# Orbit_I_AnalougeEngine_V2_0.net
KiCad netlist of a schematic drawn in EAGLE
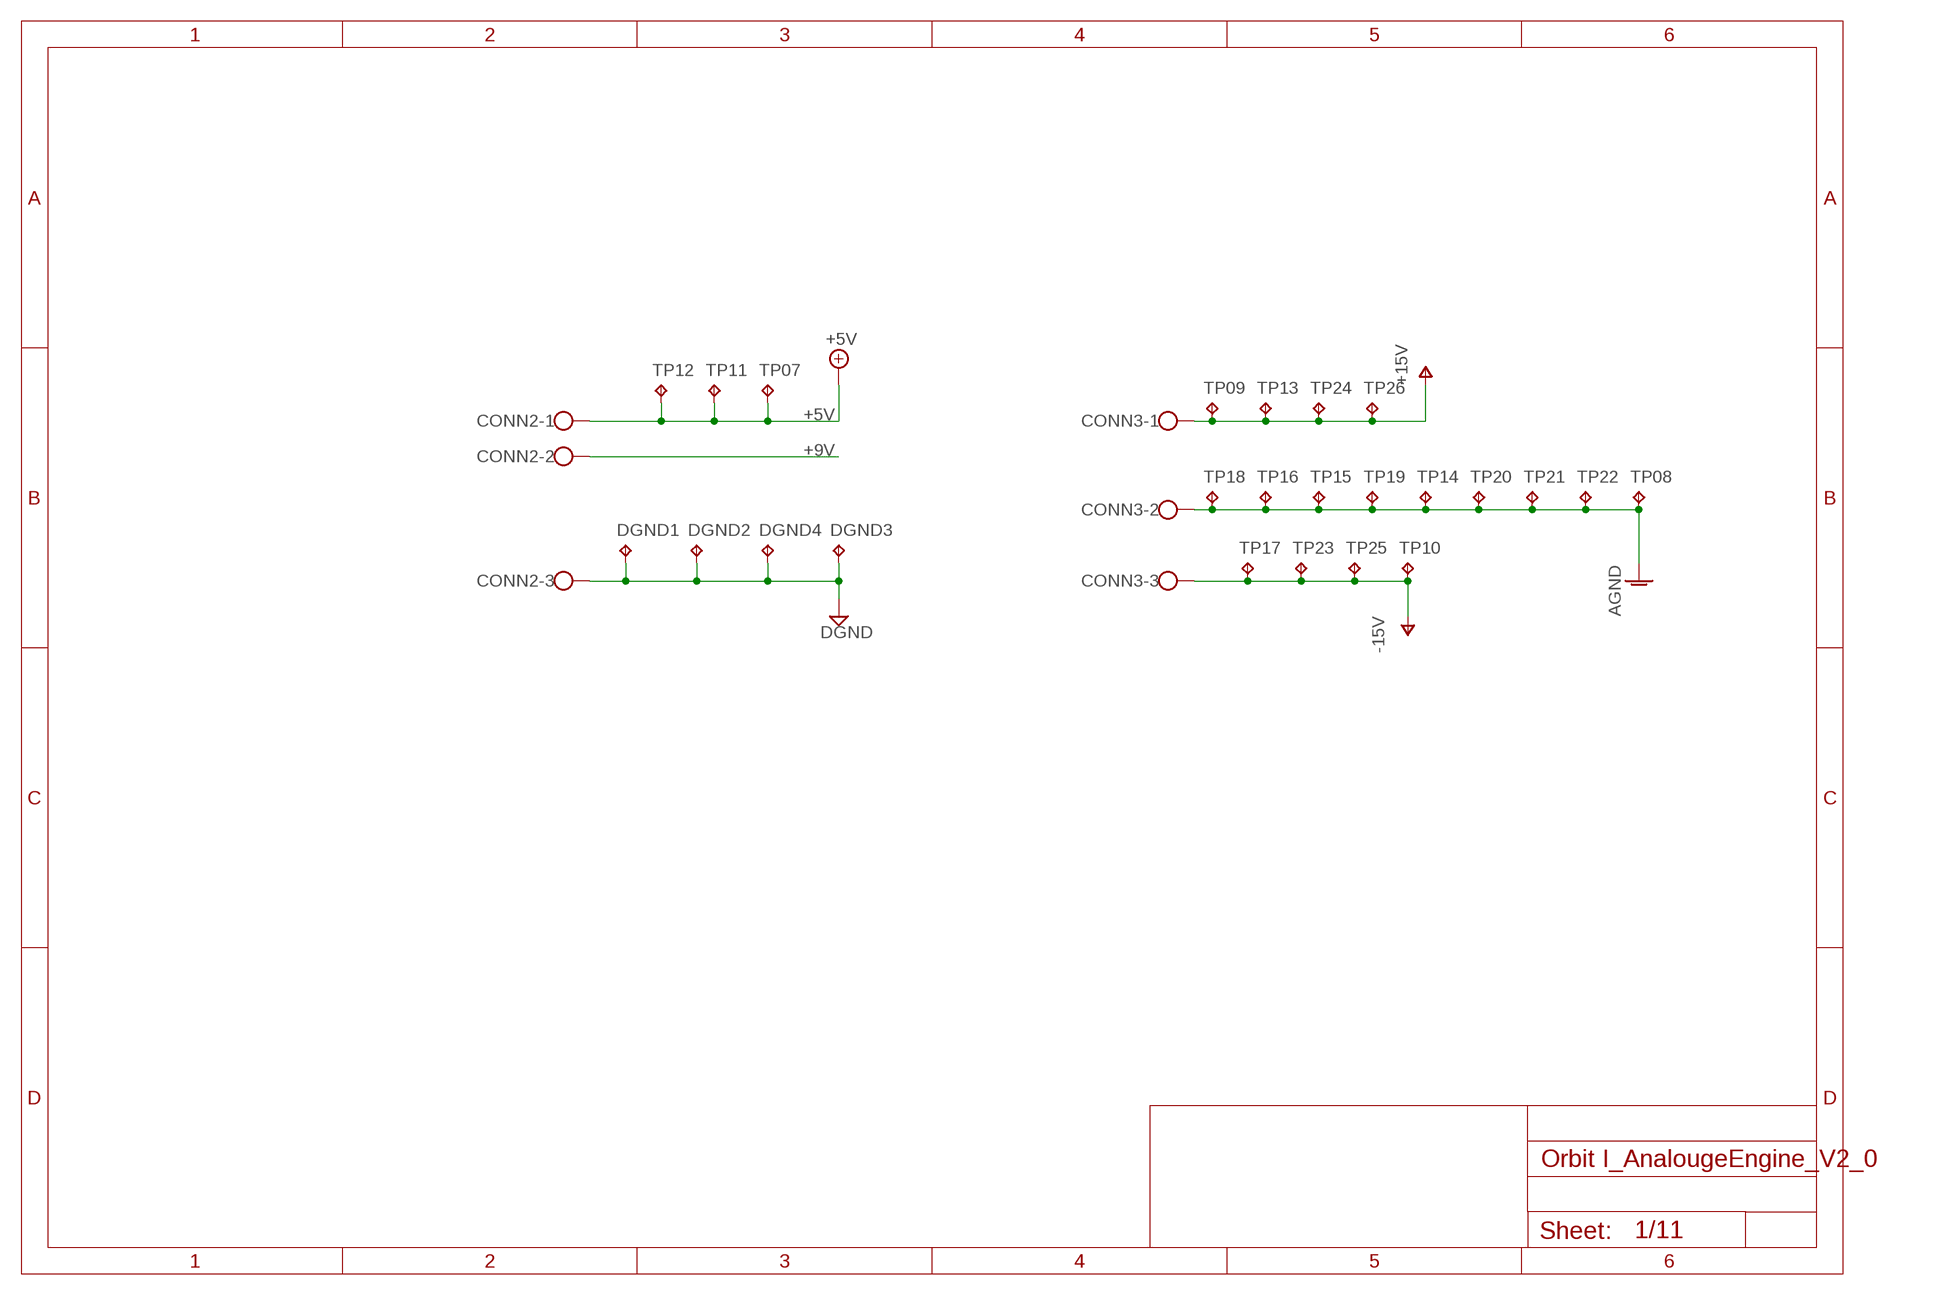
[diagram p0: schematic, sheet 1]
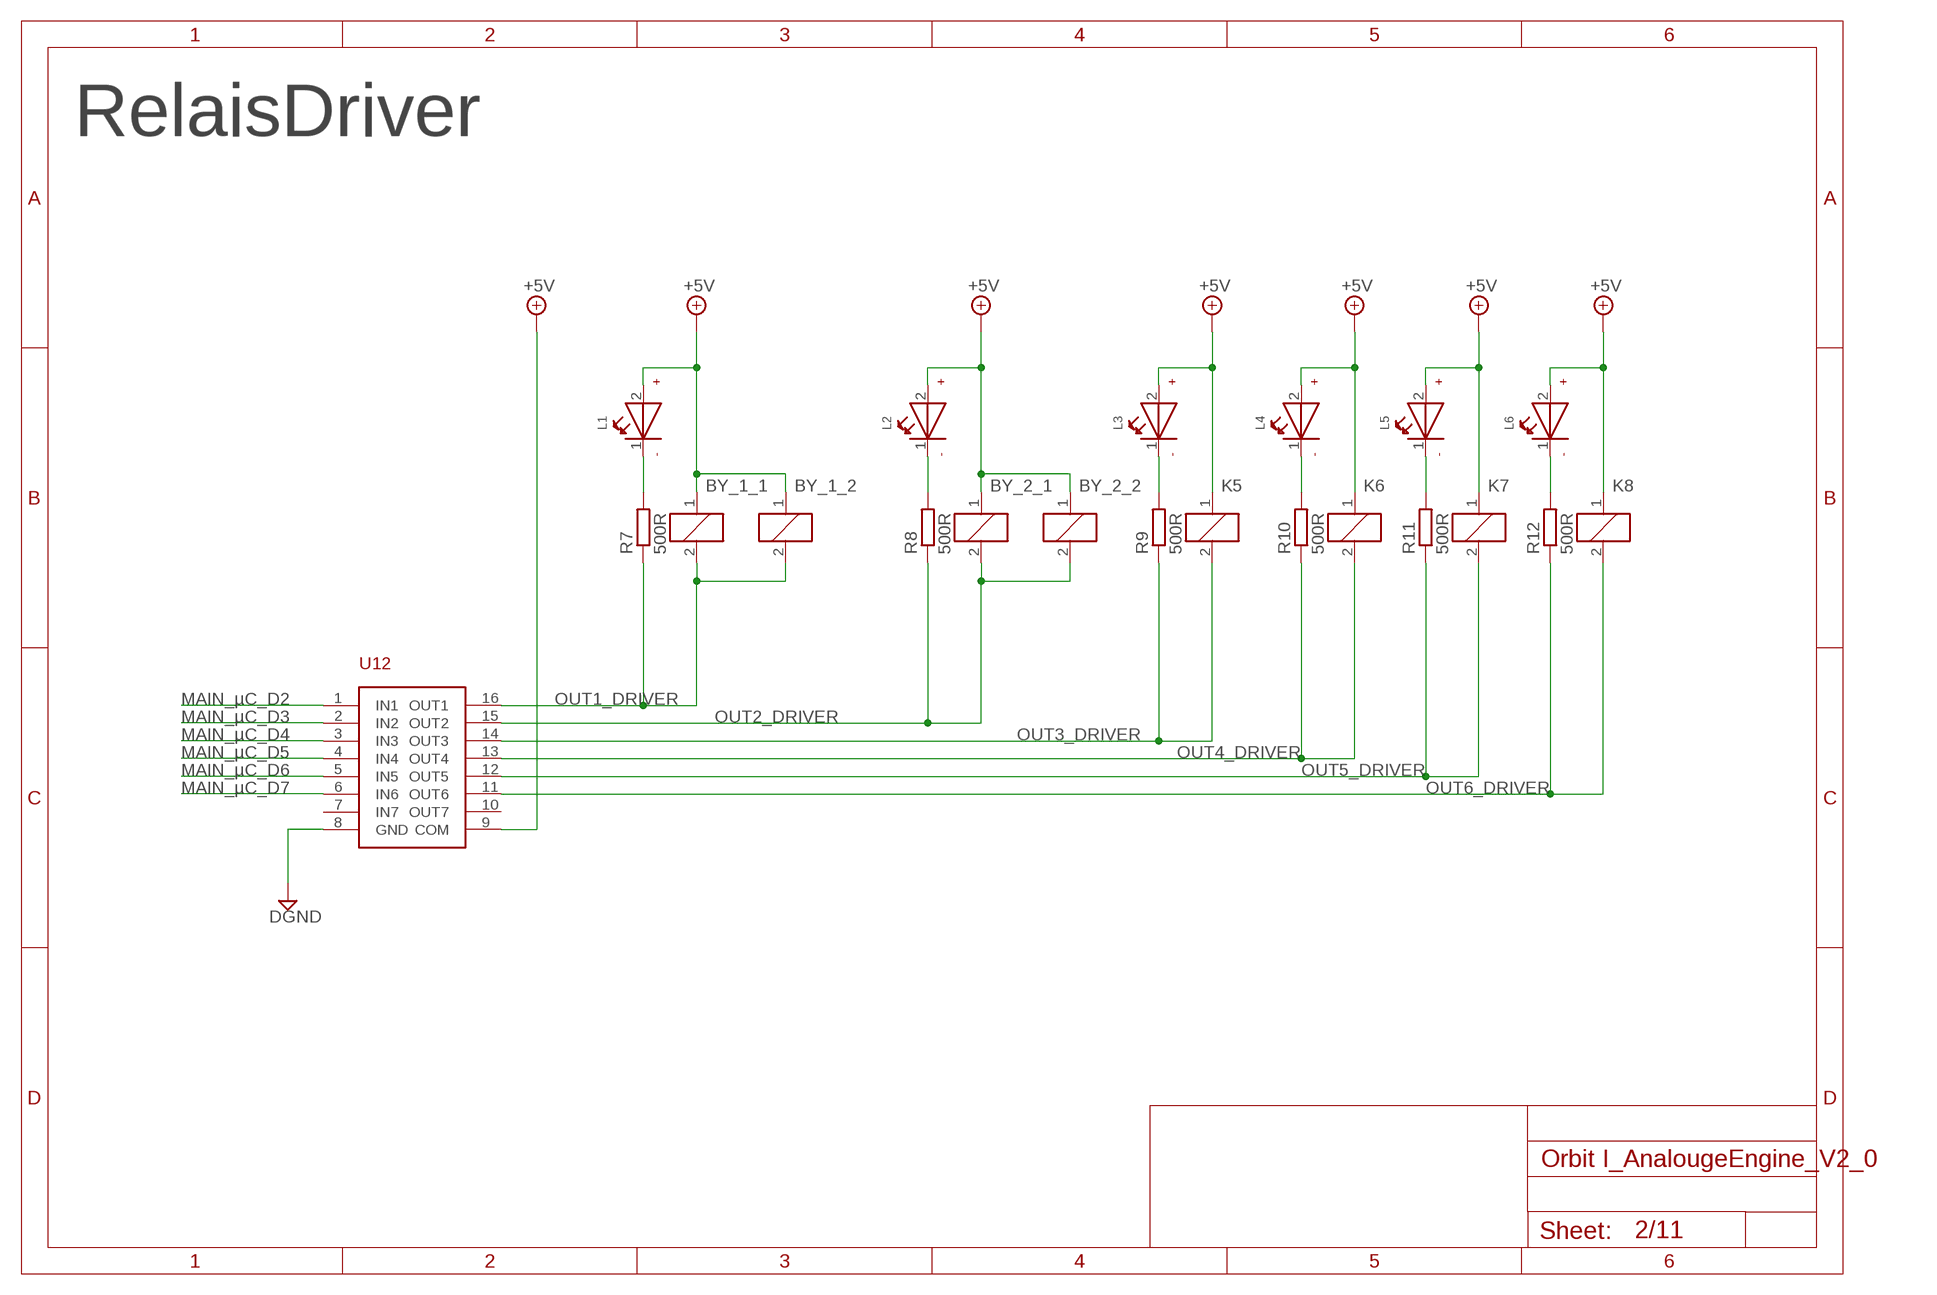
[diagram p1: schematic, sheet 2]
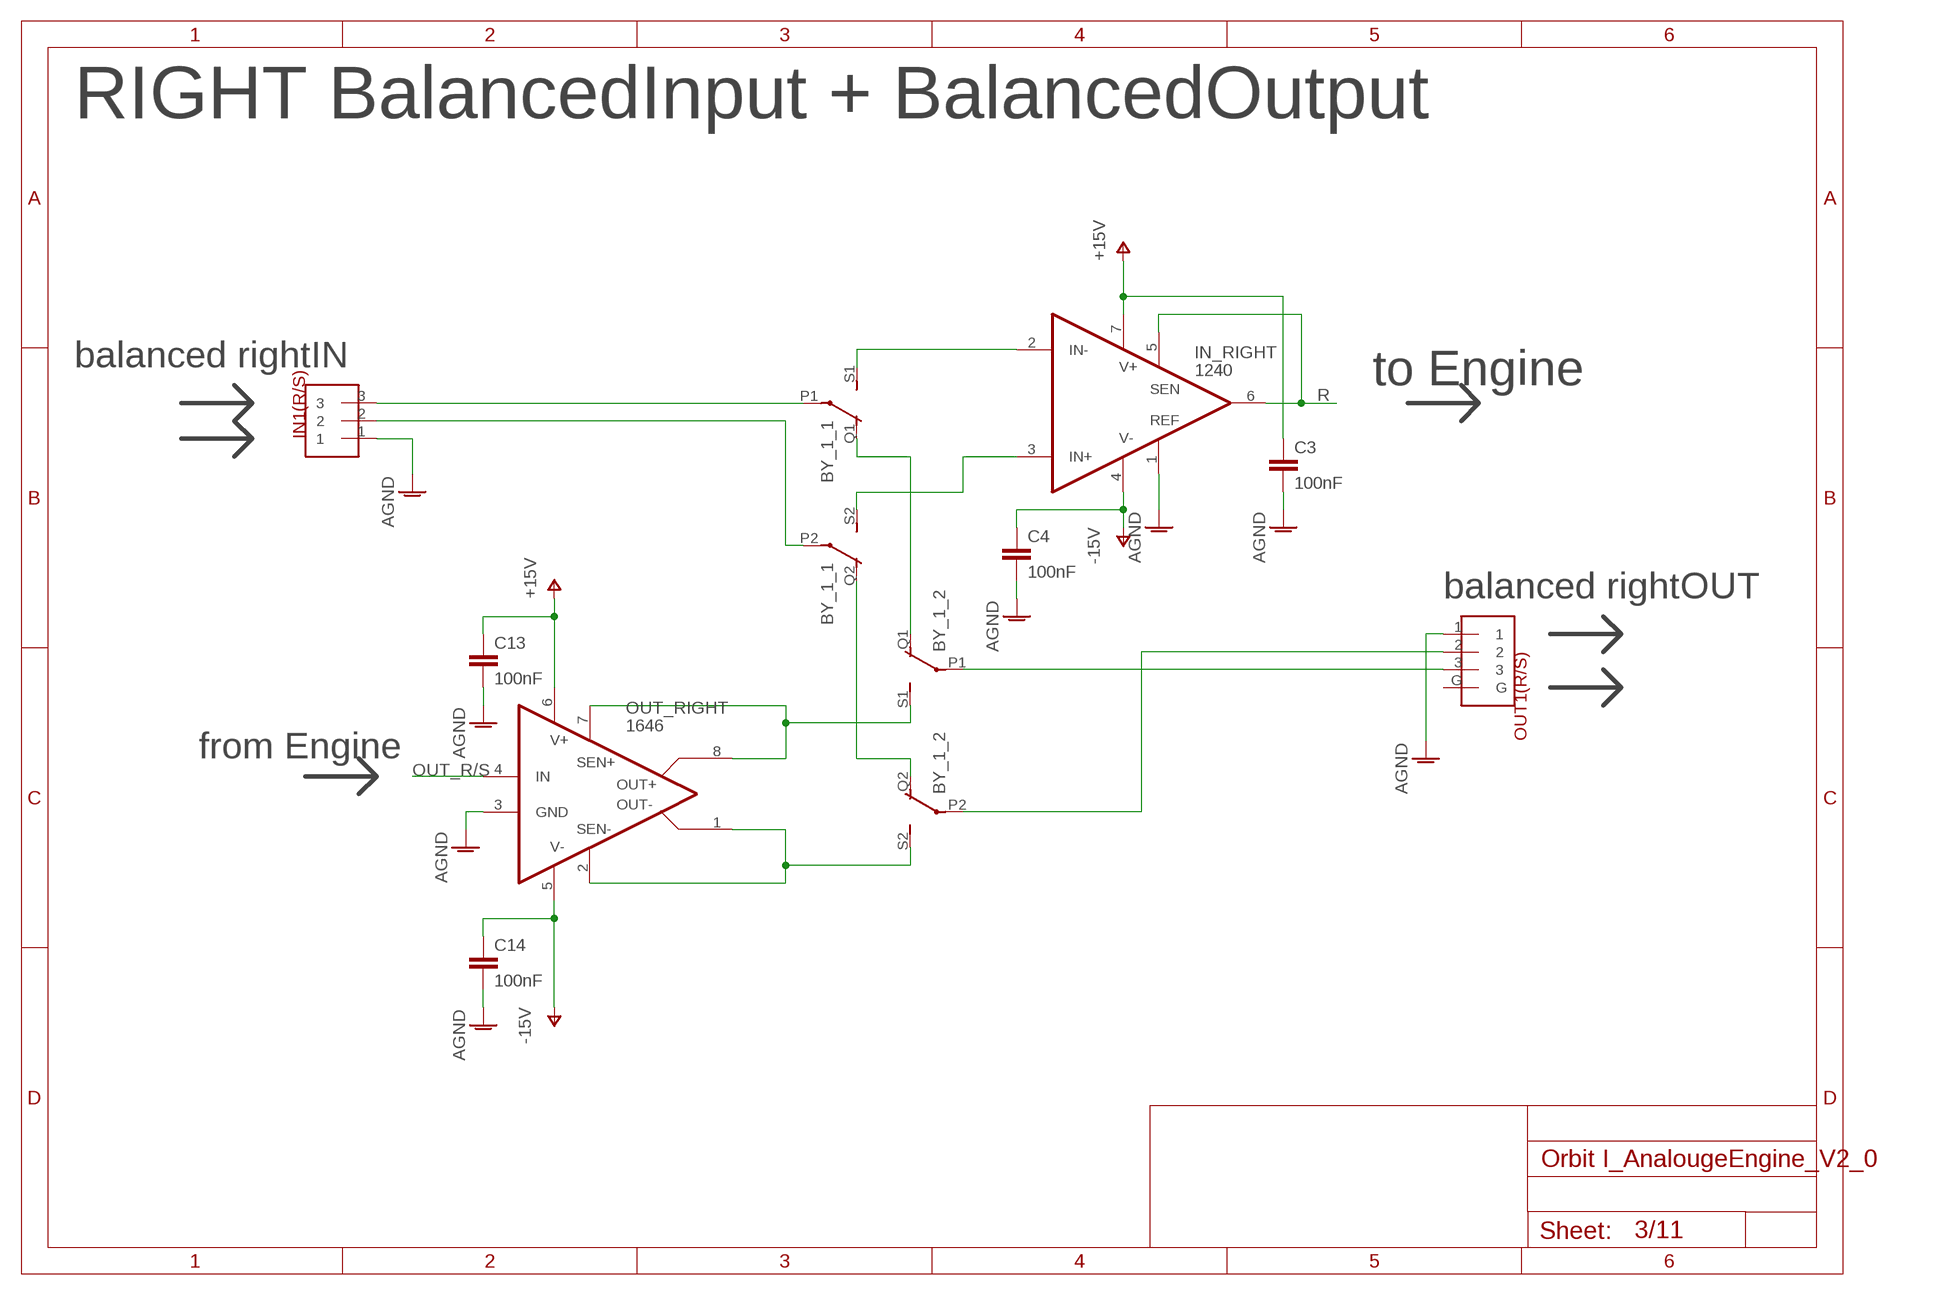
[diagram p2: schematic, sheet 3]
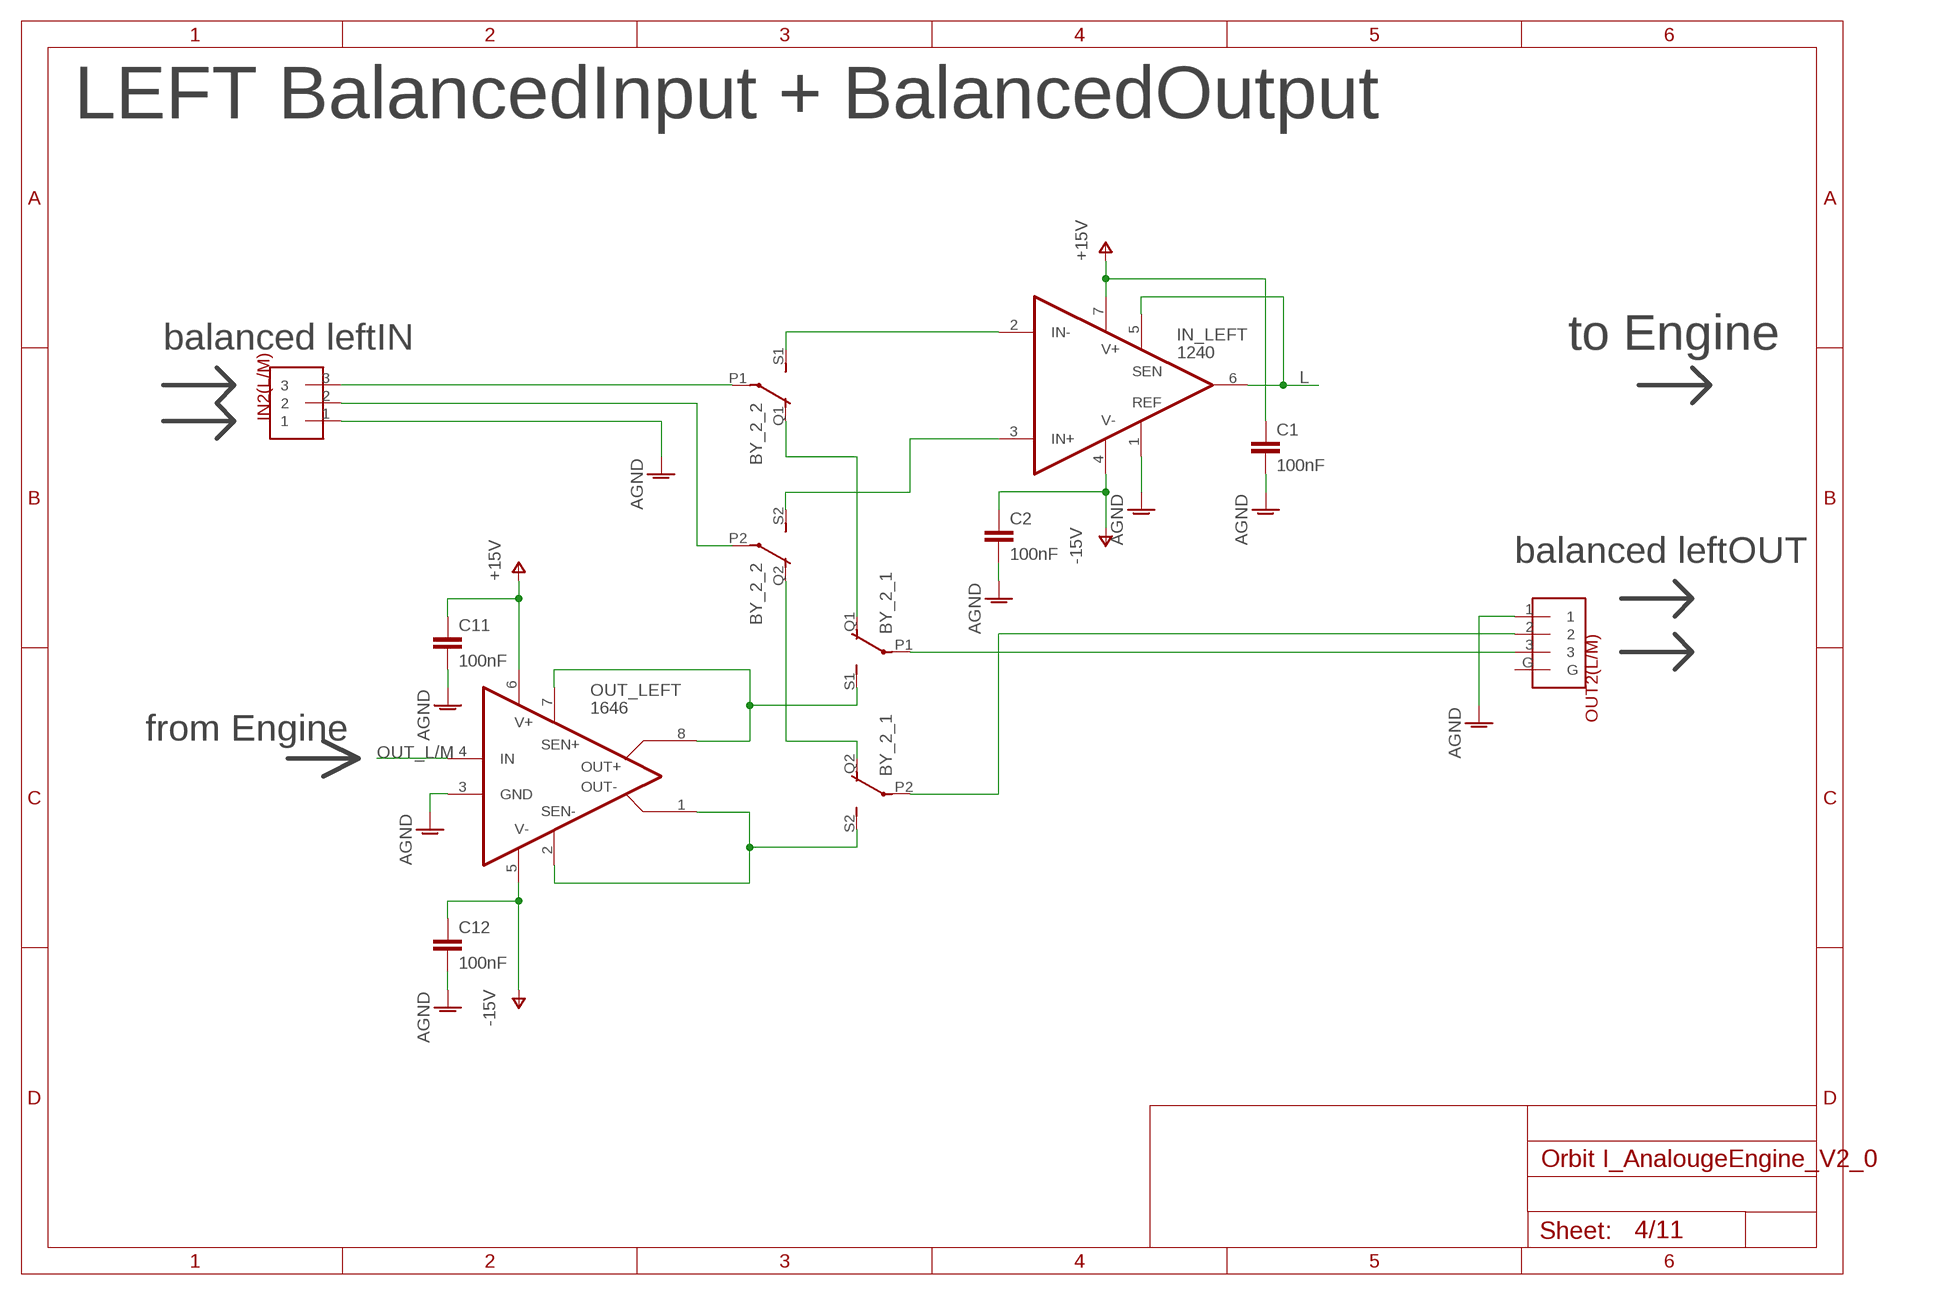
[diagram p3: schematic, sheet 4]
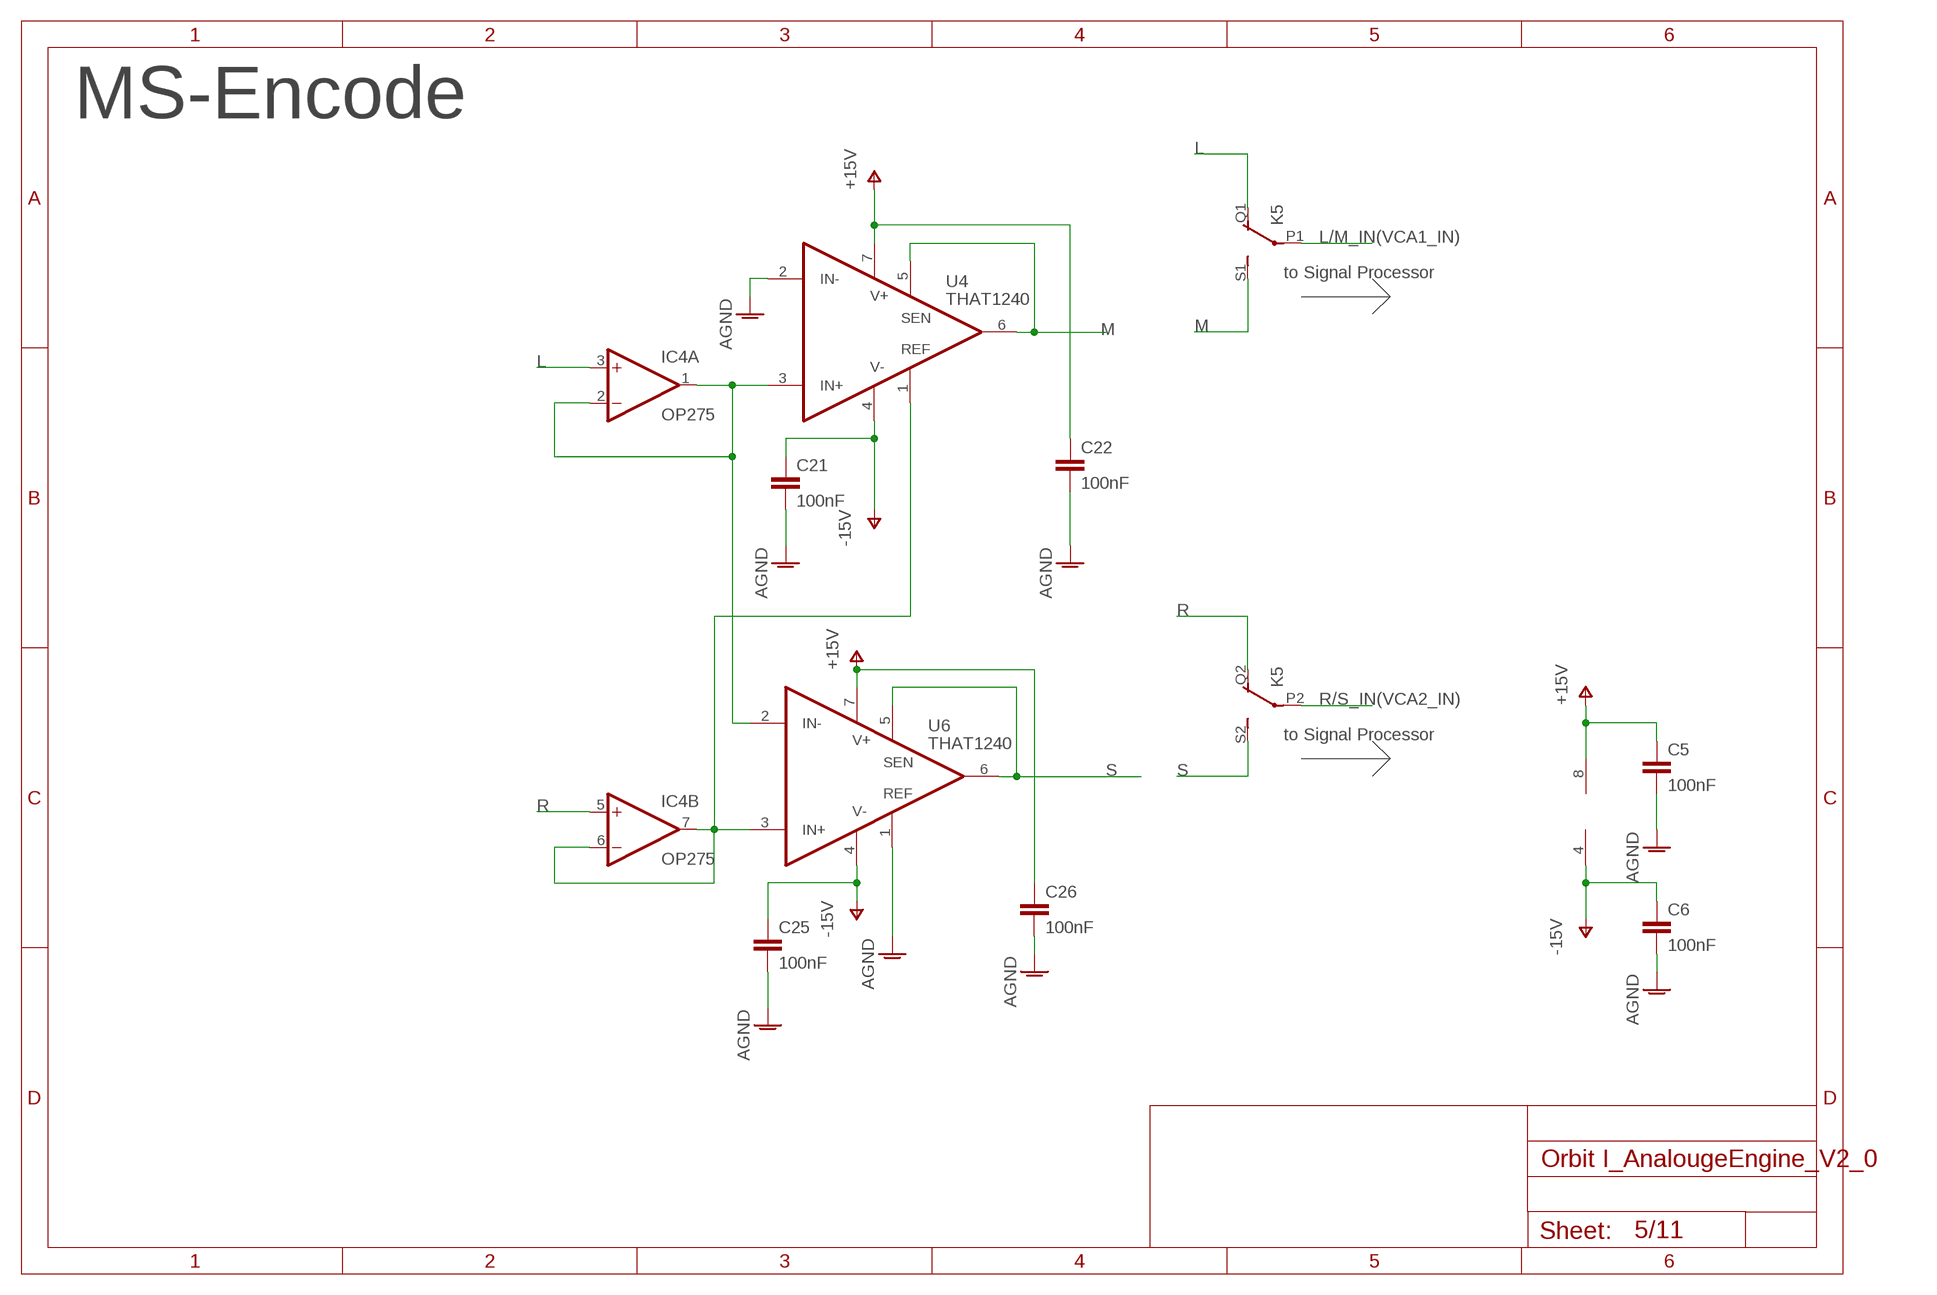
[diagram p4: schematic, sheet 5]
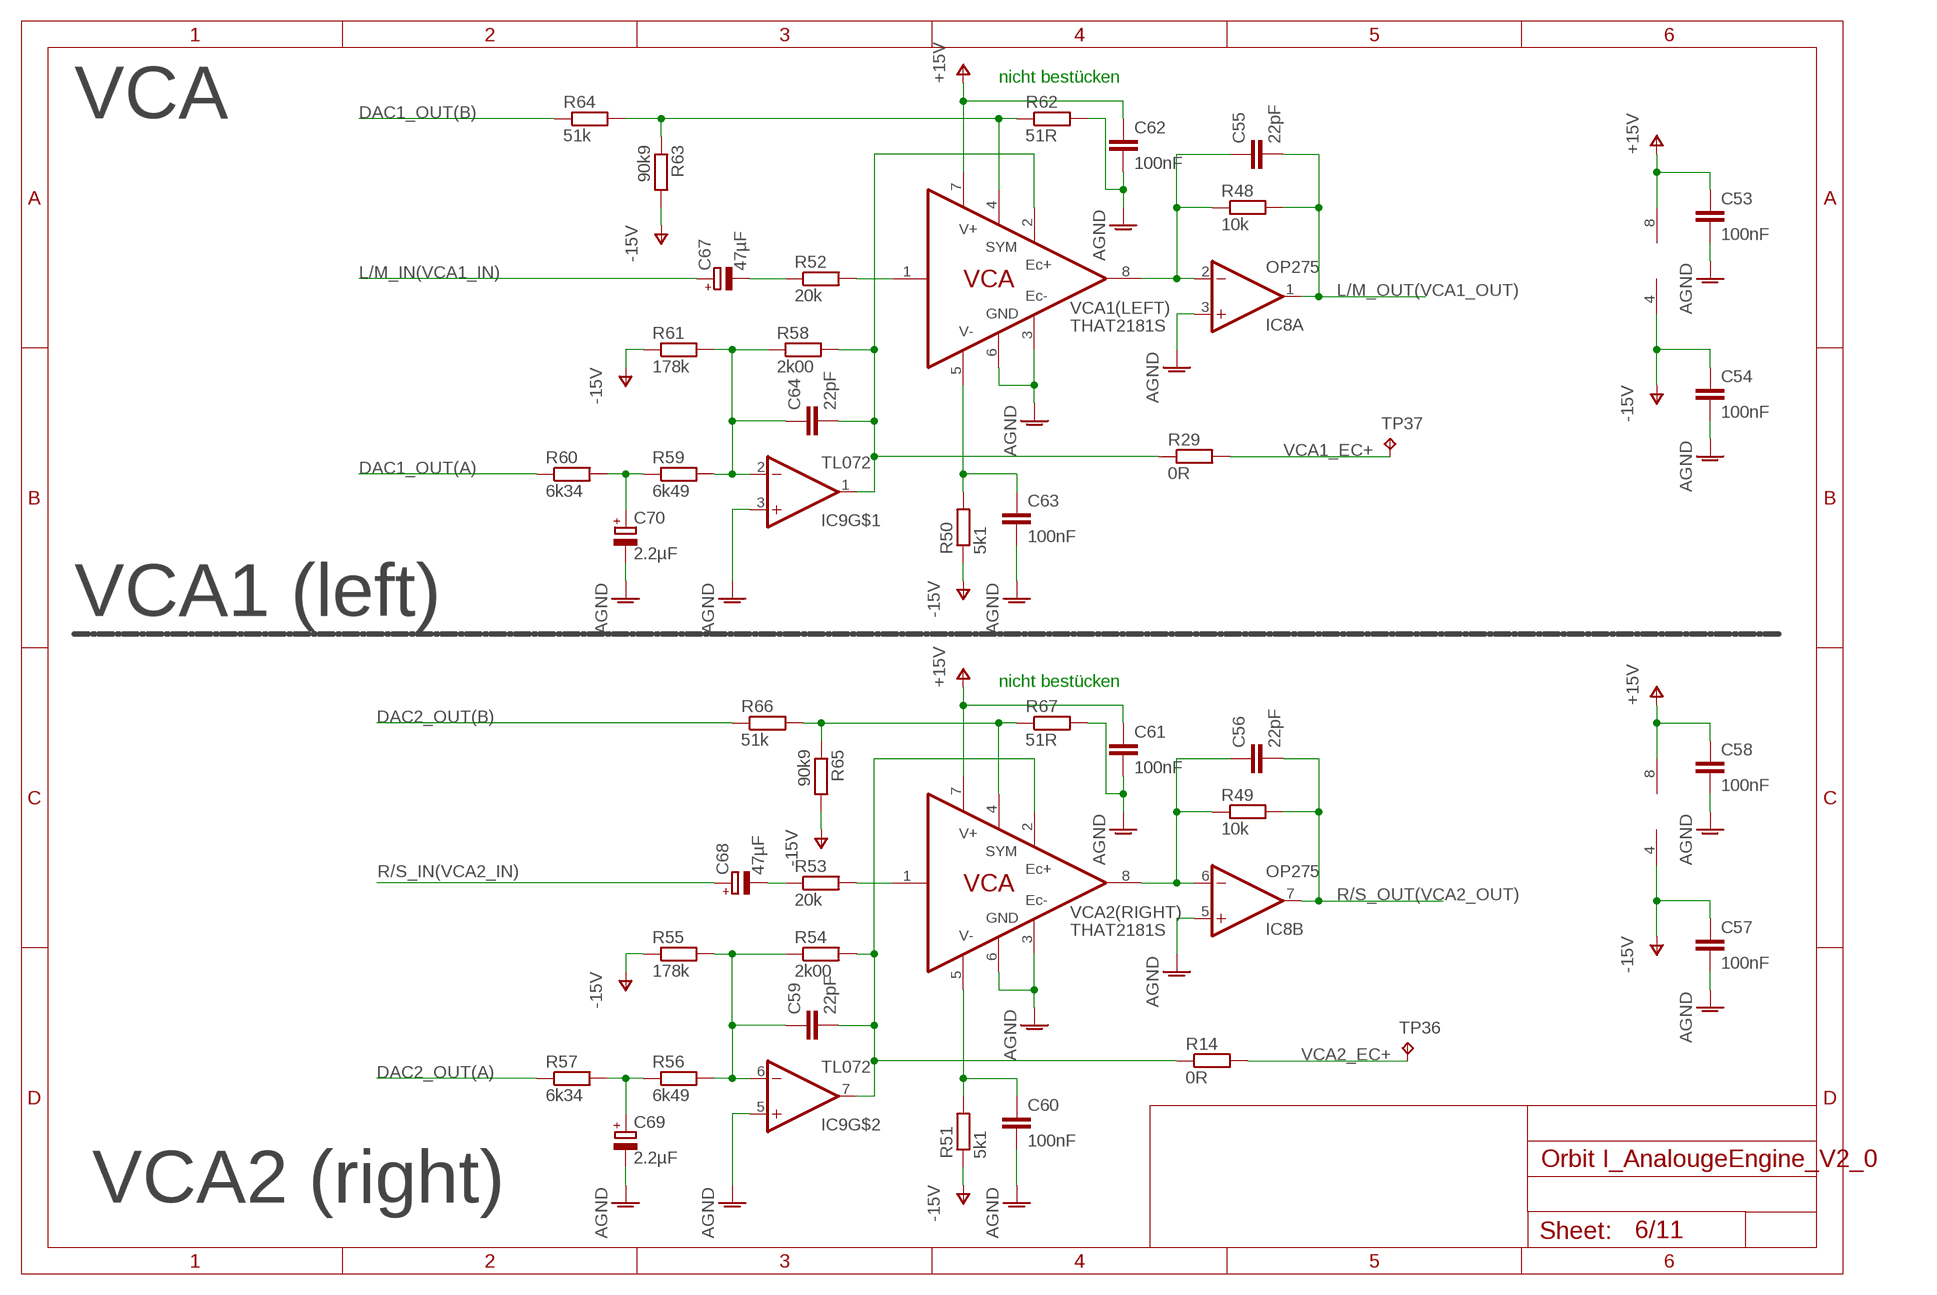
[diagram p5: schematic, sheet 6]
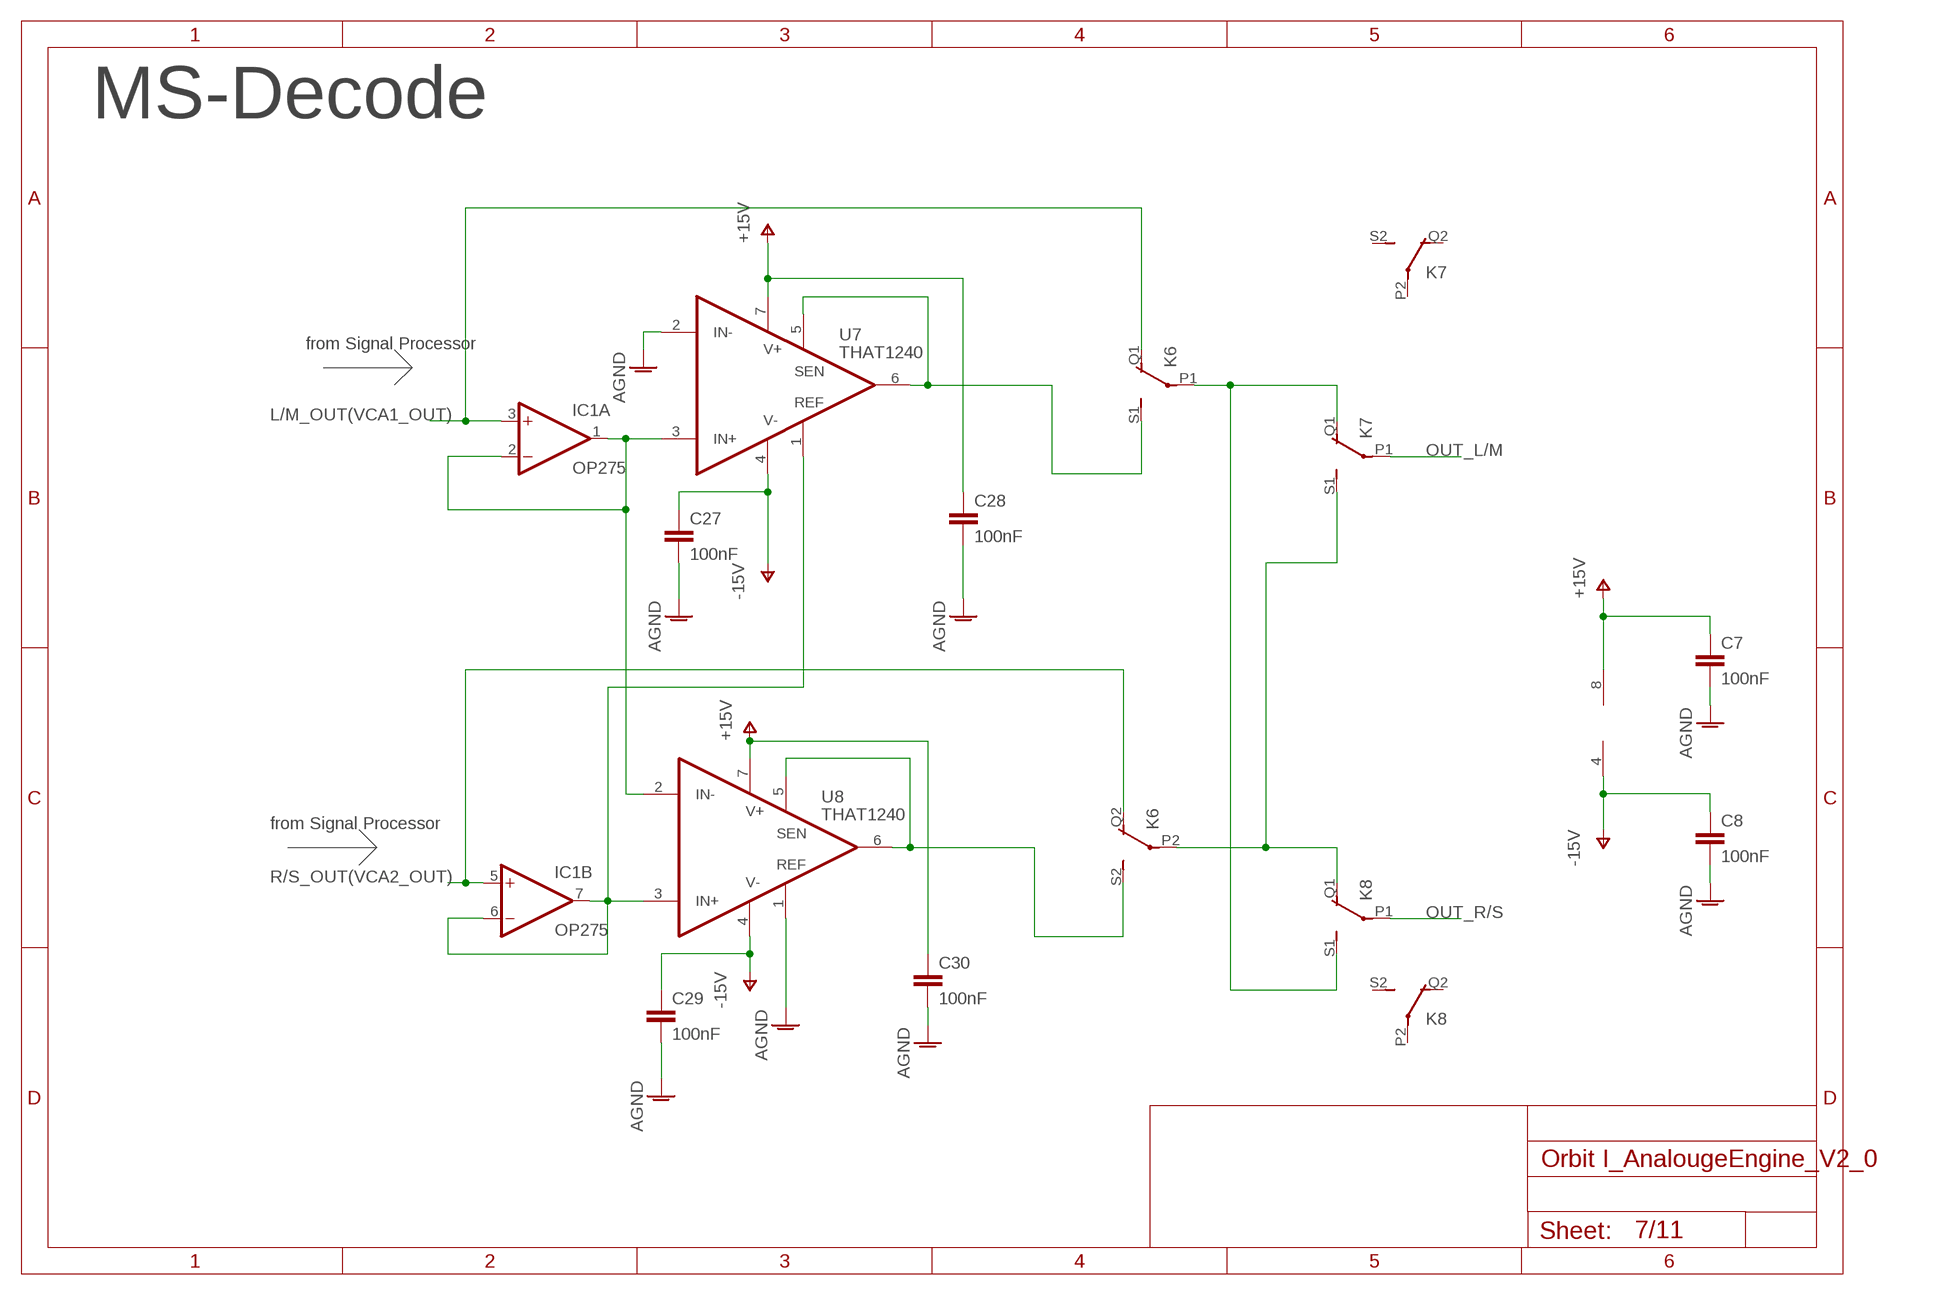
[diagram p6: schematic, sheet 7]
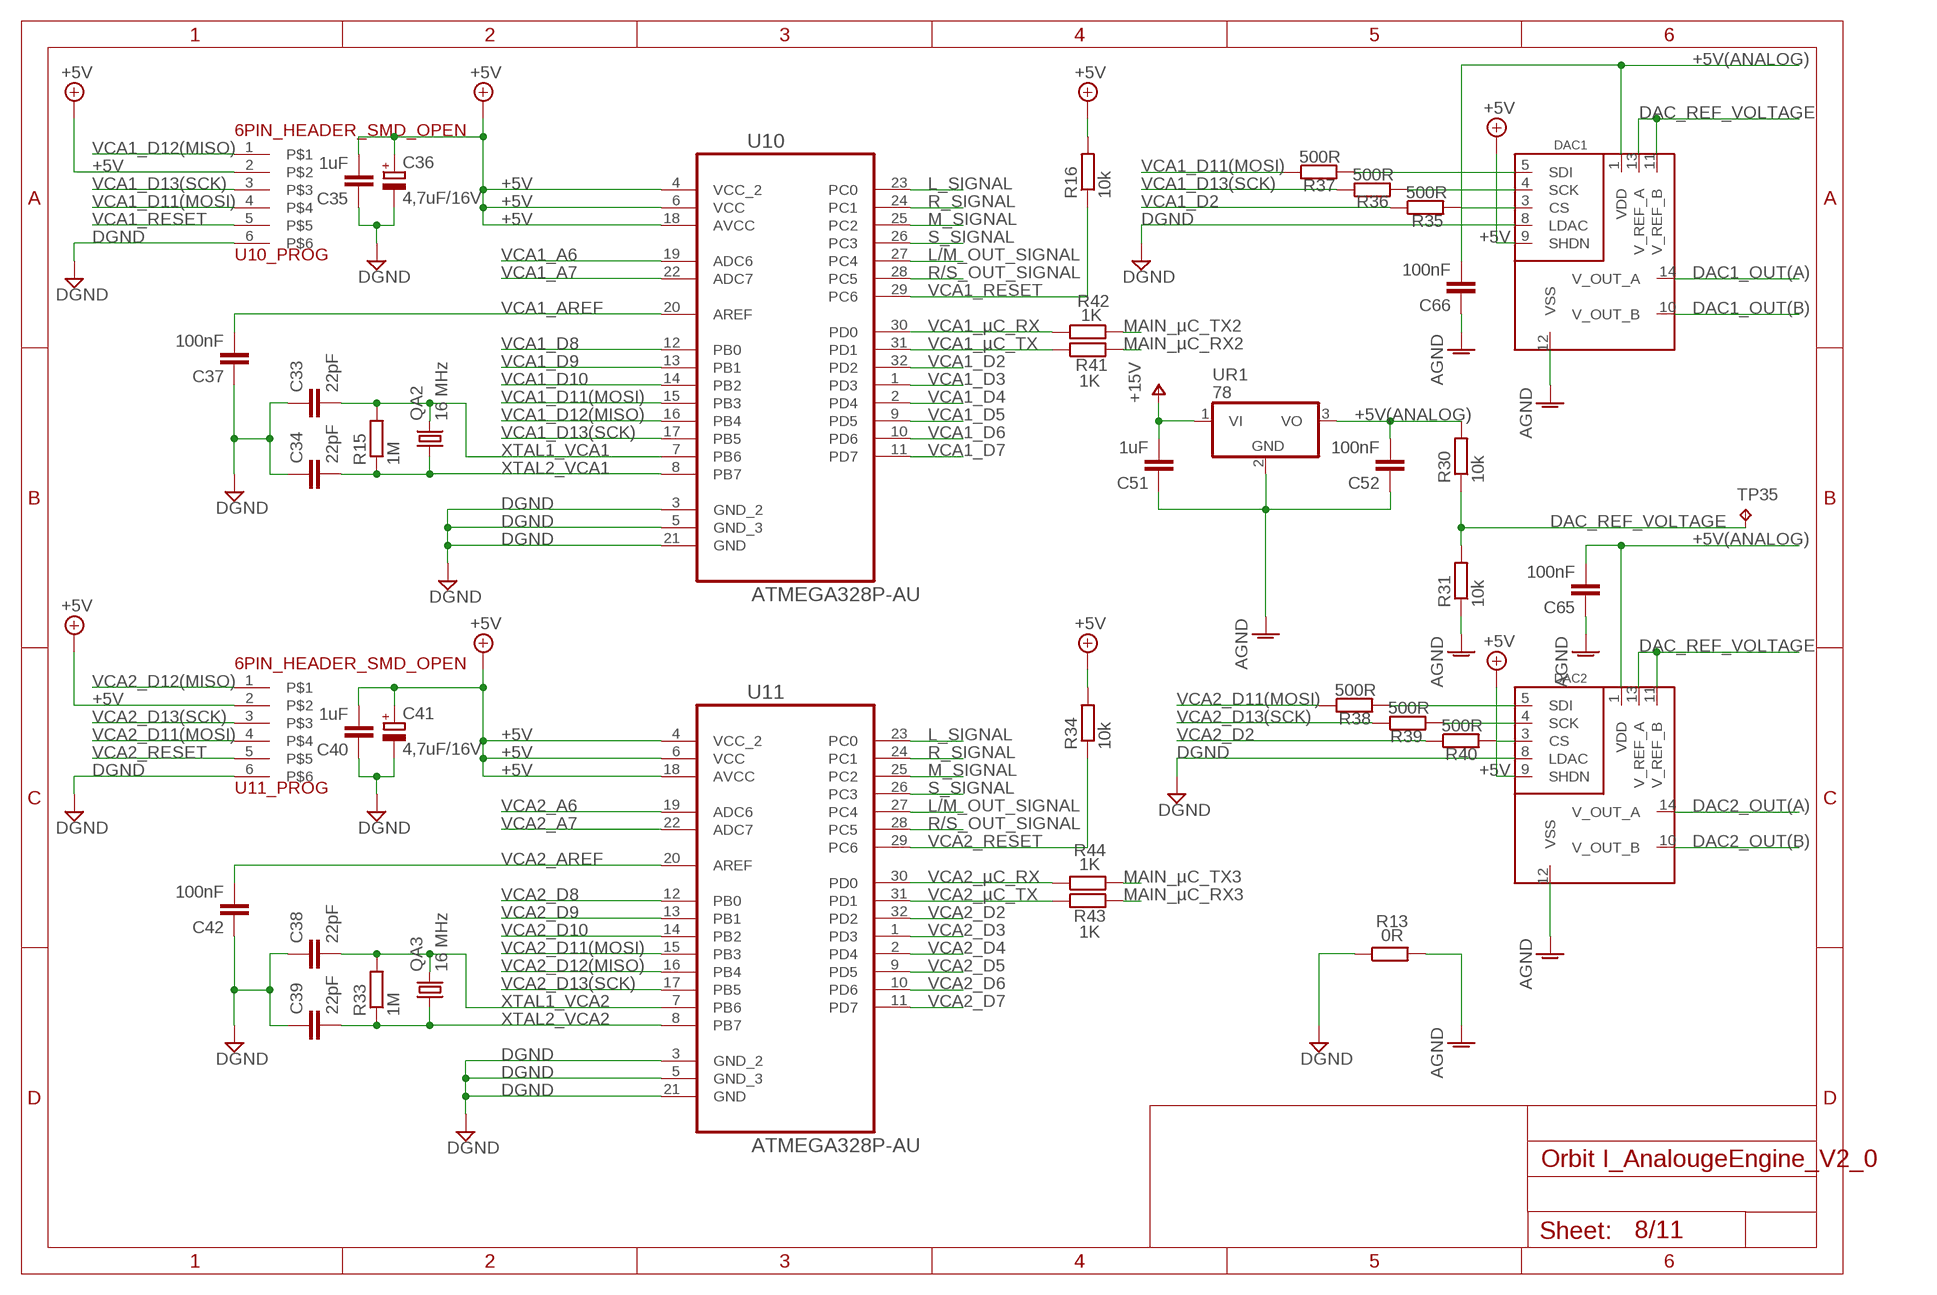
[diagram p7: schematic, sheet 8]
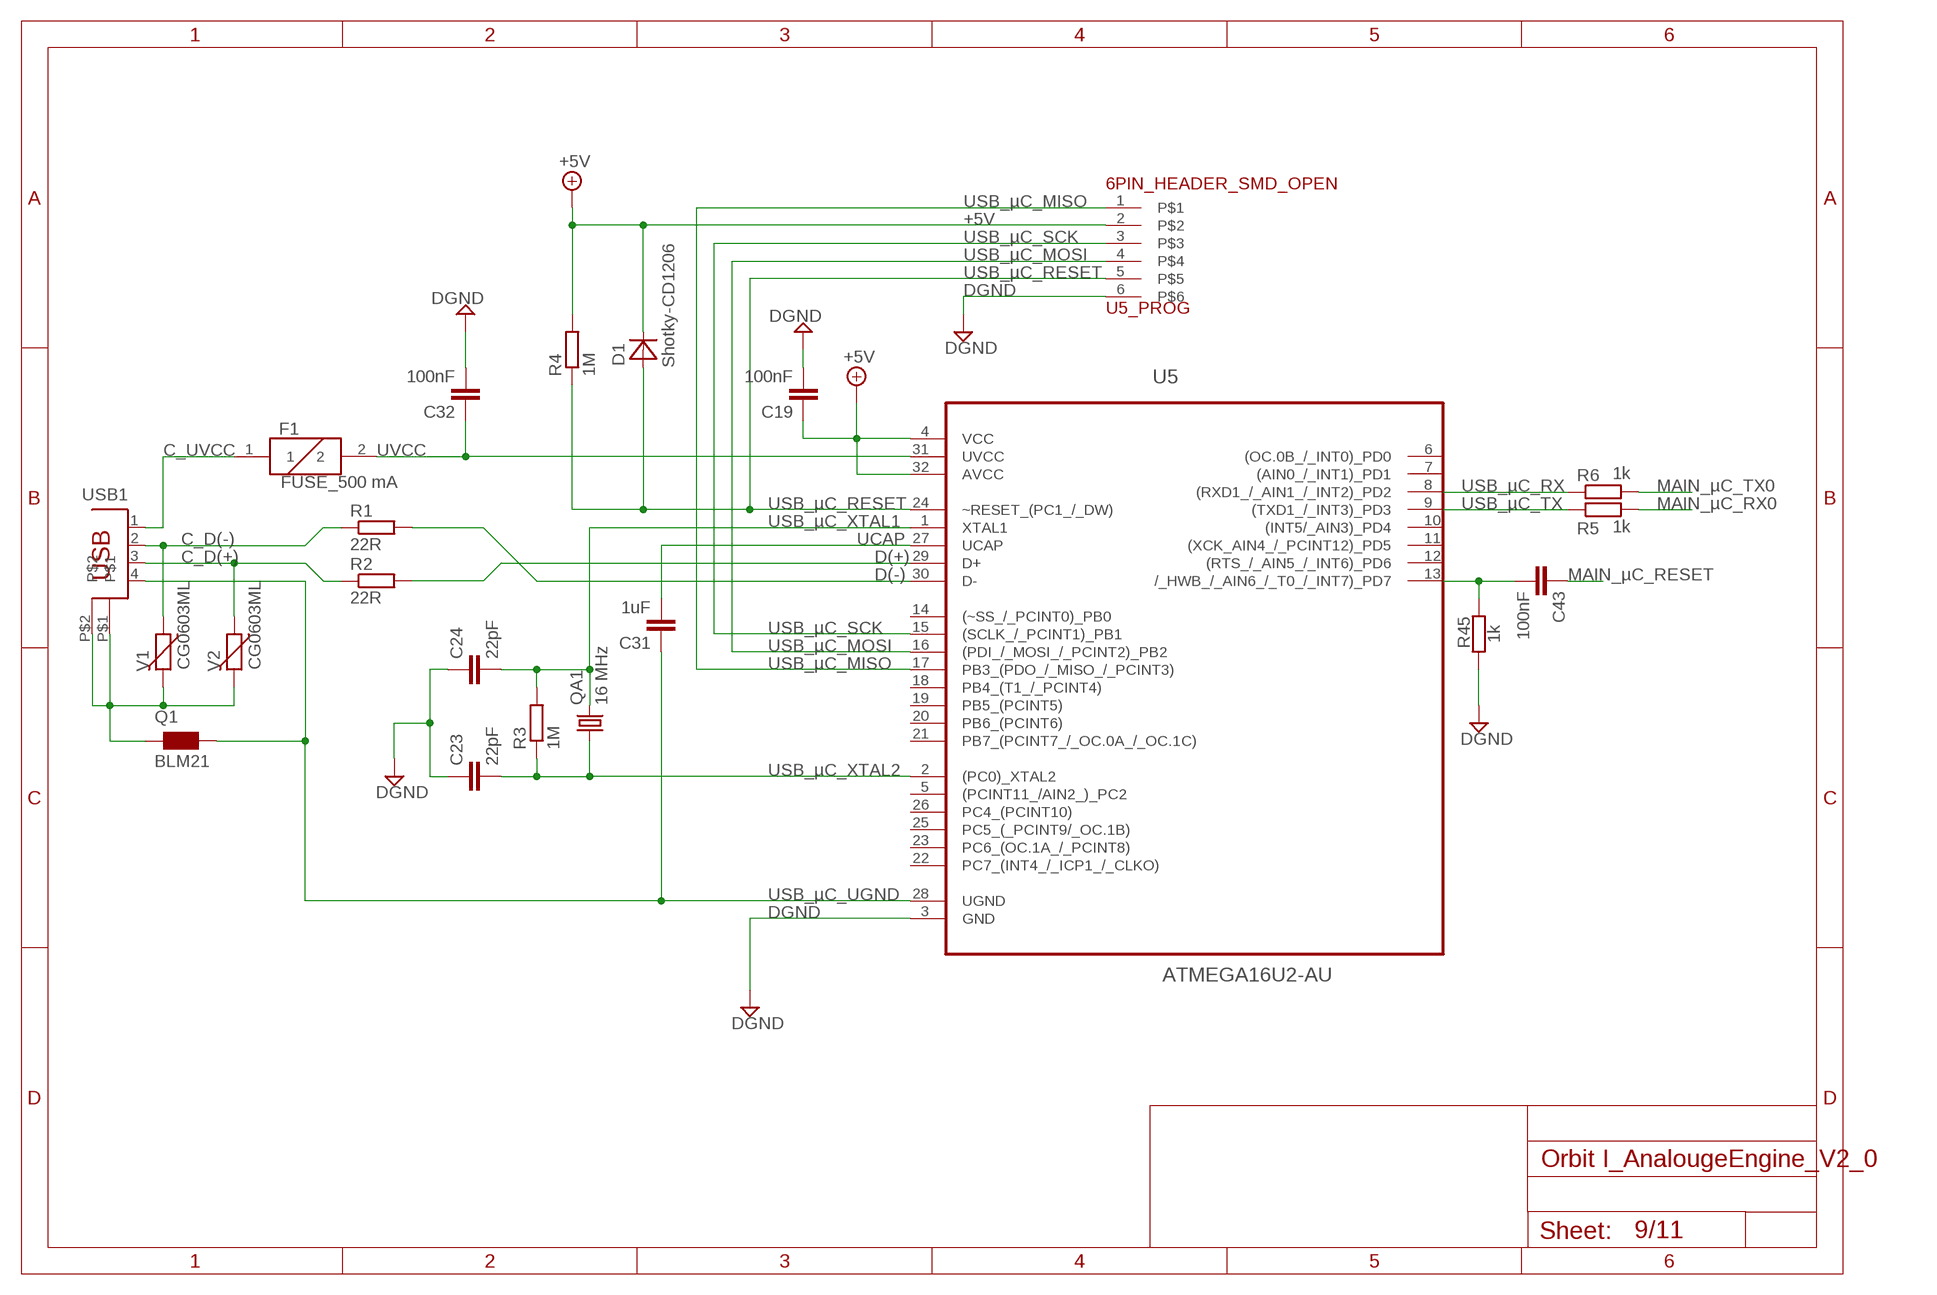
[diagram p8: schematic, sheet 9]
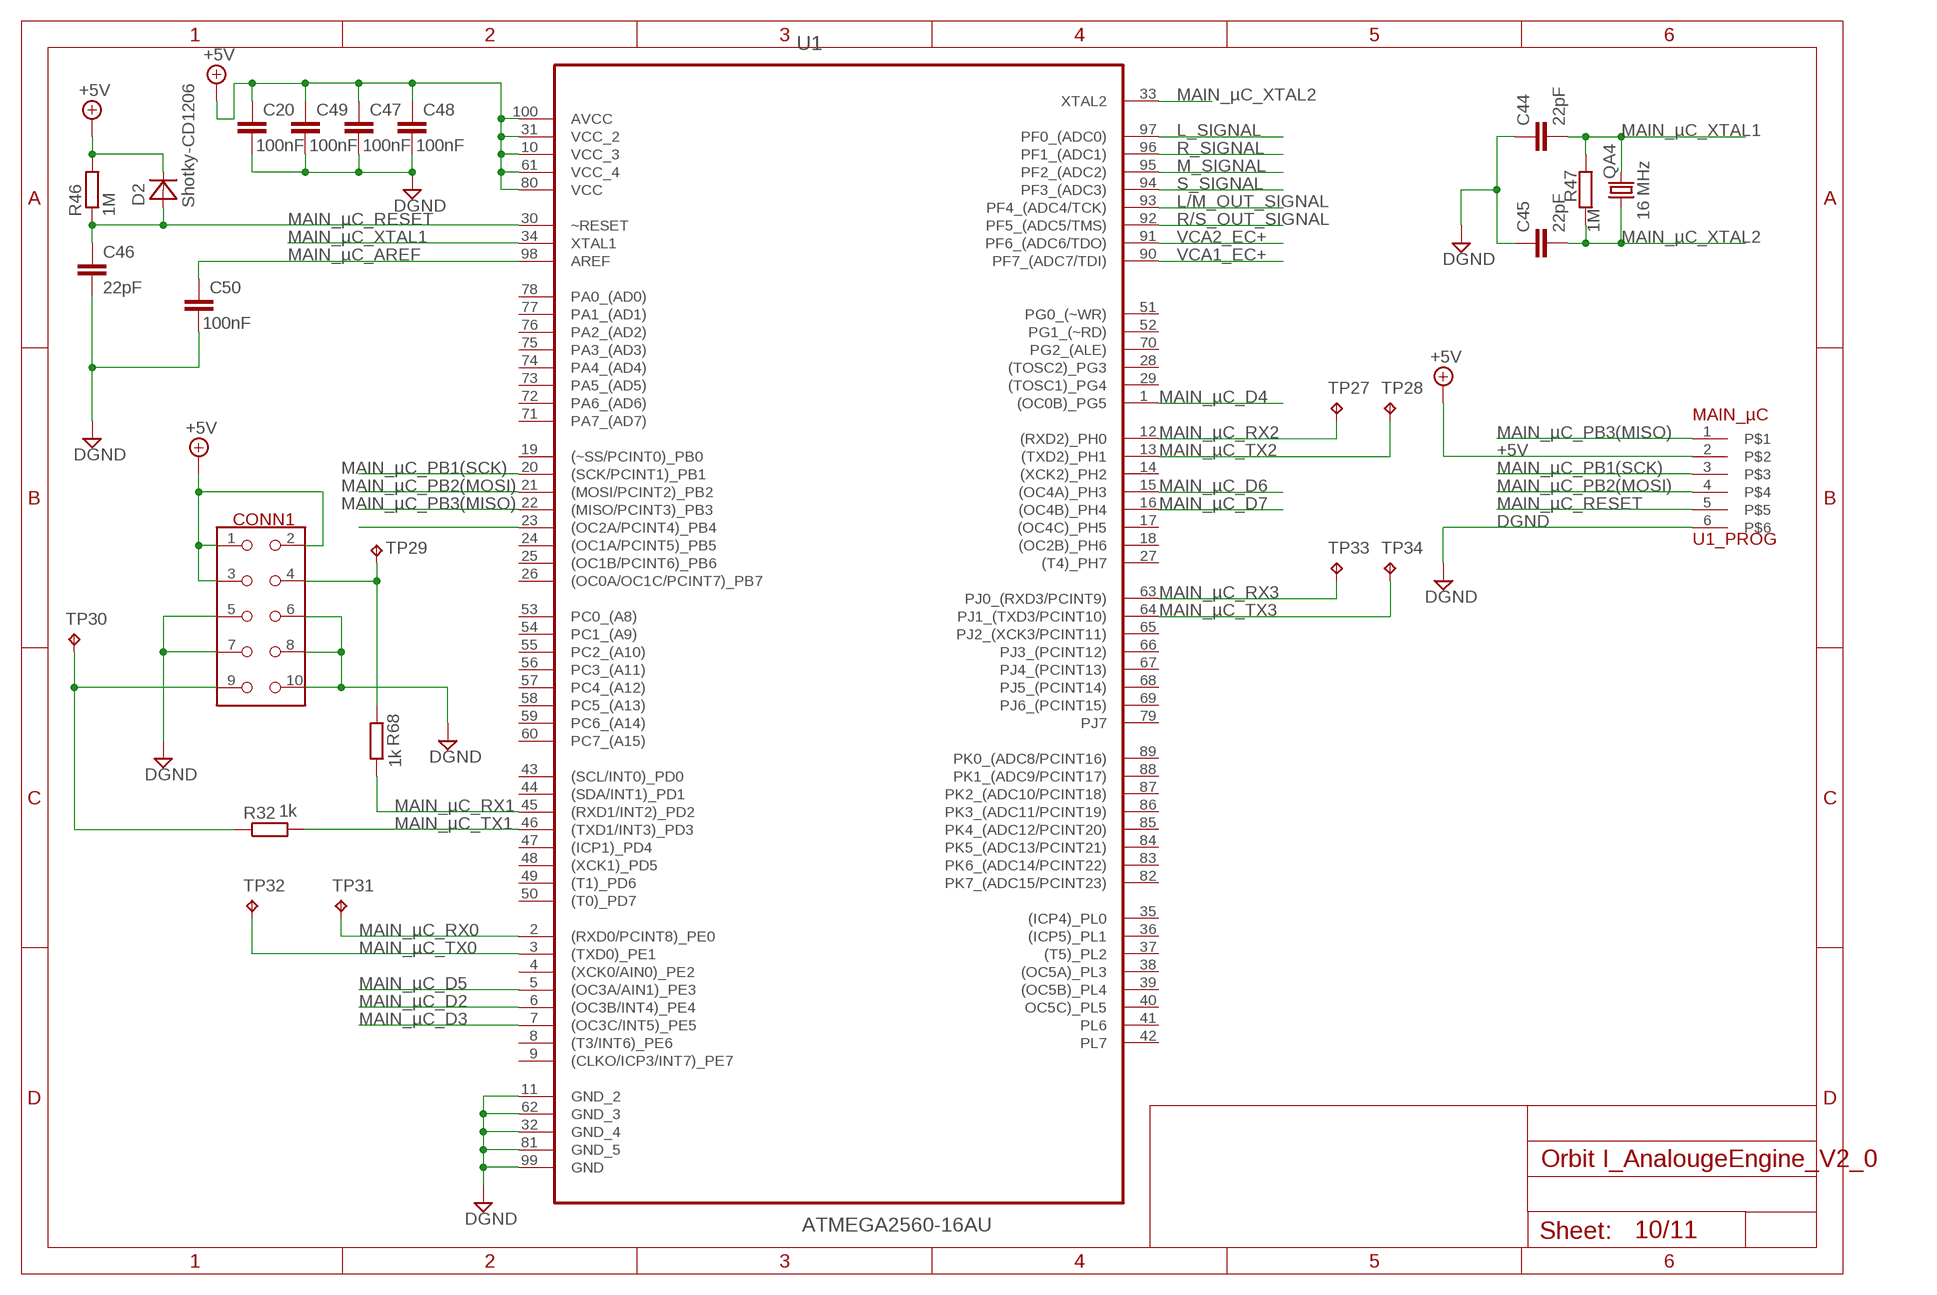
[diagram p9: schematic, sheet 10]
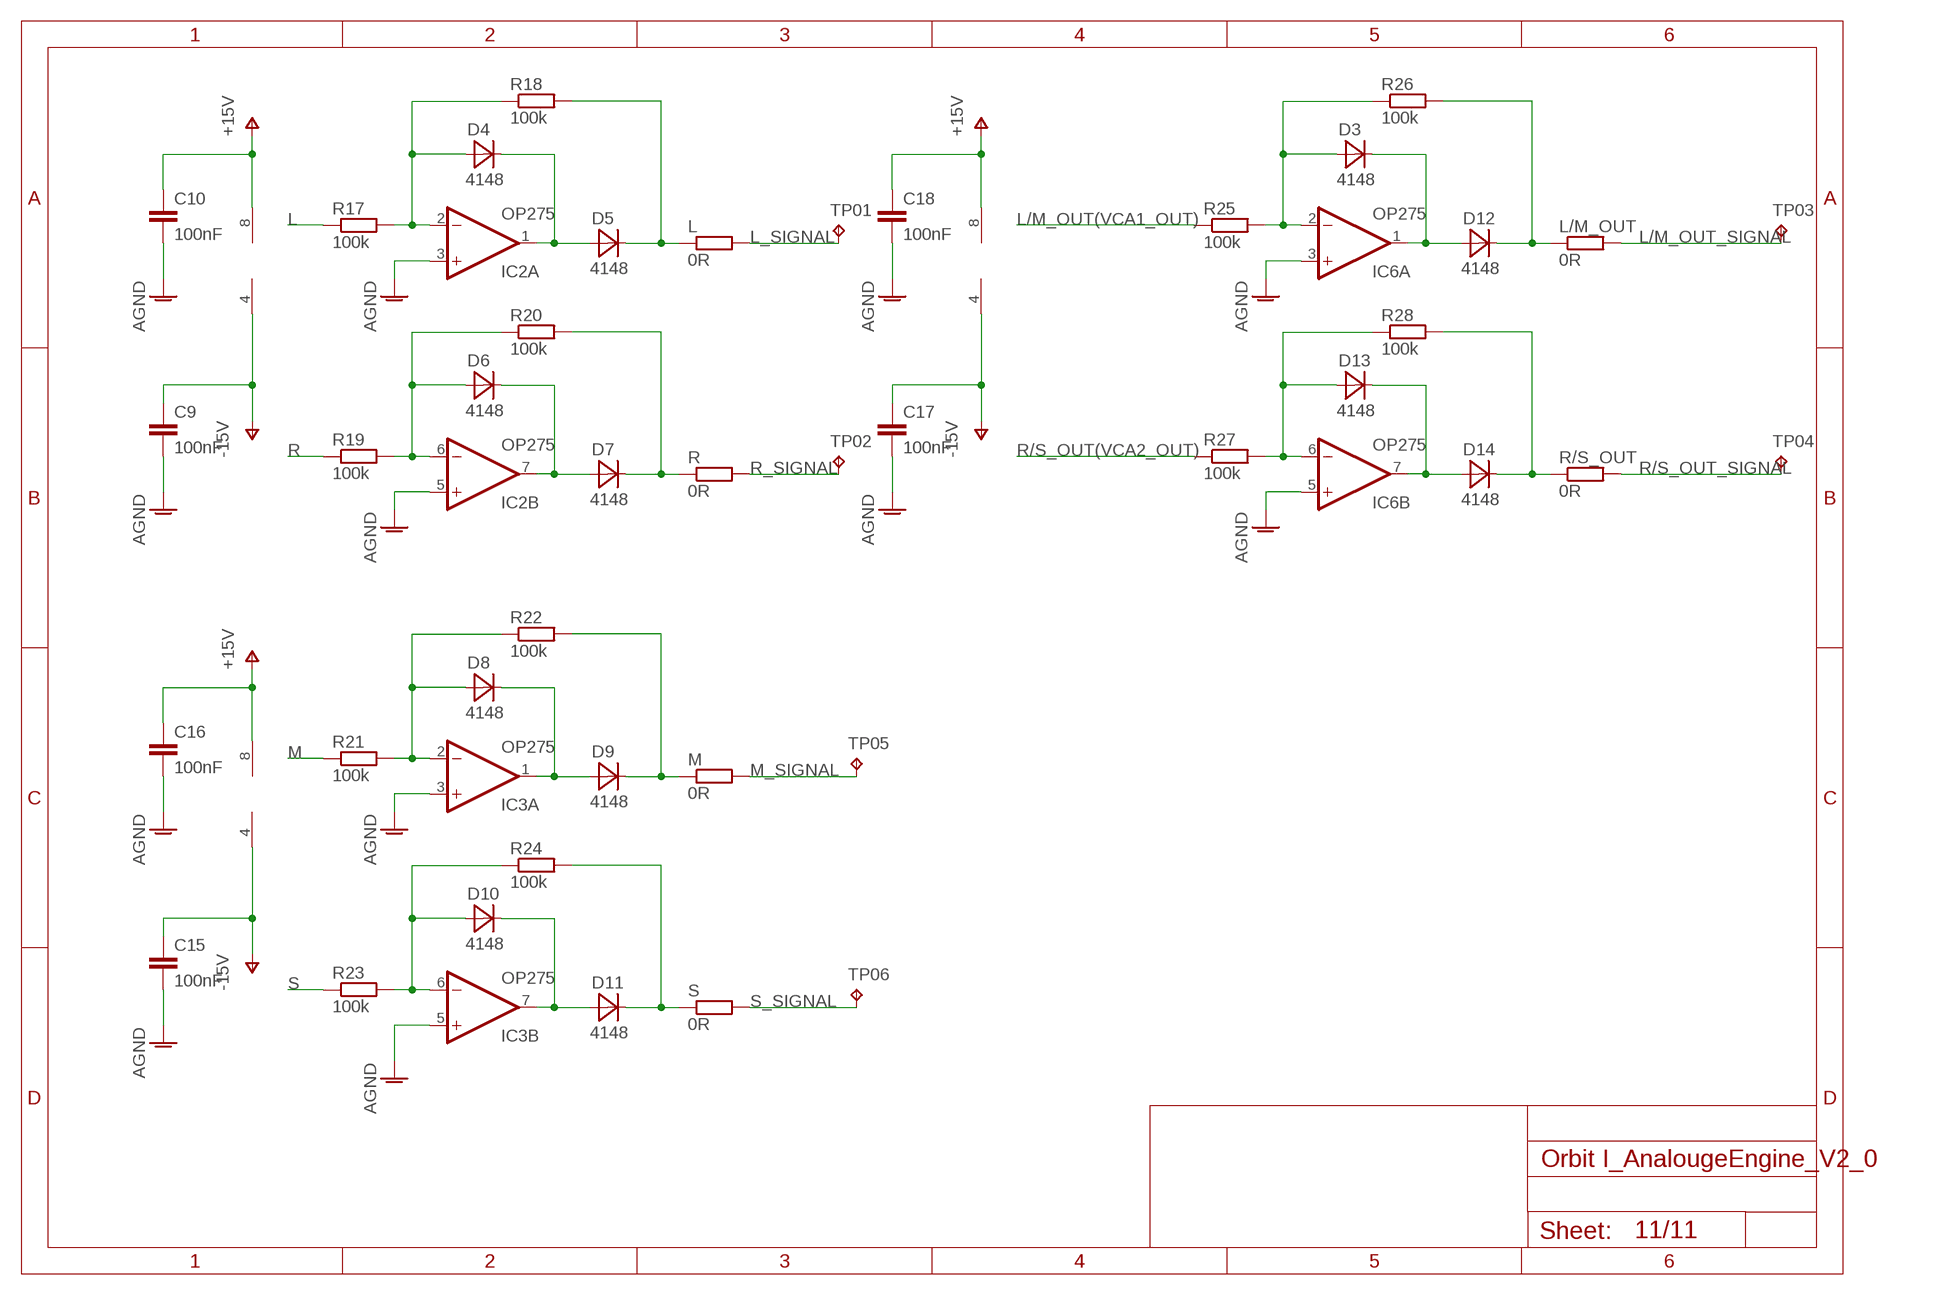
[diagram p10: schematic, sheet 11]

(export (version "E")
  (design (tool "Eeschema 10.0.6"))
  (components
    (comp (ref "CONN2")
      (value "SCHRAUBKLEMME_3POL")
      (footprint "eagle-import:W237-103")
      (fields (field (name "MPN") "237-103"))
      (libsource (lib "eagle-import") (part "SCHRAUBKLEMME_3POL"))
    )
    (comp (ref "CONN3")
      (value "SCHRAUBKLEMME_3POL")
      (footprint "eagle-import:W237-103")
      (fields (field (name "MPN") "237-103"))
      (libsource (lib "eagle-import") (part "SCHRAUBKLEMME_3POL"))
    )
    (comp (ref "DGND1")
      (value "TPTHT")
      (footprint "eagle-import:THT_PIN")
      (libsource (lib "eagle-import") (part "TPTHT"))
    )
    (comp (ref "DGND2")
      (value "TPTHT")
      (footprint "eagle-import:THT_PIN")
      (libsource (lib "eagle-import") (part "TPTHT"))
    )
    (comp (ref "DGND3")
      (value "TPTHT")
      (footprint "eagle-import:THT_PIN")
      (libsource (lib "eagle-import") (part "TPTHT"))
    )
    (comp (ref "DGND4")
      (value "TPTHT")
      (footprint "eagle-import:THT_PIN")
      (libsource (lib "eagle-import") (part "TPTHT"))
    )
    (comp (ref "TP07")
      (value "TPTHT")
      (footprint "eagle-import:THT_PIN")
      (libsource (lib "eagle-import") (part "TPTHT"))
    )
    (comp (ref "TP08")
      (value "TPTHT")
      (footprint "eagle-import:THT_PIN")
      (libsource (lib "eagle-import") (part "TPTHT"))
    )
    (comp (ref "TP09")
      (value "TPTHT")
      (footprint "eagle-import:THT_PIN")
      (libsource (lib "eagle-import") (part "TPTHT"))
    )
    (comp (ref "TP10")
      (value "TPTHT")
      (footprint "eagle-import:THT_PIN")
      (libsource (lib "eagle-import") (part "TPTHT"))
    )
    (comp (ref "TP11")
      (value "TPTHT")
      (footprint "eagle-import:THT_PIN")
      (libsource (lib "eagle-import") (part "TPTHT"))
    )
    (comp (ref "TP12")
      (value "TPTHT")
      (footprint "eagle-import:THT_PIN")
      (libsource (lib "eagle-import") (part "TPTHT"))
    )
    (comp (ref "TP13")
      (value "TPTHT")
      (footprint "eagle-import:THT_PIN")
      (libsource (lib "eagle-import") (part "TPTHT"))
    )
    (comp (ref "TP14")
      (value "TPTHT")
      (footprint "eagle-import:THT_PIN")
      (libsource (lib "eagle-import") (part "TPTHT"))
    )
    (comp (ref "TP15")
      (value "TPTHT")
      (footprint "eagle-import:THT_PIN")
      (libsource (lib "eagle-import") (part "TPTHT"))
    )
    (comp (ref "TP16")
      (value "TPTHT")
      (footprint "eagle-import:THT_PIN")
      (libsource (lib "eagle-import") (part "TPTHT"))
    )
    (comp (ref "TP17")
      (value "TPTHT")
      (footprint "eagle-import:THT_PIN")
      (libsource (lib "eagle-import") (part "TPTHT"))
    )
    (comp (ref "TP18")
      (value "TPTHT")
      (footprint "eagle-import:THT_PIN")
      (libsource (lib "eagle-import") (part "TPTHT"))
    )
    (comp (ref "TP19")
      (value "TPTHT")
      (footprint "eagle-import:THT_PIN")
      (libsource (lib "eagle-import") (part "TPTHT"))
    )
    (comp (ref "TP20")
      (value "TPTHT")
      (footprint "eagle-import:THT_PIN")
      (libsource (lib "eagle-import") (part "TPTHT"))
    )
    (comp (ref "TP21")
      (value "TPTHT")
      (footprint "eagle-import:THT_PIN")
      (libsource (lib "eagle-import") (part "TPTHT"))
    )
    (comp (ref "TP22")
      (value "TPTHT")
      (footprint "eagle-import:THT_PIN")
      (libsource (lib "eagle-import") (part "TPTHT"))
    )
    (comp (ref "TP23")
      (value "TPTHT")
      (footprint "eagle-import:THT_PIN")
      (libsource (lib "eagle-import") (part "TPTHT"))
    )
    (comp (ref "TP24")
      (value "TPTHT")
      (footprint "eagle-import:THT_PIN")
      (libsource (lib "eagle-import") (part "TPTHT"))
    )
    (comp (ref "TP25")
      (value "TPTHT")
      (footprint "eagle-import:THT_PIN")
      (libsource (lib "eagle-import") (part "TPTHT"))
    )
    (comp (ref "TP26")
      (value "TPTHT")
      (footprint "eagle-import:THT_PIN")
      (libsource (lib "eagle-import") (part "TPTHT"))
    )
    (comp (ref "C9")
      (value "100nF")
      (footprint "eagle-import:C0603")
      (libsource (lib "eagle-import") (part "CAPACITOR{dblquote}"))
    )
    (comp (ref "C10")
      (value "100nF")
      (footprint "eagle-import:C0603")
      (libsource (lib "eagle-import") (part "CAPACITOR{dblquote}"))
    )
    (comp (ref "C15")
      (value "100nF")
      (footprint "eagle-import:C0603")
      (libsource (lib "eagle-import") (part "CAPACITOR{dblquote}"))
    )
    (comp (ref "C16")
      (value "100nF")
      (footprint "eagle-import:C0603")
      (libsource (lib "eagle-import") (part "CAPACITOR{dblquote}"))
    )
    (comp (ref "C17")
      (value "100nF")
      (footprint "eagle-import:C0603")
      (libsource (lib "eagle-import") (part "CAPACITOR{dblquote}"))
    )
    (comp (ref "C18")
      (value "100nF")
      (footprint "eagle-import:C0603")
      (libsource (lib "eagle-import") (part "CAPACITOR{dblquote}"))
    )
    (comp (ref "D3")
      (value "4148")
      (footprint "eagle-import:SOD323-R")
      (libsource (lib "eagle-import") (part "4148"))
    )
    (comp (ref "D4")
      (value "4148")
      (footprint "eagle-import:SOD323-R")
      (libsource (lib "eagle-import") (part "4148"))
    )
    (comp (ref "D5")
      (value "4148")
      (footprint "eagle-import:SOD323-R")
      (libsource (lib "eagle-import") (part "4148"))
    )
    (comp (ref "D6")
      (value "4148")
      (footprint "eagle-import:SOD323-R")
      (libsource (lib "eagle-import") (part "4148"))
    )
    (comp (ref "D7")
      (value "4148")
      (footprint "eagle-import:SOD323-R")
      (libsource (lib "eagle-import") (part "4148"))
    )
    (comp (ref "D8")
      (value "4148")
      (footprint "eagle-import:SOD323-R")
      (libsource (lib "eagle-import") (part "4148"))
    )
    (comp (ref "D9")
      (value "4148")
      (footprint "eagle-import:SOD323-R")
      (libsource (lib "eagle-import") (part "4148"))
    )
    (comp (ref "D10")
      (value "4148")
      (footprint "eagle-import:SOD323-R")
      (libsource (lib "eagle-import") (part "4148"))
    )
    (comp (ref "D11")
      (value "4148")
      (footprint "eagle-import:SOD323-R")
      (libsource (lib "eagle-import") (part "4148"))
    )
    (comp (ref "D12")
      (value "4148")
      (footprint "eagle-import:SOD323-R")
      (libsource (lib "eagle-import") (part "4148"))
    )
    (comp (ref "D13")
      (value "4148")
      (footprint "eagle-import:SOD323-R")
      (libsource (lib "eagle-import") (part "4148"))
    )
    (comp (ref "D14")
      (value "4148")
      (footprint "eagle-import:SOD323-R")
      (libsource (lib "eagle-import") (part "4148"))
    )
    (comp (ref "IC2")
      (value "OP275")
      (footprint "eagle-import:SOIC8")
      (libsource (lib "eagle-import") (part "OP275"))
    )
    (comp (ref "IC3")
      (value "OP275")
      (footprint "eagle-import:SOIC8")
      (libsource (lib "eagle-import") (part "OP275"))
    )
    (comp (ref "IC6")
      (value "OP275")
      (footprint "eagle-import:SOIC8")
      (libsource (lib "eagle-import") (part "OP275"))
    )
    (comp (ref "L")
      (value "0R")
      (footprint "eagle-import:R0805")
      (libsource (lib "eagle-import") (part "RESISTOR{dblquote}"))
    )
    (comp (ref "L/M_OUT")
      (value "0R")
      (footprint "eagle-import:R0805")
      (libsource (lib "eagle-import") (part "RESISTOR{dblquote}"))
    )
    (comp (ref "M")
      (value "0R")
      (footprint "eagle-import:R0805")
      (libsource (lib "eagle-import") (part "RESISTOR{dblquote}"))
    )
    (comp (ref "R")
      (value "0R")
      (footprint "eagle-import:R0805")
      (libsource (lib "eagle-import") (part "RESISTOR{dblquote}"))
    )
    (comp (ref "R/S_OUT")
      (value "0R")
      (footprint "eagle-import:R0805")
      (libsource (lib "eagle-import") (part "RESISTOR{dblquote}"))
    )
    (comp (ref "R17")
      (value "100k")
      (footprint "eagle-import:R0805")
      (libsource (lib "eagle-import") (part "RESISTOR{dblquote}"))
    )
    (comp (ref "R18")
      (value "100k")
      (footprint "eagle-import:R0805")
      (libsource (lib "eagle-import") (part "RESISTOR{dblquote}"))
    )
    (comp (ref "R19")
      (value "100k")
      (footprint "eagle-import:R0805")
      (libsource (lib "eagle-import") (part "RESISTOR{dblquote}"))
    )
    (comp (ref "R20")
      (value "100k")
      (footprint "eagle-import:R0805")
      (libsource (lib "eagle-import") (part "RESISTOR{dblquote}"))
    )
    (comp (ref "R21")
      (value "100k")
      (footprint "eagle-import:R0805")
      (libsource (lib "eagle-import") (part "RESISTOR{dblquote}"))
    )
    (comp (ref "R22")
      (value "100k")
      (footprint "eagle-import:R0805")
      (libsource (lib "eagle-import") (part "RESISTOR{dblquote}"))
    )
    (comp (ref "R23")
      (value "100k")
      (footprint "eagle-import:R0805")
      (libsource (lib "eagle-import") (part "RESISTOR{dblquote}"))
    )
    (comp (ref "R24")
      (value "100k")
      (footprint "eagle-import:R0805")
      (libsource (lib "eagle-import") (part "RESISTOR{dblquote}"))
    )
    (comp (ref "R25")
      (value "100k")
      (footprint "eagle-import:R0805")
      (libsource (lib "eagle-import") (part "RESISTOR{dblquote}"))
    )
    (comp (ref "R26")
      (value "100k")
      (footprint "eagle-import:R0805")
      (libsource (lib "eagle-import") (part "RESISTOR{dblquote}"))
    )
    (comp (ref "R27")
      (value "100k")
      (footprint "eagle-import:R0805")
      (libsource (lib "eagle-import") (part "RESISTOR{dblquote}"))
    )
    (comp (ref "R28")
      (value "100k")
      (footprint "eagle-import:R0805")
      (libsource (lib "eagle-import") (part "RESISTOR{dblquote}"))
    )
    (comp (ref "S")
      (value "0R")
      (footprint "eagle-import:R0805")
      (libsource (lib "eagle-import") (part "RESISTOR{dblquote}"))
    )
    (comp (ref "TP01")
      (value "TPTHT")
      (footprint "eagle-import:THT_PIN")
      (libsource (lib "eagle-import") (part "TPTHT"))
    )
    (comp (ref "TP02")
      (value "TPTHT")
      (footprint "eagle-import:THT_PIN")
      (libsource (lib "eagle-import") (part "TPTHT"))
    )
    (comp (ref "TP03")
      (value "TPTHT")
      (footprint "eagle-import:THT_PIN")
      (libsource (lib "eagle-import") (part "TPTHT"))
    )
    (comp (ref "TP04")
      (value "TPTHT")
      (footprint "eagle-import:THT_PIN")
      (libsource (lib "eagle-import") (part "TPTHT"))
    )
    (comp (ref "TP05")
      (value "TPTHT")
      (footprint "eagle-import:THT_PIN")
      (libsource (lib "eagle-import") (part "TPTHT"))
    )
    (comp (ref "TP06")
      (value "TPTHT")
      (footprint "eagle-import:THT_PIN")
      (libsource (lib "eagle-import") (part "TPTHT"))
    )
    (comp (ref "BY_2_1")
      (value "RELAY_EE2-5NU")
      (footprint "eagle-import:351")
      (fields (field (name "MF") "KEMET") (field (name "MPN") "EE2-5NU"))
      (libsource (lib "eagle-import") (part "RELAY_EE2-5NU"))
    )
    (comp (ref "BY_2_2")
      (value "RELAY_EE2-5NU")
      (footprint "eagle-import:351")
      (fields (field (name "MF") "KEMET") (field (name "MPN") "EE2-5NU"))
      (libsource (lib "eagle-import") (part "RELAY_EE2-5NU"))
    )
    (comp (ref "C1")
      (value "100nF")
      (footprint "eagle-import:C0603")
      (libsource (lib "eagle-import") (part "CAPACITOR{dblquote}"))
    )
    (comp (ref "C2")
      (value "100nF")
      (footprint "eagle-import:C0603")
      (libsource (lib "eagle-import") (part "CAPACITOR{dblquote}"))
    )
    (comp (ref "C11")
      (value "100nF")
      (footprint "eagle-import:C0603")
      (libsource (lib "eagle-import") (part "CAPACITOR{dblquote}"))
    )
    (comp (ref "C12")
      (value "100nF")
      (footprint "eagle-import:C0603")
      (libsource (lib "eagle-import") (part "CAPACITOR{dblquote}"))
    )
    (comp (ref "IN2(L/M)")
      (value "NEUTRIK_NC3FAH")
      (footprint "eagle-import:NEUTRIK_NC3FAH")
      (libsource (lib "eagle-import") (part "NEUTRIK_NC3FAH"))
    )
    (comp (ref "IN_LEFT")
      (value "1240")
      (footprint "eagle-import:SO08")
      (libsource (lib "eagle-import") (part "THAT1240SO8-U"))
    )
    (comp (ref "OUT2(L/M)")
      (value "NEUTRIK_NC3MAH")
      (footprint "eagle-import:NEUTRIK_NC3MAH")
      (libsource (lib "eagle-import") (part "NEUTRIK_NC3MAH"))
    )
    (comp (ref "OUT_LEFT")
      (value "1646")
      (footprint "eagle-import:SO08")
      (libsource (lib "eagle-import") (part "THAT1646SO8-U"))
    )
    (comp (ref "C53")
      (value "100nF")
      (footprint "eagle-import:C0603")
      (libsource (lib "eagle-import") (part "CAPACITOR{dblquote}"))
    )
    (comp (ref "C54")
      (value "100nF")
      (footprint "eagle-import:C0603")
      (libsource (lib "eagle-import") (part "CAPACITOR{dblquote}"))
    )
    (comp (ref "C55")
      (value "22pF")
      (footprint "eagle-import:C0603")
      (libsource (lib "eagle-import") (part "CAPACITOR{dblquote}"))
    )
    (comp (ref "C56")
      (value "22pF")
      (footprint "eagle-import:C0603")
      (libsource (lib "eagle-import") (part "CAPACITOR{dblquote}"))
    )
    (comp (ref "C57")
      (value "100nF")
      (footprint "eagle-import:C0603")
      (libsource (lib "eagle-import") (part "CAPACITOR{dblquote}"))
    )
    (comp (ref "C58")
      (value "100nF")
      (footprint "eagle-import:C0603")
      (libsource (lib "eagle-import") (part "CAPACITOR{dblquote}"))
    )
    (comp (ref "C59")
      (value "22pF")
      (footprint "eagle-import:C0603")
      (libsource (lib "eagle-import") (part "CAPACITOR{dblquote}"))
    )
    (comp (ref "C60")
      (value "100nF")
      (footprint "eagle-import:C0603")
      (libsource (lib "eagle-import") (part "CAPACITOR{dblquote}"))
    )
    (comp (ref "C61")
      (value "100nF")
      (footprint "eagle-import:C0603")
      (libsource (lib "eagle-import") (part "CAPACITOR{dblquote}"))
    )
    (comp (ref "C62")
      (value "100nF")
      (footprint "eagle-import:C0603")
      (libsource (lib "eagle-import") (part "CAPACITOR{dblquote}"))
    )
    (comp (ref "C63")
      (value "100nF")
      (footprint "eagle-import:C0603")
      (libsource (lib "eagle-import") (part "CAPACITOR{dblquote}"))
    )
    (comp (ref "C64")
      (value "22pF")
      (footprint "eagle-import:C0603")
      (libsource (lib "eagle-import") (part "CAPACITOR{dblquote}"))
    )
    (comp (ref "C67")
      (value "47µF")
      (footprint "eagle-import:153CLV-0605")
      (libsource (lib "eagle-import") (part "SMD_ELCTROLYTIC"))
    )
    (comp (ref "C68")
      (value "47µF")
      (footprint "eagle-import:153CLV-0605")
      (libsource (lib "eagle-import") (part "SMD_ELCTROLYTIC"))
    )
    (comp (ref "C69")
      (value "2.2µF")
      (footprint "eagle-import:153CLV-0605")
      (libsource (lib "eagle-import") (part "SMD_ELCTROLYTIC"))
    )
    (comp (ref "C70")
      (value "2.2µF")
      (footprint "eagle-import:153CLV-0605")
      (libsource (lib "eagle-import") (part "SMD_ELCTROLYTIC"))
    )
    (comp (ref "IC8")
      (value "OP275")
      (footprint "eagle-import:SOIC8")
      (libsource (lib "eagle-import") (part "OP275"))
    )
    (comp (ref "IC9")
      (value "TL072")
      (footprint "eagle-import:SOIC8")
      (libsource (lib "eagle-import") (part "TL072"))
    )
    (comp (ref "R14")
      (value "0R")
      (footprint "eagle-import:R0805")
      (libsource (lib "eagle-import") (part "RESISTOR{dblquote}"))
    )
    (comp (ref "R29")
      (value "0R")
      (footprint "eagle-import:R0805")
      (libsource (lib "eagle-import") (part "RESISTOR{dblquote}"))
    )
    (comp (ref "R48")
      (value "10k")
      (footprint "eagle-import:R0805")
      (libsource (lib "eagle-import") (part "RESISTOR{dblquote}"))
    )
    (comp (ref "R49")
      (value "10k")
      (footprint "eagle-import:R0805")
      (libsource (lib "eagle-import") (part "RESISTOR{dblquote}"))
    )
    (comp (ref "R50")
      (value "5k1")
      (footprint "eagle-import:R0805")
      (libsource (lib "eagle-import") (part "RESISTOR{dblquote}"))
    )
    (comp (ref "R51")
      (value "5k1")
      (footprint "eagle-import:R0805")
      (libsource (lib "eagle-import") (part "RESISTOR{dblquote}"))
    )
    (comp (ref "R52")
      (value "20k")
      (footprint "eagle-import:R0805")
      (libsource (lib "eagle-import") (part "RESISTOR{dblquote}"))
    )
    (comp (ref "R53")
      (value "20k")
      (footprint "eagle-import:R0805")
      (libsource (lib "eagle-import") (part "RESISTOR{dblquote}"))
    )
    (comp (ref "R54")
      (value "2k00")
      (footprint "eagle-import:R0805")
      (libsource (lib "eagle-import") (part "RESISTOR{dblquote}"))
    )
    (comp (ref "R55")
      (value "178k")
      (footprint "eagle-import:R0805")
      (libsource (lib "eagle-import") (part "RESISTOR{dblquote}"))
    )
    (comp (ref "R56")
      (value "6k49")
      (footprint "eagle-import:R0805")
      (libsource (lib "eagle-import") (part "RESISTOR{dblquote}"))
    )
    (comp (ref "R57")
      (value "6k34")
      (footprint "eagle-import:R0805")
      (libsource (lib "eagle-import") (part "RESISTOR{dblquote}"))
    )
    (comp (ref "R58")
      (value "2k00")
      (footprint "eagle-import:R0805")
      (libsource (lib "eagle-import") (part "RESISTOR{dblquote}"))
    )
    (comp (ref "R59")
      (value "6k49")
      (footprint "eagle-import:R0805")
      (libsource (lib "eagle-import") (part "RESISTOR{dblquote}"))
    )
    (comp (ref "R60")
      (value "6k34")
      (footprint "eagle-import:R0805")
      (libsource (lib "eagle-import") (part "RESISTOR{dblquote}"))
    )
    (comp (ref "R61")
      (value "178k")
      (footprint "eagle-import:R0805")
      (libsource (lib "eagle-import") (part "RESISTOR{dblquote}"))
    )
    (comp (ref "R62")
      (value "51R")
      (footprint "eagle-import:R0805")
      (libsource (lib "eagle-import") (part "RESISTOR{dblquote}"))
    )
    (comp (ref "R63")
      (value "90k9")
      (footprint "eagle-import:R0805")
      (libsource (lib "eagle-import") (part "RESISTOR{dblquote}"))
    )
    (comp (ref "R64")
      (value "51k")
      (footprint "eagle-import:R0805")
      (libsource (lib "eagle-import") (part "RESISTOR{dblquote}"))
    )
    (comp (ref "R65")
      (value "90k9")
      (footprint "eagle-import:R0805")
      (libsource (lib "eagle-import") (part "RESISTOR{dblquote}"))
    )
    (comp (ref "R66")
      (value "51k")
      (footprint "eagle-import:R0805")
      (libsource (lib "eagle-import") (part "RESISTOR{dblquote}"))
    )
    (comp (ref "R67")
      (value "51R")
      (footprint "eagle-import:R0805")
      (libsource (lib "eagle-import") (part "RESISTOR{dblquote}"))
    )
    (comp (ref "TP36")
      (value "TPTHT")
      (footprint "eagle-import:THT_PIN")
      (libsource (lib "eagle-import") (part "TPTHT"))
    )
    (comp (ref "TP37")
      (value "TPTHT")
      (footprint "eagle-import:THT_PIN")
      (libsource (lib "eagle-import") (part "TPTHT"))
    )
    (comp (ref "VCA1(LEFT)")
      (value "THAT2181S")
      (footprint "eagle-import:SO08")
      (libsource (lib "eagle-import") (part "THAT2181S"))
    )
    (comp (ref "VCA2(RIGHT)")
      (value "THAT2181S")
      (footprint "eagle-import:SO08")
      (libsource (lib "eagle-import") (part "THAT2181S"))
    )
    (comp (ref "C20")
      (value "100nF")
      (footprint "eagle-import:C0603")
      (libsource (lib "eagle-import") (part "CAPACITOR{dblquote}"))
    )
    (comp (ref "C44")
      (value "22pF")
      (footprint "eagle-import:C0603")
      (libsource (lib "eagle-import") (part "CAPACITOR{dblquote}"))
    )
    (comp (ref "C45")
      (value "22pF")
      (footprint "eagle-import:C0603")
      (libsource (lib "eagle-import") (part "CAPACITOR{dblquote}"))
    )
    (comp (ref "C46")
      (value "22pF")
      (footprint "eagle-import:C0603")
      (libsource (lib "eagle-import") (part "CAPACITOR{dblquote}"))
    )
    (comp (ref "C47")
      (value "100nF")
      (footprint "eagle-import:C0603")
      (libsource (lib "eagle-import") (part "CAPACITOR{dblquote}"))
    )
    (comp (ref "C48")
      (value "100nF")
      (footprint "eagle-import:C0603")
      (libsource (lib "eagle-import") (part "CAPACITOR{dblquote}"))
    )
    (comp (ref "C49")
      (value "100nF")
      (footprint "eagle-import:C0603")
      (libsource (lib "eagle-import") (part "CAPACITOR{dblquote}"))
    )
    (comp (ref "C50")
      (value "100nF")
      (footprint "eagle-import:C0603")
      (libsource (lib "eagle-import") (part "CAPACITOR{dblquote}"))
    )
    (comp (ref "CONN1")
      (value "10PIN_HEADER_SMD")
      (footprint "eagle-import:87832-10")
      (libsource (lib "eagle-import") (part "10PIN_HEADER_SMD"))
    )
    (comp (ref "D2")
      (value "Shotky-CD1206")
      (footprint "eagle-import:SOD323-R")
      (libsource (lib "eagle-import") (part "4148"))
    )
    (comp (ref "QA4")
      (value "16 MHz")
      (footprint "eagle-import:SM49")
      (libsource (lib "eagle-import") (part "CRYSTAL_SM49"))
    )
    (comp (ref "R32")
      (value "1k")
      (footprint "eagle-import:R0805")
      (libsource (lib "eagle-import") (part "RESISTOR{dblquote}"))
    )
    (comp (ref "R46")
      (value "1M")
      (footprint "eagle-import:R0805")
      (libsource (lib "eagle-import") (part "RESISTOR{dblquote}"))
    )
    (comp (ref "R47")
      (value "1M")
      (footprint "eagle-import:R0805")
      (libsource (lib "eagle-import") (part "RESISTOR{dblquote}"))
    )
    (comp (ref "R68")
      (value "1k")
      (footprint "eagle-import:R0805")
      (libsource (lib "eagle-import") (part "RESISTOR{dblquote}"))
    )
    (comp (ref "TP27")
      (value "TPTHT")
      (footprint "eagle-import:THT_PIN")
      (libsource (lib "eagle-import") (part "TPTHT"))
    )
    (comp (ref "TP28")
      (value "TPTHT")
      (footprint "eagle-import:THT_PIN")
      (libsource (lib "eagle-import") (part "TPTHT"))
    )
    (comp (ref "TP29")
      (value "TPTHT")
      (footprint "eagle-import:THT_PIN")
      (libsource (lib "eagle-import") (part "TPTHT"))
    )
    (comp (ref "TP30")
      (value "TPTHT")
      (footprint "eagle-import:THT_PIN")
      (libsource (lib "eagle-import") (part "TPTHT"))
    )
    (comp (ref "TP31")
      (value "TPTHT")
      (footprint "eagle-import:THT_PIN")
      (libsource (lib "eagle-import") (part "TPTHT"))
    )
    (comp (ref "TP32")
      (value "TPTHT")
      (footprint "eagle-import:THT_PIN")
      (libsource (lib "eagle-import") (part "TPTHT"))
    )
    (comp (ref "TP33")
      (value "TPTHT")
      (footprint "eagle-import:THT_PIN")
      (libsource (lib "eagle-import") (part "TPTHT"))
    )
    (comp (ref "TP34")
      (value "TPTHT")
      (footprint "eagle-import:THT_PIN")
      (libsource (lib "eagle-import") (part "TPTHT"))
    )
    (comp (ref "U1")
      (value "ATMEGA2560-16AU")
      (footprint "eagle-import:QFP50P1600X1600X120-100N")
      (libsource (lib "eagle-import") (part "ATMEGA2560-16AU"))
    )
    (comp (ref "U1_PROG")
      (value "MAIN_µC")
      (footprint "eagle-import:6PIN_HEADER_SMD_OPEN")
      (libsource (lib "eagle-import") (part "6PIN_HEADER_SMD_OPEN"))
    )
    (comp (ref "C5")
      (value "100nF")
      (footprint "eagle-import:C0603")
      (libsource (lib "eagle-import") (part "CAPACITOR{dblquote}"))
    )
    (comp (ref "C6")
      (value "100nF")
      (footprint "eagle-import:C0603")
      (libsource (lib "eagle-import") (part "CAPACITOR{dblquote}"))
    )
    (comp (ref "C21")
      (value "100nF")
      (footprint "eagle-import:C0603")
      (libsource (lib "eagle-import") (part "CAPACITOR{dblquote}"))
    )
    (comp (ref "C22")
      (value "100nF")
      (footprint "eagle-import:C0603")
      (libsource (lib "eagle-import") (part "CAPACITOR{dblquote}"))
    )
    (comp (ref "C25")
      (value "100nF")
      (footprint "eagle-import:C0603")
      (libsource (lib "eagle-import") (part "CAPACITOR{dblquote}"))
    )
    (comp (ref "C26")
      (value "100nF")
      (footprint "eagle-import:C0603")
      (libsource (lib "eagle-import") (part "CAPACITOR{dblquote}"))
    )
    (comp (ref "IC4")
      (value "OP275")
      (footprint "eagle-import:SOIC8")
      (libsource (lib "eagle-import") (part "OP275"))
    )
    (comp (ref "K5")
      (value "RELAY_EE2-5NU")
      (footprint "eagle-import:351")
      (fields (field (name "MF") "KEMET") (field (name "MPN") "EE2-5NU"))
      (libsource (lib "eagle-import") (part "RELAY_EE2-5NU"))
    )
    (comp (ref "U4")
      (value "THAT1240")
      (footprint "eagle-import:SO08")
      (libsource (lib "eagle-import") (part "THAT1240SO8-U"))
    )
    (comp (ref "U6")
      (value "THAT1240")
      (footprint "eagle-import:SO08")
      (libsource (lib "eagle-import") (part "THAT1240SO8-U"))
    )
    (comp (ref "C33")
      (value "22pF")
      (footprint "eagle-import:C0603")
      (libsource (lib "eagle-import") (part "CAPACITOR{dblquote}"))
    )
    (comp (ref "C34")
      (value "22pF")
      (footprint "eagle-import:C0603")
      (libsource (lib "eagle-import") (part "CAPACITOR{dblquote}"))
    )
    (comp (ref "C35")
      (value "1uF")
      (footprint "eagle-import:C0603")
      (libsource (lib "eagle-import") (part "CAPACITOR{dblquote}"))
    )
    (comp (ref "C36")
      (value "4,7uF/16V")
      (footprint "eagle-import:153CLV-0605")
      (libsource (lib "eagle-import") (part "SMD_ELCTROLYTIC"))
    )
    (comp (ref "C37")
      (value "100nF")
      (footprint "eagle-import:C0603")
      (libsource (lib "eagle-import") (part "CAPACITOR{dblquote}"))
    )
    (comp (ref "C38")
      (value "22pF")
      (footprint "eagle-import:C0603")
      (libsource (lib "eagle-import") (part "CAPACITOR{dblquote}"))
    )
    (comp (ref "C39")
      (value "22pF")
      (footprint "eagle-import:C0603")
      (libsource (lib "eagle-import") (part "CAPACITOR{dblquote}"))
    )
    (comp (ref "C40")
      (value "1uF")
      (footprint "eagle-import:C0603")
      (libsource (lib "eagle-import") (part "CAPACITOR{dblquote}"))
    )
    (comp (ref "C41")
      (value "4,7uF/16V")
      (footprint "eagle-import:153CLV-0605")
      (libsource (lib "eagle-import") (part "SMD_ELCTROLYTIC"))
    )
    (comp (ref "C42")
      (value "100nF")
      (footprint "eagle-import:C0603")
      (libsource (lib "eagle-import") (part "CAPACITOR{dblquote}"))
    )
    (comp (ref "C51")
      (value "1uF")
      (footprint "eagle-import:C0603")
      (libsource (lib "eagle-import") (part "CAPACITOR{dblquote}"))
    )
    (comp (ref "C52")
      (value "100nF")
      (footprint "eagle-import:C0603")
      (libsource (lib "eagle-import") (part "CAPACITOR{dblquote}"))
    )
    (comp (ref "C65")
      (value "100nF")
      (footprint "eagle-import:C0603")
      (libsource (lib "eagle-import") (part "CAPACITOR{dblquote}"))
    )
    (comp (ref "C66")
      (value "100nF")
      (footprint "eagle-import:C0603")
      (libsource (lib "eagle-import") (part "CAPACITOR{dblquote}"))
    )
    (comp (ref "DAC1")
      (value "MCP4922")
      (footprint "eagle-import:SOIC16")
      (libsource (lib "eagle-import") (part "MCP4922"))
    )
    (comp (ref "DAC2")
      (value "MCP4922")
      (footprint "eagle-import:SOIC16")
      (libsource (lib "eagle-import") (part "MCP4922"))
    )
    (comp (ref "QA2")
      (value "16 MHz")
      (footprint "eagle-import:SM49")
      (libsource (lib "eagle-import") (part "CRYSTAL_SM49"))
    )
    (comp (ref "QA3")
      (value "16 MHz")
      (footprint "eagle-import:SM49")
      (libsource (lib "eagle-import") (part "CRYSTAL_SM49"))
    )
    (comp (ref "R13")
      (value "0R")
      (footprint "eagle-import:R0805")
      (libsource (lib "eagle-import") (part "RESISTOR{dblquote}"))
    )
    (comp (ref "R15")
      (value "1M")
      (footprint "eagle-import:R0805")
      (libsource (lib "eagle-import") (part "RESISTOR{dblquote}"))
    )
    (comp (ref "R16")
      (value "10k")
      (footprint "eagle-import:R0805")
      (libsource (lib "eagle-import") (part "RESISTOR{dblquote}"))
    )
    (comp (ref "R30")
      (value "10k")
      (footprint "eagle-import:R0805")
      (libsource (lib "eagle-import") (part "RESISTOR{dblquote}"))
    )
    (comp (ref "R31")
      (value "10k")
      (footprint "eagle-import:R0805")
      (libsource (lib "eagle-import") (part "RESISTOR{dblquote}"))
    )
    (comp (ref "R33")
      (value "1M")
      (footprint "eagle-import:R0805")
      (libsource (lib "eagle-import") (part "RESISTOR{dblquote}"))
    )
    (comp (ref "R34")
      (value "10k")
      (footprint "eagle-import:R0805")
      (libsource (lib "eagle-import") (part "RESISTOR{dblquote}"))
    )
    (comp (ref "R35")
      (value "500R")
      (footprint "eagle-import:R0805")
      (libsource (lib "eagle-import") (part "RESISTOR{dblquote}"))
    )
    (comp (ref "R36")
      (value "500R")
      (footprint "eagle-import:R0805")
      (libsource (lib "eagle-import") (part "RESISTOR{dblquote}"))
    )
    (comp (ref "R37")
      (value "500R")
      (footprint "eagle-import:R0805")
      (libsource (lib "eagle-import") (part "RESISTOR{dblquote}"))
    )
    (comp (ref "R38")
      (value "500R")
      (footprint "eagle-import:R0805")
      (libsource (lib "eagle-import") (part "RESISTOR{dblquote}"))
    )
    (comp (ref "R39")
      (value "500R")
      (footprint "eagle-import:R0805")
      (libsource (lib "eagle-import") (part "RESISTOR{dblquote}"))
    )
    (comp (ref "R40")
      (value "500R")
      (footprint "eagle-import:R0805")
      (libsource (lib "eagle-import") (part "RESISTOR{dblquote}"))
    )
    (comp (ref "R41")
      (value "1K")
      (footprint "eagle-import:R0805")
      (libsource (lib "eagle-import") (part "RESISTOR{dblquote}"))
    )
    (comp (ref "R42")
      (value "1K")
      (footprint "eagle-import:R0805")
      (libsource (lib "eagle-import") (part "RESISTOR{dblquote}"))
    )
    (comp (ref "R43")
      (value "1K")
      (footprint "eagle-import:R0805")
      (libsource (lib "eagle-import") (part "RESISTOR{dblquote}"))
    )
    (comp (ref "R44")
      (value "1K")
      (footprint "eagle-import:R0805")
      (libsource (lib "eagle-import") (part "RESISTOR{dblquote}"))
    )
    (comp (ref "TP35")
      (value "TPTHT")
      (footprint "eagle-import:THT_PIN")
      (libsource (lib "eagle-import") (part "TPTHT"))
    )
    (comp (ref "U10")
      (value "ATMEGA328P-AU")
      (footprint "eagle-import:QFP80P900X900X120-32N")
      (libsource (lib "eagle-import") (part "ATMEGA328P-AU"))
    )
    (comp (ref "U10_PROG")
      (value "6PIN_HEADER_SMD_OPEN")
      (footprint "eagle-import:6PIN_HEADER_SMD_OPEN")
      (libsource (lib "eagle-import") (part "6PIN_HEADER_SMD_OPEN"))
    )
    (comp (ref "U11")
      (value "ATMEGA328P-AU")
      (footprint "eagle-import:QFP80P900X900X120-32N")
      (libsource (lib "eagle-import") (part "ATMEGA328P-AU"))
    )
    (comp (ref "U11_PROG")
      (value "6PIN_HEADER_SMD_OPEN")
      (footprint "eagle-import:6PIN_HEADER_SMD_OPEN")
      (libsource (lib "eagle-import") (part "6PIN_HEADER_SMD_OPEN"))
    )
    (comp (ref "UR1")
      (value "78")
      (footprint "eagle-import:TO252")
      (libsource (lib "eagle-import") (part "78"))
    )
    (comp (ref "C7")
      (value "100nF")
      (footprint "eagle-import:C0603")
      (libsource (lib "eagle-import") (part "CAPACITOR{dblquote}"))
    )
    (comp (ref "C8")
      (value "100nF")
      (footprint "eagle-import:C0603")
      (libsource (lib "eagle-import") (part "CAPACITOR{dblquote}"))
    )
    (comp (ref "C27")
      (value "100nF")
      (footprint "eagle-import:C0603")
      (libsource (lib "eagle-import") (part "CAPACITOR{dblquote}"))
    )
    (comp (ref "C28")
      (value "100nF")
      (footprint "eagle-import:C0603")
      (libsource (lib "eagle-import") (part "CAPACITOR{dblquote}"))
    )
    (comp (ref "C29")
      (value "100nF")
      (footprint "eagle-import:C0603")
      (libsource (lib "eagle-import") (part "CAPACITOR{dblquote}"))
    )
    (comp (ref "C30")
      (value "100nF")
      (footprint "eagle-import:C0603")
      (libsource (lib "eagle-import") (part "CAPACITOR{dblquote}"))
    )
    (comp (ref "IC1")
      (value "OP275")
      (footprint "eagle-import:SOIC8")
      (libsource (lib "eagle-import") (part "OP275"))
    )
    (comp (ref "K6")
      (value "RELAY_EE2-5NU")
      (footprint "eagle-import:351")
      (fields (field (name "MF") "KEMET") (field (name "MPN") "EE2-5NU"))
      (libsource (lib "eagle-import") (part "RELAY_EE2-5NU"))
    )
    (comp (ref "K7")
      (value "RELAY_EE2-5NU")
      (footprint "eagle-import:351")
      (fields (field (name "MF") "KEMET") (field (name "MPN") "EE2-5NU"))
      (libsource (lib "eagle-import") (part "RELAY_EE2-5NU"))
    )
    (comp (ref "K8")
      (value "RELAY_EE2-5NU")
      (footprint "eagle-import:351")
      (fields (field (name "MF") "KEMET") (field (name "MPN") "EE2-5NU"))
      (libsource (lib "eagle-import") (part "RELAY_EE2-5NU"))
    )
    (comp (ref "U7")
      (value "THAT1240")
      (footprint "eagle-import:SO08")
      (libsource (lib "eagle-import") (part "THAT1240SO8-U"))
    )
    (comp (ref "U8")
      (value "THAT1240")
      (footprint "eagle-import:SO08")
      (libsource (lib "eagle-import") (part "THAT1240SO8-U"))
    )
    (comp (ref "BY_1_1")
      (value "RELAY_EE2-5NU")
      (footprint "eagle-import:351")
      (fields (field (name "MF") "KEMET") (field (name "MPN") "EE2-5NU"))
      (libsource (lib "eagle-import") (part "RELAY_EE2-5NU"))
    )
    (comp (ref "BY_1_2")
      (value "RELAY_EE2-5NU")
      (footprint "eagle-import:351")
      (fields (field (name "MF") "KEMET") (field (name "MPN") "EE2-5NU"))
      (libsource (lib "eagle-import") (part "RELAY_EE2-5NU"))
    )
    (comp (ref "C3")
      (value "100nF")
      (footprint "eagle-import:C0603")
      (libsource (lib "eagle-import") (part "CAPACITOR{dblquote}"))
    )
    (comp (ref "C4")
      (value "100nF")
      (footprint "eagle-import:C0603")
      (libsource (lib "eagle-import") (part "CAPACITOR{dblquote}"))
    )
    (comp (ref "C13")
      (value "100nF")
      (footprint "eagle-import:C0603")
      (libsource (lib "eagle-import") (part "CAPACITOR{dblquote}"))
    )
    (comp (ref "C14")
      (value "100nF")
      (footprint "eagle-import:C0603")
      (libsource (lib "eagle-import") (part "CAPACITOR{dblquote}"))
    )
    (comp (ref "IN1(R/S)")
      (value "NEUTRIK_NC3FAH")
      (footprint "eagle-import:NEUTRIK_NC3FAH")
      (libsource (lib "eagle-import") (part "NEUTRIK_NC3FAH"))
    )
    (comp (ref "IN_RIGHT")
      (value "1240")
      (footprint "eagle-import:SO08")
      (libsource (lib "eagle-import") (part "THAT1240SO8-U"))
    )
    (comp (ref "OUT1(R/S)")
      (value "NEUTRIK_NC3MAH")
      (footprint "eagle-import:NEUTRIK_NC3MAH")
      (libsource (lib "eagle-import") (part "NEUTRIK_NC3MAH"))
    )
    (comp (ref "OUT_RIGHT")
      (value "1646")
      (footprint "eagle-import:SO08")
      (libsource (lib "eagle-import") (part "THAT1646SO8-U"))
    )
    (comp (ref "C19")
      (value "100nF")
      (footprint "eagle-import:C0603")
      (libsource (lib "eagle-import") (part "CAPACITOR{dblquote}"))
    )
    (comp (ref "C23")
      (value "22pF")
      (footprint "eagle-import:C0603")
      (libsource (lib "eagle-import") (part "CAPACITOR{dblquote}"))
    )
    (comp (ref "C24")
      (value "22pF")
      (footprint "eagle-import:C0603")
      (libsource (lib "eagle-import") (part "CAPACITOR{dblquote}"))
    )
    (comp (ref "C31")
      (value "1uF")
      (footprint "eagle-import:C0603")
      (libsource (lib "eagle-import") (part "CAPACITOR{dblquote}"))
    )
    (comp (ref "C32")
      (value "100nF")
      (footprint "eagle-import:C0603")
      (libsource (lib "eagle-import") (part "CAPACITOR{dblquote}"))
    )
    (comp (ref "C43")
      (value "100nF")
      (footprint "eagle-import:C0603")
      (libsource (lib "eagle-import") (part "CAPACITOR{dblquote}"))
    )
    (comp (ref "D1")
      (value "Shotky-CD1206")
      (footprint "eagle-import:SOD323-R")
      (libsource (lib "eagle-import") (part "4148"))
    )
    (comp (ref "F1")
      (value "FUSE_500 mA")
      (footprint "eagle-import:RESETABLE-FUSE")
      (libsource (lib "eagle-import") (part "RESTABLE_FUSE"))
    )
    (comp (ref "Q1")
      (value "BLM21")
      (footprint "eagle-import:RESC2012X85")
      (libsource (lib "eagle-import") (part "FERITEFERITE"))
    )
    (comp (ref "QA1")
      (value "16 MHz")
      (footprint "eagle-import:SM49")
      (libsource (lib "eagle-import") (part "CRYSTAL_SM49"))
    )
    (comp (ref "R1")
      (value "22R")
      (footprint "eagle-import:R0805")
      (libsource (lib "eagle-import") (part "RESISTOR{dblquote}"))
    )
    (comp (ref "R2")
      (value "22R")
      (footprint "eagle-import:R0805")
      (libsource (lib "eagle-import") (part "RESISTOR{dblquote}"))
    )
    (comp (ref "R3")
      (value "1M")
      (footprint "eagle-import:R0805")
      (libsource (lib "eagle-import") (part "RESISTOR{dblquote}"))
    )
    (comp (ref "R4")
      (value "1M")
      (footprint "eagle-import:R0805")
      (libsource (lib "eagle-import") (part "RESISTOR{dblquote}"))
    )
    (comp (ref "R5")
      (value "1k")
      (footprint "eagle-import:R0805")
      (libsource (lib "eagle-import") (part "RESISTOR{dblquote}"))
    )
    (comp (ref "R6")
      (value "1k")
      (footprint "eagle-import:R0805")
      (libsource (lib "eagle-import") (part "RESISTOR{dblquote}"))
    )
    (comp (ref "R45")
      (value "1k")
      (footprint "eagle-import:R0805")
      (libsource (lib "eagle-import") (part "RESISTOR{dblquote}"))
    )
    (comp (ref "U5")
      (value "ATMEGA16U2-AU")
      (footprint "eagle-import:QFP80P900X900X120-32N")
      (libsource (lib "eagle-import") (part "ATMEGA16U2-AU"))
    )
    (comp (ref "U5_PROG")
      (value "6PIN_HEADER_SMD_OPEN")
      (footprint "eagle-import:6PIN_HEADER_SMD_OPEN")
      (libsource (lib "eagle-import") (part "6PIN_HEADER_SMD_OPEN"))
    )
    (comp (ref "USB1")
      (value "SMARTPRJ_PN61729")
      (footprint "eagle-import:SMARTPRJ_PN61729")
      (libsource (lib "eagle-import") (part "SMARTPRJ_PN61729"))
    )
    (comp (ref "V1")
      (value "CG0603ML")
      (footprint "eagle-import:VARC2513X70")
      (libsource (lib "eagle-import") (part "VARISTORVAR-0603"))
    )
    (comp (ref "V2")
      (value "CG0603ML")
      (footprint "eagle-import:VARC2513X70")
      (libsource (lib "eagle-import") (part "VARISTORVAR-0603"))
    )
    (comp (ref "L1")
      (value "SMD_LED_0603")
      (footprint "eagle-import:WL-SMCW_0603")
      (libsource (lib "eagle-import") (part "SMD_LED_0603"))
    )
    (comp (ref "L2")
      (value "SMD_LED_0603")
      (footprint "eagle-import:WL-SMCW_0603")
      (libsource (lib "eagle-import") (part "SMD_LED_0603"))
    )
    (comp (ref "L3")
      (value "SMD_LED_0603")
      (footprint "eagle-import:WL-SMCW_0603")
      (libsource (lib "eagle-import") (part "SMD_LED_0603"))
    )
    (comp (ref "L4")
      (value "SMD_LED_0603")
      (footprint "eagle-import:WL-SMCW_0603")
      (libsource (lib "eagle-import") (part "SMD_LED_0603"))
    )
    (comp (ref "L5")
      (value "SMD_LED_0603")
      (footprint "eagle-import:WL-SMCW_0603")
      (libsource (lib "eagle-import") (part "SMD_LED_0603"))
    )
    (comp (ref "L6")
      (value "SMD_LED_0603")
      (footprint "eagle-import:WL-SMCW_0603")
      (libsource (lib "eagle-import") (part "SMD_LED_0603"))
    )
    (comp (ref "R7")
      (value "500R")
      (footprint "eagle-import:R0805")
      (libsource (lib "eagle-import") (part "RESISTOR{dblquote}"))
    )
    (comp (ref "R8")
      (value "500R")
      (footprint "eagle-import:R0805")
      (libsource (lib "eagle-import") (part "RESISTOR{dblquote}"))
    )
    (comp (ref "R9")
      (value "500R")
      (footprint "eagle-import:R0805")
      (libsource (lib "eagle-import") (part "RESISTOR{dblquote}"))
    )
    (comp (ref "R10")
      (value "500R")
      (footprint "eagle-import:R0805")
      (libsource (lib "eagle-import") (part "RESISTOR{dblquote}"))
    )
    (comp (ref "R11")
      (value "500R")
      (footprint "eagle-import:R0805")
      (libsource (lib "eagle-import") (part "RESISTOR{dblquote}"))
    )
    (comp (ref "R12")
      (value "500R")
      (footprint "eagle-import:R0805")
      (libsource (lib "eagle-import") (part "RESISTOR{dblquote}"))
    )
    (comp (ref "U12")
      (value "ULN2003")
      (footprint "eagle-import:SOIC16")
      (libsource (lib "eagle-import") (part "ULN2003"))
    )
  )
  (nets
    (net (code "1") (name "+5V") (class "Default")
      (node (ref "BY_1_1") (pin "1") (pinfunction "1_1") (pintype "passive"))
      (node (ref "BY_1_2") (pin "1") (pinfunction "1_1") (pintype "passive"))
      (node (ref "BY_2_1") (pin "1") (pinfunction "1_1") (pintype "passive"))
      (node (ref "BY_2_2") (pin "1") (pinfunction "1_1") (pintype "passive"))
      (node (ref "C19") (pin "1") (pinfunction "1_1") (pintype "passive"))
      (node (ref "C20") (pin "1") (pinfunction "1_1") (pintype "passive"))
      (node (ref "C35") (pin "2") (pinfunction "2_2") (pintype "passive"))
      (node (ref "C36") (pin "+") (pinfunction "+_+") (pintype "passive"))
      (node (ref "C40") (pin "2") (pinfunction "2_2") (pintype "passive"))
      (node (ref "C41") (pin "+") (pinfunction "+_+") (pintype "passive"))
      (node (ref "C47") (pin "1") (pinfunction "1_1") (pintype "passive"))
      (node (ref "C48") (pin "1") (pinfunction "1_1") (pintype "passive"))
      (node (ref "C49") (pin "1") (pinfunction "1_1") (pintype "passive"))
      (node (ref "CONN1") (pin "1") (pinfunction "P$1_1") (pintype "bidirectional"))
      (node (ref "CONN1") (pin "2") (pinfunction "P$2_2") (pintype "bidirectional"))
      (node (ref "CONN1") (pin "3") (pinfunction "P$3_3") (pintype "bidirectional"))
      (node (ref "CONN2") (pin "1") (pinfunction "KL_1") (pintype "passive"))
      (node (ref "D1") (pin "C") (pinfunction "C_C") (pintype "passive"))
      (node (ref "D2") (pin "C") (pinfunction "C_C") (pintype "passive"))
      (node (ref "DAC1") (pin "9") (pinfunction "SHDN_9") (pintype "input"))
      (node (ref "DAC2") (pin "9") (pinfunction "SHDN_9") (pintype "input"))
      (node (ref "K5") (pin "1") (pinfunction "1_1") (pintype "passive"))
      (node (ref "K6") (pin "1") (pinfunction "1_1") (pintype "passive"))
      (node (ref "K7") (pin "1") (pinfunction "1_1") (pintype "passive"))
      (node (ref "K8") (pin "1") (pinfunction "1_1") (pintype "passive"))
      (node (ref "L1") (pin "2") (pinfunction "+_2") (pintype "passive"))
      (node (ref "L2") (pin "2") (pinfunction "+_2") (pintype "passive"))
      (node (ref "L3") (pin "2") (pinfunction "+_2") (pintype "passive"))
      (node (ref "L4") (pin "2") (pinfunction "+_2") (pintype "passive"))
      (node (ref "L5") (pin "2") (pinfunction "+_2") (pintype "passive"))
      (node (ref "L6") (pin "2") (pinfunction "+_2") (pintype "passive"))
      (node (ref "R16") (pin "2") (pinfunction "2_2") (pintype "passive"))
      (node (ref "R34") (pin "2") (pinfunction "2_2") (pintype "passive"))
      (node (ref "R4") (pin "2") (pinfunction "2_2") (pintype "passive"))
      (node (ref "R46") (pin "2") (pinfunction "2_2") (pintype "passive"))
      (node (ref "TP07") (pin "P$1") (pinfunction "TP_P$1") (pintype "input"))
      (node (ref "TP11") (pin "P$1") (pinfunction "TP_P$1") (pintype "input"))
      (node (ref "TP12") (pin "P$1") (pinfunction "TP_P$1") (pintype "input"))
      (node (ref "U1") (pin "10") (pinfunction "VCC_3_10") (pintype "power_in"))
      (node (ref "U1") (pin "100") (pinfunction "AVCC_100") (pintype "power_in"))
      (node (ref "U1") (pin "31") (pinfunction "VCC_2_31") (pintype "power_in"))
      (node (ref "U1") (pin "61") (pinfunction "VCC_4_61") (pintype "power_in"))
      (node (ref "U1") (pin "80") (pinfunction "VCC_80") (pintype "power_in"))
      (node (ref "U10") (pin "18") (pinfunction "AVCC_18") (pintype "power_in"))
      (node (ref "U10") (pin "4") (pinfunction "VCC_2_4") (pintype "power_in"))
      (node (ref "U10") (pin "6") (pinfunction "VCC_6") (pintype "power_in"))
      (node (ref "U10_PROG") (pin "2") (pinfunction "P$2_2") (pintype "bidirectional"))
      (node (ref "U11") (pin "18") (pinfunction "AVCC_18") (pintype "power_in"))
      (node (ref "U11") (pin "4") (pinfunction "VCC_2_4") (pintype "power_in"))
      (node (ref "U11") (pin "6") (pinfunction "VCC_6") (pintype "power_in"))
      (node (ref "U11_PROG") (pin "2") (pinfunction "P$2_2") (pintype "bidirectional"))
      (node (ref "U12") (pin "9") (pinfunction "COM_9") (pintype "bidirectional"))
      (node (ref "U1_PROG") (pin "2") (pinfunction "P$2_2") (pintype "bidirectional"))
      (node (ref "U5") (pin "32") (pinfunction "AVCC_32") (pintype "power_in"))
      (node (ref "U5") (pin "4") (pinfunction "VCC_4") (pintype "power_in"))
      (node (ref "U5_PROG") (pin "2") (pinfunction "P$2_2") (pintype "bidirectional"))
    )
    (net (code "2") (name "+5V(ANALOG)") (class "Default")
      (node (ref "C52") (pin "2") (pinfunction "2_2") (pintype "passive"))
      (node (ref "C65") (pin "2") (pinfunction "2_2") (pintype "passive"))
      (node (ref "C66") (pin "2") (pinfunction "2_2") (pintype "passive"))
      (node (ref "DAC1") (pin "1") (pinfunction "VDD_1") (pintype "input"))
      (node (ref "DAC2") (pin "1") (pinfunction "VDD_1") (pintype "input"))
      (node (ref "R30") (pin "2") (pinfunction "2_2") (pintype "passive"))
      (node (ref "UR1") (pin "3") (pinfunction "VO_3") (pintype "passive"))
    )
    (net (code "3") (name "+9V") (class "Default")
      (node (ref "CONN2") (pin "2") (pinfunction "KL_2") (pintype "passive"))
    )
    (net (code "4") (name "AGND") (class "Default")
      (node (ref "C1") (pin "2") (pinfunction "2_2") (pintype "passive"))
      (node (ref "C10") (pin "2") (pinfunction "2_2") (pintype "passive"))
      (node (ref "C11") (pin "2") (pinfunction "2_2") (pintype "passive"))
      (node (ref "C12") (pin "2") (pinfunction "2_2") (pintype "passive"))
      (node (ref "C13") (pin "2") (pinfunction "2_2") (pintype "passive"))
      (node (ref "C14") (pin "2") (pinfunction "2_2") (pintype "passive"))
      (node (ref "C15") (pin "2") (pinfunction "2_2") (pintype "passive"))
      (node (ref "C16") (pin "2") (pinfunction "2_2") (pintype "passive"))
      (node (ref "C17") (pin "2") (pinfunction "2_2") (pintype "passive"))
      (node (ref "C18") (pin "2") (pinfunction "2_2") (pintype "passive"))
      (node (ref "C2") (pin "2") (pinfunction "2_2") (pintype "passive"))
      (node (ref "C21") (pin "2") (pinfunction "2_2") (pintype "passive"))
      (node (ref "C22") (pin "2") (pinfunction "2_2") (pintype "passive"))
      (node (ref "C25") (pin "2") (pinfunction "2_2") (pintype "passive"))
      (node (ref "C26") (pin "2") (pinfunction "2_2") (pintype "passive"))
      (node (ref "C27") (pin "2") (pinfunction "2_2") (pintype "passive"))
      (node (ref "C28") (pin "2") (pinfunction "2_2") (pintype "passive"))
      (node (ref "C29") (pin "2") (pinfunction "2_2") (pintype "passive"))
      (node (ref "C3") (pin "2") (pinfunction "2_2") (pintype "passive"))
      (node (ref "C30") (pin "2") (pinfunction "2_2") (pintype "passive"))
      (node (ref "C4") (pin "2") (pinfunction "2_2") (pintype "passive"))
      (node (ref "C5") (pin "2") (pinfunction "2_2") (pintype "passive"))
      (node (ref "C51") (pin "1") (pinfunction "1_1") (pintype "passive"))
      (node (ref "C52") (pin "1") (pinfunction "1_1") (pintype "passive"))
      (node (ref "C53") (pin "2") (pinfunction "2_2") (pintype "passive"))
      (node (ref "C54") (pin "2") (pinfunction "2_2") (pintype "passive"))
      (node (ref "C57") (pin "2") (pinfunction "2_2") (pintype "passive"))
      (node (ref "C58") (pin "2") (pinfunction "2_2") (pintype "passive"))
      (node (ref "C6") (pin "2") (pinfunction "2_2") (pintype "passive"))
      (node (ref "C60") (pin "2") (pinfunction "2_2") (pintype "passive"))
      (node (ref "C61") (pin "2") (pinfunction "2_2") (pintype "passive"))
      (node (ref "C62") (pin "2") (pinfunction "2_2") (pintype "passive"))
      (node (ref "C63") (pin "2") (pinfunction "2_2") (pintype "passive"))
      (node (ref "C65") (pin "1") (pinfunction "1_1") (pintype "passive"))
      (node (ref "C66") (pin "1") (pinfunction "1_1") (pintype "passive"))
      (node (ref "C69") (pin "-") (pinfunction "-_-") (pintype "passive"))
      (node (ref "C7") (pin "2") (pinfunction "2_2") (pintype "passive"))
      (node (ref "C70") (pin "-") (pinfunction "-_-") (pintype "passive"))
      (node (ref "C8") (pin "2") (pinfunction "2_2") (pintype "passive"))
      (node (ref "C9") (pin "2") (pinfunction "2_2") (pintype "passive"))
      (node (ref "CONN3") (pin "2") (pinfunction "KL_2") (pintype "passive"))
      (node (ref "DAC1") (pin "12") (pinfunction "VSS_12") (pintype "input"))
      (node (ref "DAC2") (pin "12") (pinfunction "VSS_12") (pintype "input"))
      (node (ref "IC2") (pin "3") (pinfunction "+IN_3") (pintype "input"))
      (node (ref "IC2") (pin "5") (pinfunction "+IN_5") (pintype "input"))
      (node (ref "IC3") (pin "3") (pinfunction "+IN_3") (pintype "input"))
      (node (ref "IC3") (pin "5") (pinfunction "+IN_5") (pintype "input"))
      (node (ref "IC6") (pin "3") (pinfunction "+IN_3") (pintype "input"))
      (node (ref "IC6") (pin "5") (pinfunction "+IN_5") (pintype "input"))
      (node (ref "IC8") (pin "3") (pinfunction "+IN_3") (pintype "input"))
      (node (ref "IC8") (pin "5") (pinfunction "+IN_5") (pintype "input"))
      (node (ref "IC9") (pin "3") (pinfunction "+IN_3") (pintype "input"))
      (node (ref "IC9") (pin "5") (pinfunction "+IN_5") (pintype "input"))
      (node (ref "IN1(R/S)") (pin "1") (pinfunction "1_1") (pintype "bidirectional"))
      (node (ref "IN2(L/M)") (pin "1") (pinfunction "1_1") (pintype "bidirectional"))
      (node (ref "IN_LEFT") (pin "1") (pinfunction "REF_1") (pintype "passive"))
      (node (ref "IN_RIGHT") (pin "1") (pinfunction "REF_1") (pintype "passive"))
      (node (ref "OUT1(R/S)") (pin "1") (pinfunction "1_1") (pintype "bidirectional"))
      (node (ref "OUT2(L/M)") (pin "1") (pinfunction "1_1") (pintype "bidirectional"))
      (node (ref "OUT_LEFT") (pin "3") (pinfunction "GND_3") (pintype "input"))
      (node (ref "OUT_RIGHT") (pin "3") (pinfunction "GND_3") (pintype "input"))
      (node (ref "R13") (pin "2") (pinfunction "2_2") (pintype "passive"))
      (node (ref "R31") (pin "1") (pinfunction "1_1") (pintype "passive"))
      (node (ref "R62") (pin "2") (pinfunction "2_2") (pintype "passive"))
      (node (ref "R67") (pin "2") (pinfunction "2_2") (pintype "passive"))
      (node (ref "TP08") (pin "P$1") (pinfunction "TP_P$1") (pintype "input"))
      (node (ref "TP14") (pin "P$1") (pinfunction "TP_P$1") (pintype "input"))
      (node (ref "TP15") (pin "P$1") (pinfunction "TP_P$1") (pintype "input"))
      (node (ref "TP16") (pin "P$1") (pinfunction "TP_P$1") (pintype "input"))
      (node (ref "TP18") (pin "P$1") (pinfunction "TP_P$1") (pintype "input"))
      (node (ref "TP19") (pin "P$1") (pinfunction "TP_P$1") (pintype "input"))
      (node (ref "TP20") (pin "P$1") (pinfunction "TP_P$1") (pintype "input"))
      (node (ref "TP21") (pin "P$1") (pinfunction "TP_P$1") (pintype "input"))
      (node (ref "TP22") (pin "P$1") (pinfunction "TP_P$1") (pintype "input"))
      (node (ref "U4") (pin "2") (pinfunction "IN-_2") (pintype "input"))
      (node (ref "U6") (pin "1") (pinfunction "REF_1") (pintype "passive"))
      (node (ref "U7") (pin "2") (pinfunction "IN-_2") (pintype "input"))
      (node (ref "U8") (pin "1") (pinfunction "REF_1") (pintype "passive"))
      (node (ref "UR1") (pin "2") (pinfunction "GND_2") (pintype "passive"))
      (node (ref "VCA1(LEFT)") (pin "3") (pinfunction "EC-_3") (pintype "output"))
      (node (ref "VCA1(LEFT)") (pin "6") (pinfunction "GND_6") (pintype "passive"))
      (node (ref "VCA2(RIGHT)") (pin "3") (pinfunction "EC-_3") (pintype "output"))
      (node (ref "VCA2(RIGHT)") (pin "6") (pinfunction "GND_6") (pintype "passive"))
    )
    (net (code "5") (name "C_D(+)") (class "Default")
      (node (ref "R2") (pin "1") (pinfunction "1_1") (pintype "passive"))
      (node (ref "USB1") (pin "3") (pinfunction "3_3") (pintype "bidirectional"))
      (node (ref "V2") (pin "1") (pinfunction "1_1") (pintype "passive"))
    )
    (net (code "6") (name "C_D(-)") (class "Default")
      (node (ref "R1") (pin "1") (pinfunction "1_1") (pintype "passive"))
      (node (ref "USB1") (pin "2") (pinfunction "2_2") (pintype "bidirectional"))
      (node (ref "V1") (pin "1") (pinfunction "1_1") (pintype "passive"))
    )
    (net (code "7") (name "C_UVCC") (class "Default")
      (node (ref "F1") (pin "1") (pinfunction "1_1") (pintype "bidirectional"))
      (node (ref "USB1") (pin "1") (pinfunction "1_1") (pintype "bidirectional"))
    )
    (net (code "8") (name "D(+)") (class "Default")
      (node (ref "R2") (pin "2") (pinfunction "2_2") (pintype "passive"))
      (node (ref "U5") (pin "29") (pinfunction "D+_29") (pintype "passive"))
    )
    (net (code "9") (name "D(-)") (class "Default")
      (node (ref "R1") (pin "2") (pinfunction "2_2") (pintype "passive"))
      (node (ref "U5") (pin "30") (pinfunction "D-_30") (pintype "passive"))
    )
    (net (code "10") (name "DAC1_OUT(A)") (class "Default")
      (node (ref "DAC1") (pin "14") (pinfunction "V_OUT_A_14") (pintype "input"))
      (node (ref "R60") (pin "1") (pinfunction "1_1") (pintype "passive"))
    )
    (net (code "11") (name "DAC1_OUT(B)") (class "Default")
      (node (ref "DAC1") (pin "10") (pinfunction "V_OUT_B_10") (pintype "input"))
      (node (ref "R64") (pin "1") (pinfunction "1_1") (pintype "passive"))
    )
    (net (code "12") (name "DAC2_OUT(A)") (class "Default")
      (node (ref "DAC2") (pin "14") (pinfunction "V_OUT_A_14") (pintype "input"))
      (node (ref "R57") (pin "1") (pinfunction "1_1") (pintype "passive"))
    )
    (net (code "13") (name "DAC2_OUT(B)") (class "Default")
      (node (ref "DAC2") (pin "10") (pinfunction "V_OUT_B_10") (pintype "input"))
      (node (ref "R66") (pin "1") (pinfunction "1_1") (pintype "passive"))
    )
    (net (code "14") (name "DAC_REF_VOLTAGE") (class "Default")
      (node (ref "DAC1") (pin "11") (pinfunction "V_REF_B_11") (pintype "input"))
      (node (ref "DAC1") (pin "13") (pinfunction "V_REF_A_13") (pintype "input"))
      (node (ref "DAC2") (pin "11") (pinfunction "V_REF_B_11") (pintype "input"))
      (node (ref "DAC2") (pin "13") (pinfunction "V_REF_A_13") (pintype "input"))
      (node (ref "R30") (pin "1") (pinfunction "1_1") (pintype "passive"))
      (node (ref "R31") (pin "2") (pinfunction "2_2") (pintype "passive"))
      (node (ref "TP35") (pin "P$1") (pinfunction "TP_P$1") (pintype "input"))
    )
    (net (code "15") (name "DGND") (class "Default")
      (node (ref "C19") (pin "2") (pinfunction "2_2") (pintype "passive"))
      (node (ref "C20") (pin "2") (pinfunction "2_2") (pintype "passive"))
      (node (ref "C23") (pin "1") (pinfunction "1_1") (pintype "passive"))
      (node (ref "C24") (pin "1") (pinfunction "1_1") (pintype "passive"))
      (node (ref "C32") (pin "2") (pinfunction "2_2") (pintype "passive"))
      (node (ref "C33") (pin "1") (pinfunction "1_1") (pintype "passive"))
      (node (ref "C34") (pin "1") (pinfunction "1_1") (pintype "passive"))
      (node (ref "C35") (pin "1") (pinfunction "1_1") (pintype "passive"))
      (node (ref "C36") (pin "-") (pinfunction "-_-") (pintype "passive"))
      (node (ref "C37") (pin "1") (pinfunction "1_1") (pintype "passive"))
      (node (ref "C38") (pin "1") (pinfunction "1_1") (pintype "passive"))
      (node (ref "C39") (pin "1") (pinfunction "1_1") (pintype "passive"))
      (node (ref "C40") (pin "1") (pinfunction "1_1") (pintype "passive"))
      (node (ref "C41") (pin "-") (pinfunction "-_-") (pintype "passive"))
      (node (ref "C42") (pin "1") (pinfunction "1_1") (pintype "passive"))
      (node (ref "C44") (pin "1") (pinfunction "1_1") (pintype "passive"))
      (node (ref "C45") (pin "1") (pinfunction "1_1") (pintype "passive"))
      (node (ref "C46") (pin "2") (pinfunction "2_2") (pintype "passive"))
      (node (ref "C47") (pin "2") (pinfunction "2_2") (pintype "passive"))
      (node (ref "C48") (pin "2") (pinfunction "2_2") (pintype "passive"))
      (node (ref "C49") (pin "2") (pinfunction "2_2") (pintype "passive"))
      (node (ref "C50") (pin "2") (pinfunction "2_2") (pintype "passive"))
      (node (ref "CONN1") (pin "10") (pinfunction "P$10_10") (pintype "bidirectional"))
      (node (ref "CONN1") (pin "5") (pinfunction "P$5_5") (pintype "bidirectional"))
      (node (ref "CONN1") (pin "6") (pinfunction "P$6_6") (pintype "bidirectional"))
      (node (ref "CONN1") (pin "7") (pinfunction "P$7_7") (pintype "bidirectional"))
      (node (ref "CONN1") (pin "8") (pinfunction "P$8_8") (pintype "bidirectional"))
      (node (ref "CONN2") (pin "3") (pinfunction "KL_3") (pintype "passive"))
      (node (ref "DAC1") (pin "8") (pinfunction "LDAC_8") (pintype "input"))
      (node (ref "DAC2") (pin "8") (pinfunction "LDAC_8") (pintype "input"))
      (node (ref "DGND1") (pin "P$1") (pinfunction "TP_P$1") (pintype "input"))
      (node (ref "DGND2") (pin "P$1") (pinfunction "TP_P$1") (pintype "input"))
      (node (ref "DGND3") (pin "P$1") (pinfunction "TP_P$1") (pintype "input"))
      (node (ref "DGND4") (pin "P$1") (pinfunction "TP_P$1") (pintype "input"))
      (node (ref "R13") (pin "1") (pinfunction "1_1") (pintype "passive"))
      (node (ref "R45") (pin "1") (pinfunction "1_1") (pintype "passive"))
      (node (ref "U1") (pin "11") (pinfunction "GND_2_11") (pintype "passive"))
      (node (ref "U1") (pin "32") (pinfunction "GND_4_32") (pintype "passive"))
      (node (ref "U1") (pin "62") (pinfunction "GND_3_62") (pintype "passive"))
      (node (ref "U1") (pin "81") (pinfunction "GND_5_81") (pintype "passive"))
      (node (ref "U1") (pin "99") (pinfunction "GND_99") (pintype "passive"))
      (node (ref "U10") (pin "21") (pinfunction "GND_21") (pintype "passive"))
      (node (ref "U10") (pin "3") (pinfunction "GND_2_3") (pintype "passive"))
      (node (ref "U10") (pin "5") (pinfunction "GND_3_5") (pintype "passive"))
      (node (ref "U10_PROG") (pin "6") (pinfunction "P$6_6") (pintype "bidirectional"))
      (node (ref "U11") (pin "21") (pinfunction "GND_21") (pintype "passive"))
      (node (ref "U11") (pin "3") (pinfunction "GND_2_3") (pintype "passive"))
      (node (ref "U11") (pin "5") (pinfunction "GND_3_5") (pintype "passive"))
      (node (ref "U11_PROG") (pin "6") (pinfunction "P$6_6") (pintype "bidirectional"))
      (node (ref "U12") (pin "8") (pinfunction "GND_8") (pintype "bidirectional"))
      (node (ref "U1_PROG") (pin "6") (pinfunction "P$6_6") (pintype "bidirectional"))
      (node (ref "U5") (pin "3") (pinfunction "GND_3") (pintype "passive"))
      (node (ref "U5_PROG") (pin "6") (pinfunction "P$6_6") (pintype "bidirectional"))
    )
    (net (code "16") (name "L") (class "Default")
      (node (ref "IC4") (pin "3") (pinfunction "+IN_3") (pintype "input"))
      (node (ref "IN_LEFT") (pin "5") (pinfunction "SEN_5") (pintype "output"))
      (node (ref "IN_LEFT") (pin "6") (pinfunction "OUT_6") (pintype "output"))
      (node (ref "K5") (pin "Q1") (pinfunction "O_Q1") (pintype "passive"))
      (node (ref "R17") (pin "1") (pinfunction "1_1") (pintype "passive"))
    )
    (net (code "17") (name "L_SIGNAL") (class "Default")
      (node (ref "L") (pin "2") (pinfunction "2_2") (pintype "passive"))
      (node (ref "TP01") (pin "P$1") (pinfunction "TP_P$1") (pintype "input"))
      (node (ref "U1") (pin "97") (pinfunction "PF0_(ADC0)_97") (pintype "bidirectional"))
      (node (ref "U10") (pin "23") (pinfunction "PC0_23") (pintype "bidirectional"))
      (node (ref "U11") (pin "23") (pinfunction "PC0_23") (pintype "bidirectional"))
    )
    (net (code "18") (name "L{slash}M_IN(VCA1_IN)") (class "Default")
      (node (ref "C67") (pin "+") (pinfunction "+_+") (pintype "passive"))
      (node (ref "K5") (pin "P1") (pinfunction "P_P1") (pintype "passive"))
    )
    (net (code "19") (name "L{slash}M_OUT(VCA1_OUT)") (class "Default")
      (node (ref "C55") (pin "2") (pinfunction "2_2") (pintype "passive"))
      (node (ref "IC1") (pin "3") (pinfunction "+IN_3") (pintype "input"))
      (node (ref "IC8") (pin "1") (pinfunction "OUT_1") (pintype "output"))
      (node (ref "K6") (pin "Q1") (pinfunction "O_Q1") (pintype "passive"))
      (node (ref "R25") (pin "1") (pinfunction "1_1") (pintype "passive"))
      (node (ref "R48") (pin "2") (pinfunction "2_2") (pintype "passive"))
    )
    (net (code "20") (name "L{slash}M_OUT_SIGNAL") (class "Default")
      (node (ref "L/M_OUT") (pin "2") (pinfunction "2_2") (pintype "passive"))
      (node (ref "TP03") (pin "P$1") (pinfunction "TP_P$1") (pintype "input"))
      (node (ref "U1") (pin "93") (pinfunction "PF4_(ADC4/TCK)_93") (pintype "bidirectional"))
      (node (ref "U10") (pin "27") (pinfunction "PC4_27") (pintype "bidirectional"))
      (node (ref "U11") (pin "27") (pinfunction "PC4_27") (pintype "bidirectional"))
    )
    (net (code "21") (name "M") (class "Default")
      (node (ref "K5") (pin "S1") (pinfunction "S_S1") (pintype "passive"))
      (node (ref "R21") (pin "1") (pinfunction "1_1") (pintype "passive"))
      (node (ref "U4") (pin "5") (pinfunction "SEN_5") (pintype "output"))
      (node (ref "U4") (pin "6") (pinfunction "OUT_6") (pintype "output"))
    )
    (net (code "22") (name "MAIN_µC_AREF") (class "Default")
      (node (ref "C50") (pin "1") (pinfunction "1_1") (pintype "passive"))
      (node (ref "U1") (pin "98") (pinfunction "AREF_98") (pintype "input"))
    )
    (net (code "23") (name "MAIN_µC_D2") (class "Default")
      (node (ref "U1") (pin "6") (pinfunction "(OC3B/INT4)_PE4_6") (pintype "bidirectional"))
      (node (ref "U12") (pin "1") (pinfunction "IN1_1") (pintype "bidirectional"))
    )
    (net (code "24") (name "MAIN_µC_D3") (class "Default")
      (node (ref "U1") (pin "7") (pinfunction "(OC3C/INT5)_PE5_7") (pintype "bidirectional"))
      (node (ref "U12") (pin "2") (pinfunction "IN2_2") (pintype "bidirectional"))
    )
    (net (code "25") (name "MAIN_µC_D4") (class "Default")
      (node (ref "U1") (pin "1") (pinfunction "(OC0B)_PG5_1") (pintype "bidirectional"))
      (node (ref "U12") (pin "3") (pinfunction "IN3_3") (pintype "bidirectional"))
    )
    (net (code "26") (name "MAIN_µC_D5") (class "Default")
      (node (ref "U1") (pin "5") (pinfunction "(OC3A/AIN1)_PE3_5") (pintype "bidirectional"))
      (node (ref "U12") (pin "4") (pinfunction "IN4_4") (pintype "bidirectional"))
    )
    (net (code "27") (name "MAIN_µC_D6") (class "Default")
      (node (ref "U1") (pin "15") (pinfunction "(OC4A)_PH3_15") (pintype "bidirectional"))
      (node (ref "U12") (pin "5") (pinfunction "IN5_5") (pintype "bidirectional"))
    )
    (net (code "28") (name "MAIN_µC_D7") (class "Default")
      (node (ref "U1") (pin "16") (pinfunction "(OC4B)_PH4_16") (pintype "bidirectional"))
      (node (ref "U12") (pin "6") (pinfunction "IN6_6") (pintype "bidirectional"))
    )
    (net (code "29") (name "MAIN_µC_PB1(SCK)") (class "Default")
      (node (ref "U1") (pin "20") (pinfunction "(SCK/PCINT1)_PB1_20") (pintype "bidirectional"))
      (node (ref "U1_PROG") (pin "3") (pinfunction "P$3_3") (pintype "bidirectional"))
    )
    (net (code "30") (name "MAIN_µC_PB2(MOSI)") (class "Default")
      (node (ref "U1") (pin "21") (pinfunction "(MOSI/PCINT2)_PB2_21") (pintype "bidirectional"))
      (node (ref "U1_PROG") (pin "4") (pinfunction "P$4_4") (pintype "bidirectional"))
    )
    (net (code "31") (name "MAIN_µC_PB3(MISO)") (class "Default")
      (node (ref "U1") (pin "22") (pinfunction "(MISO/PCINT3)_PB3_22") (pintype "bidirectional"))
      (node (ref "U1_PROG") (pin "1") (pinfunction "P$1_1") (pintype "bidirectional"))
    )
    (net (code "32") (name "MAIN_µC_RESET") (class "Default")
      (node (ref "C43") (pin "1") (pinfunction "1_1") (pintype "passive"))
      (node (ref "C46") (pin "1") (pinfunction "1_1") (pintype "passive"))
      (node (ref "D2") (pin "A") (pinfunction "A_A") (pintype "passive"))
      (node (ref "R46") (pin "1") (pinfunction "1_1") (pintype "passive"))
      (node (ref "U1") (pin "30") (pinfunction "~{RESET}_30") (pintype "input"))
      (node (ref "U1_PROG") (pin "5") (pinfunction "P$5_5") (pintype "bidirectional"))
    )
    (net (code "33") (name "MAIN_µC_RX0") (class "Default")
      (node (ref "R5") (pin "2") (pinfunction "2_2") (pintype "passive"))
      (node (ref "TP31") (pin "P$1") (pinfunction "TP_P$1") (pintype "input"))
      (node (ref "U1") (pin "2") (pinfunction "(RXD0/PCINT8)_PE0_2") (pintype "bidirectional"))
    )
    (net (code "34") (name "MAIN_µC_RX1") (class "Default")
      (node (ref "R68") (pin "2") (pinfunction "2_2") (pintype "passive"))
      (node (ref "U1") (pin "45") (pinfunction "(RXD1/INT2)_PD2_45") (pintype "bidirectional"))
    )
    (net (code "35") (name "MAIN_µC_RX2") (class "Default")
      (node (ref "R41") (pin "2") (pinfunction "2_2") (pintype "passive"))
      (node (ref "TP27") (pin "P$1") (pinfunction "TP_P$1") (pintype "input"))
      (node (ref "U1") (pin "12") (pinfunction "(RXD2)_PH0_12") (pintype "bidirectional"))
    )
    (net (code "36") (name "MAIN_µC_RX3") (class "Default")
      (node (ref "R43") (pin "2") (pinfunction "2_2") (pintype "passive"))
      (node (ref "TP33") (pin "P$1") (pinfunction "TP_P$1") (pintype "input"))
      (node (ref "U1") (pin "63") (pinfunction "PJ0_(RXD3/PCINT9)_63") (pintype "bidirectional"))
    )
    (net (code "37") (name "MAIN_µC_TX0") (class "Default")
      (node (ref "R6") (pin "2") (pinfunction "2_2") (pintype "passive"))
      (node (ref "TP32") (pin "P$1") (pinfunction "TP_P$1") (pintype "input"))
      (node (ref "U1") (pin "3") (pinfunction "(TXD0)_PE1_3") (pintype "bidirectional"))
    )
    (net (code "38") (name "MAIN_µC_TX1") (class "Default")
      (node (ref "R32") (pin "2") (pinfunction "2_2") (pintype "passive"))
      (node (ref "U1") (pin "46") (pinfunction "(TXD1/INT3)_PD3_46") (pintype "bidirectional"))
    )
    (net (code "39") (name "MAIN_µC_TX2") (class "Default")
      (node (ref "R42") (pin "2") (pinfunction "2_2") (pintype "passive"))
      (node (ref "TP28") (pin "P$1") (pinfunction "TP_P$1") (pintype "input"))
      (node (ref "U1") (pin "13") (pinfunction "(TXD2)_PH1_13") (pintype "bidirectional"))
    )
    (net (code "40") (name "MAIN_µC_TX3") (class "Default")
      (node (ref "R44") (pin "2") (pinfunction "2_2") (pintype "passive"))
      (node (ref "TP34") (pin "P$1") (pinfunction "TP_P$1") (pintype "input"))
      (node (ref "U1") (pin "64") (pinfunction "PJ1_(TXD3/PCINT10)_64") (pintype "bidirectional"))
    )
    (net (code "41") (name "MAIN_µC_XTAL1") (class "Default")
      (node (ref "C44") (pin "2") (pinfunction "2_2") (pintype "passive"))
      (node (ref "QA4") (pin "2") (pinfunction "2_2") (pintype "passive"))
      (node (ref "R47") (pin "2") (pinfunction "2_2") (pintype "passive"))
      (node (ref "U1") (pin "34") (pinfunction "XTAL1_34") (pintype "input"))
    )
    (net (code "42") (name "MAIN_µC_XTAL2") (class "Default")
      (node (ref "C45") (pin "2") (pinfunction "2_2") (pintype "passive"))
      (node (ref "QA4") (pin "1") (pinfunction "1_1") (pintype "passive"))
      (node (ref "R47") (pin "1") (pinfunction "1_1") (pintype "passive"))
      (node (ref "U1") (pin "33") (pinfunction "XTAL2_33") (pintype "output"))
    )
    (net (code "43") (name "M_SIGNAL") (class "Default")
      (node (ref "M") (pin "2") (pinfunction "2_2") (pintype "passive"))
      (node (ref "TP05") (pin "P$1") (pinfunction "TP_P$1") (pintype "input"))
      (node (ref "U1") (pin "95") (pinfunction "PF2_(ADC2)_95") (pintype "bidirectional"))
      (node (ref "U10") (pin "25") (pinfunction "PC2_25") (pintype "bidirectional"))
      (node (ref "U11") (pin "25") (pinfunction "PC2_25") (pintype "bidirectional"))
    )
    (net (code "44") (name "Net-(BY_1_1B-O)") (class "Default")
      (node (ref "BY_1_1") (pin "Q1") (pinfunction "O_Q1") (pintype "passive"))
      (node (ref "BY_1_2") (pin "Q1") (pinfunction "O_Q1") (pintype "passive"))
    )
    (net (code "45") (name "Net-(BY_1_1B-P)") (class "Default")
      (node (ref "BY_1_1") (pin "P1") (pinfunction "P_P1") (pintype "passive"))
      (node (ref "IN1(R/S)") (pin "3") (pinfunction "3_3") (pintype "bidirectional"))
    )
    (net (code "46") (name "Net-(BY_1_1B-S)") (class "Default")
      (node (ref "BY_1_1") (pin "S1") (pinfunction "S_S1") (pintype "passive"))
      (node (ref "IN_RIGHT") (pin "2") (pinfunction "IN-_2") (pintype "input"))
    )
    (net (code "47") (name "Net-(BY_1_1C-O)") (class "Default")
      (node (ref "BY_1_1") (pin "Q2") (pinfunction "O_Q2") (pintype "passive"))
      (node (ref "BY_1_2") (pin "Q2") (pinfunction "O_Q2") (pintype "passive"))
    )
    (net (code "48") (name "Net-(BY_1_1C-P)") (class "Default")
      (node (ref "BY_1_1") (pin "P2") (pinfunction "P_P2") (pintype "passive"))
      (node (ref "IN1(R/S)") (pin "2") (pinfunction "2_2") (pintype "bidirectional"))
    )
    (net (code "49") (name "Net-(BY_1_1C-S)") (class "Default")
      (node (ref "BY_1_1") (pin "S2") (pinfunction "S_S2") (pintype "passive"))
      (node (ref "IN_RIGHT") (pin "3") (pinfunction "IN+_3") (pintype "input"))
    )
    (net (code "50") (name "Net-(BY_1_2B-P)") (class "Default")
      (node (ref "BY_1_2") (pin "P1") (pinfunction "P_P1") (pintype "passive"))
      (node (ref "OUT1(R/S)") (pin "3") (pinfunction "3_3") (pintype "bidirectional"))
    )
    (net (code "51") (name "Net-(BY_1_2B-S)") (class "Default")
      (node (ref "BY_1_2") (pin "S1") (pinfunction "S_S1") (pintype "passive"))
      (node (ref "OUT_RIGHT") (pin "7") (pinfunction "SEN+_7") (pintype "output"))
      (node (ref "OUT_RIGHT") (pin "8") (pinfunction "OUT+_8") (pintype "output"))
    )
    (net (code "52") (name "Net-(BY_1_2C-P)") (class "Default")
      (node (ref "BY_1_2") (pin "P2") (pinfunction "P_P2") (pintype "passive"))
      (node (ref "OUT1(R/S)") (pin "2") (pinfunction "2_2") (pintype "bidirectional"))
    )
    (net (code "53") (name "Net-(BY_1_2C-S)") (class "Default")
      (node (ref "BY_1_2") (pin "S2") (pinfunction "S_S2") (pintype "passive"))
      (node (ref "OUT_RIGHT") (pin "1") (pinfunction "OUT-_1") (pintype "output"))
      (node (ref "OUT_RIGHT") (pin "2") (pinfunction "SEN-_2") (pintype "passive"))
    )
    (net (code "54") (name "Net-(BY_2_1B-O)") (class "Default")
      (node (ref "BY_2_1") (pin "Q1") (pinfunction "O_Q1") (pintype "passive"))
      (node (ref "BY_2_2") (pin "Q1") (pinfunction "O_Q1") (pintype "passive"))
    )
    (net (code "55") (name "Net-(BY_2_1B-P)") (class "Default")
      (node (ref "BY_2_1") (pin "P1") (pinfunction "P_P1") (pintype "passive"))
      (node (ref "OUT2(L/M)") (pin "3") (pinfunction "3_3") (pintype "bidirectional"))
    )
    (net (code "56") (name "Net-(BY_2_1B-S)") (class "Default")
      (node (ref "BY_2_1") (pin "S1") (pinfunction "S_S1") (pintype "passive"))
      (node (ref "OUT_LEFT") (pin "7") (pinfunction "SEN+_7") (pintype "output"))
      (node (ref "OUT_LEFT") (pin "8") (pinfunction "OUT+_8") (pintype "output"))
    )
    (net (code "57") (name "Net-(BY_2_1C-O)") (class "Default")
      (node (ref "BY_2_1") (pin "Q2") (pinfunction "O_Q2") (pintype "passive"))
      (node (ref "BY_2_2") (pin "Q2") (pinfunction "O_Q2") (pintype "passive"))
    )
    (net (code "58") (name "Net-(BY_2_1C-P)") (class "Default")
      (node (ref "BY_2_1") (pin "P2") (pinfunction "P_P2") (pintype "passive"))
      (node (ref "OUT2(L/M)") (pin "2") (pinfunction "2_2") (pintype "bidirectional"))
    )
    (net (code "59") (name "Net-(BY_2_1C-S)") (class "Default")
      (node (ref "BY_2_1") (pin "S2") (pinfunction "S_S2") (pintype "passive"))
      (node (ref "OUT_LEFT") (pin "1") (pinfunction "OUT-_1") (pintype "output"))
      (node (ref "OUT_LEFT") (pin "2") (pinfunction "SEN-_2") (pintype "passive"))
    )
    (net (code "60") (name "Net-(BY_2_2B-P)") (class "Default")
      (node (ref "BY_2_2") (pin "P1") (pinfunction "P_P1") (pintype "passive"))
      (node (ref "IN2(L/M)") (pin "3") (pinfunction "3_3") (pintype "bidirectional"))
    )
    (net (code "61") (name "Net-(BY_2_2B-S)") (class "Default")
      (node (ref "BY_2_2") (pin "S1") (pinfunction "S_S1") (pintype "passive"))
      (node (ref "IN_LEFT") (pin "2") (pinfunction "IN-_2") (pintype "input"))
    )
    (net (code "62") (name "Net-(BY_2_2C-P)") (class "Default")
      (node (ref "BY_2_2") (pin "P2") (pinfunction "P_P2") (pintype "passive"))
      (node (ref "IN2(L/M)") (pin "2") (pinfunction "2_2") (pintype "bidirectional"))
    )
    (net (code "63") (name "Net-(BY_2_2C-S)") (class "Default")
      (node (ref "BY_2_2") (pin "S2") (pinfunction "S_S2") (pintype "passive"))
      (node (ref "IN_LEFT") (pin "3") (pinfunction "IN+_3") (pintype "input"))
    )
    (net (code "64") (name "Net-(C67-Pad-)") (class "Default")
      (node (ref "C67") (pin "-") (pinfunction "-_-") (pintype "passive"))
      (node (ref "R52") (pin "1") (pinfunction "1_1") (pintype "passive"))
    )
    (net (code "65") (name "Net-(C68-Pad-)") (class "Default")
      (node (ref "C68") (pin "-") (pinfunction "-_-") (pintype "passive"))
      (node (ref "R53") (pin "1") (pinfunction "1_1") (pintype "passive"))
    )
    (net (code "66") (name "Net-(C69-Pad+)") (class "Default")
      (node (ref "C69") (pin "+") (pinfunction "+_+") (pintype "passive"))
      (node (ref "R56") (pin "1") (pinfunction "1_1") (pintype "passive"))
      (node (ref "R57") (pin "2") (pinfunction "2_2") (pintype "passive"))
    )
    (net (code "67") (name "Net-(C70-Pad+)") (class "Default")
      (node (ref "C70") (pin "+") (pinfunction "+_+") (pintype "passive"))
      (node (ref "R59") (pin "1") (pinfunction "1_1") (pintype "passive"))
      (node (ref "R60") (pin "2") (pinfunction "2_2") (pintype "passive"))
    )
    (net (code "68") (name "Net-(CONN1-P$4)") (class "Default")
      (node (ref "CONN1") (pin "4") (pinfunction "P$4_4") (pintype "bidirectional"))
      (node (ref "R68") (pin "1") (pinfunction "1_1") (pintype "passive"))
      (node (ref "TP29") (pin "P$1") (pinfunction "TP_P$1") (pintype "input"))
    )
    (net (code "69") (name "Net-(CONN1-P$9)") (class "Default")
      (node (ref "CONN1") (pin "9") (pinfunction "P$9_9") (pintype "bidirectional"))
      (node (ref "R32") (pin "1") (pinfunction "1_1") (pintype "passive"))
      (node (ref "TP30") (pin "P$1") (pinfunction "TP_P$1") (pintype "input"))
    )
    (net (code "70") (name "Net-(D5-PadC)") (class "Default")
      (node (ref "D5") (pin "C") (pinfunction "C_C") (pintype "passive"))
      (node (ref "L") (pin "1") (pinfunction "1_1") (pintype "passive"))
      (node (ref "R18") (pin "2") (pinfunction "2_2") (pintype "passive"))
    )
    (net (code "71") (name "Net-(D7-PadC)") (class "Default")
      (node (ref "D7") (pin "C") (pinfunction "C_C") (pintype "passive"))
      (node (ref "R") (pin "1") (pinfunction "1_1") (pintype "passive"))
      (node (ref "R20") (pin "2") (pinfunction "2_2") (pintype "passive"))
    )
    (net (code "72") (name "Net-(D9-PadC)") (class "Default")
      (node (ref "D9") (pin "C") (pinfunction "C_C") (pintype "passive"))
      (node (ref "M") (pin "1") (pinfunction "1_1") (pintype "passive"))
      (node (ref "R22") (pin "2") (pinfunction "2_2") (pintype "passive"))
    )
    (net (code "73") (name "Net-(D11-PadC)") (class "Default")
      (node (ref "D11") (pin "C") (pinfunction "C_C") (pintype "passive"))
      (node (ref "R24") (pin "2") (pinfunction "2_2") (pintype "passive"))
      (node (ref "S") (pin "1") (pinfunction "1_1") (pintype "passive"))
    )
    (net (code "74") (name "Net-(D12-PadC)") (class "Default")
      (node (ref "D12") (pin "C") (pinfunction "C_C") (pintype "passive"))
      (node (ref "L/M_OUT") (pin "1") (pinfunction "1_1") (pintype "passive"))
      (node (ref "R26") (pin "2") (pinfunction "2_2") (pintype "passive"))
    )
    (net (code "75") (name "Net-(D14-PadC)") (class "Default")
      (node (ref "D14") (pin "C") (pinfunction "C_C") (pintype "passive"))
      (node (ref "R/S_OUT") (pin "1") (pinfunction "1_1") (pintype "passive"))
      (node (ref "R28") (pin "2") (pinfunction "2_2") (pintype "passive"))
    )
    (net (code "76") (name "Net-(DAC1-CS)") (class "Default")
      (node (ref "DAC1") (pin "3") (pinfunction "CS_3") (pintype "input"))
      (node (ref "R35") (pin "2") (pinfunction "2_2") (pintype "passive"))
    )
    (net (code "77") (name "Net-(DAC1-SCK)") (class "Default")
      (node (ref "DAC1") (pin "4") (pinfunction "SCK_4") (pintype "input"))
      (node (ref "R36") (pin "2") (pinfunction "2_2") (pintype "passive"))
    )
    (net (code "78") (name "Net-(DAC1-SDI)") (class "Default")
      (node (ref "DAC1") (pin "5") (pinfunction "SDI_5") (pintype "input"))
      (node (ref "R37") (pin "2") (pinfunction "2_2") (pintype "passive"))
    )
    (net (code "79") (name "Net-(DAC2-CS)") (class "Default")
      (node (ref "DAC2") (pin "3") (pinfunction "CS_3") (pintype "input"))
      (node (ref "R40") (pin "2") (pinfunction "2_2") (pintype "passive"))
    )
    (net (code "80") (name "Net-(DAC2-SCK)") (class "Default")
      (node (ref "DAC2") (pin "4") (pinfunction "SCK_4") (pintype "input"))
      (node (ref "R39") (pin "2") (pinfunction "2_2") (pintype "passive"))
    )
    (net (code "81") (name "Net-(DAC2-SDI)") (class "Default")
      (node (ref "DAC2") (pin "5") (pinfunction "SDI_5") (pintype "input"))
      (node (ref "R38") (pin "2") (pinfunction "2_2") (pintype "passive"))
    )
    (net (code "82") (name "Net-(IC1A--IN)") (class "Default")
      (node (ref "IC1") (pin "1") (pinfunction "OUT_1") (pintype "output"))
      (node (ref "IC1") (pin "2") (pinfunction "-IN_2") (pintype "input"))
      (node (ref "U7") (pin "3") (pinfunction "IN+_3") (pintype "input"))
      (node (ref "U8") (pin "2") (pinfunction "IN-_2") (pintype "input"))
    )
    (net (code "83") (name "Net-(IC1B--IN)") (class "Default")
      (node (ref "IC1") (pin "6") (pinfunction "-IN_6") (pintype "input"))
      (node (ref "IC1") (pin "7") (pinfunction "OUT_7") (pintype "output"))
      (node (ref "U7") (pin "1") (pinfunction "REF_1") (pintype "passive"))
      (node (ref "U8") (pin "3") (pinfunction "IN+_3") (pintype "input"))
    )
    (net (code "84") (name "Net-(IC2A--IN)") (class "Default")
      (node (ref "D4") (pin "A") (pinfunction "A_A") (pintype "passive"))
      (node (ref "IC2") (pin "2") (pinfunction "-IN_2") (pintype "input"))
      (node (ref "R17") (pin "2") (pinfunction "2_2") (pintype "passive"))
      (node (ref "R18") (pin "1") (pinfunction "1_1") (pintype "passive"))
    )
    (net (code "85") (name "Net-(IC2A-OUT)") (class "Default")
      (node (ref "D4") (pin "C") (pinfunction "C_C") (pintype "passive"))
      (node (ref "D5") (pin "A") (pinfunction "A_A") (pintype "passive"))
      (node (ref "IC2") (pin "1") (pinfunction "OUT_1") (pintype "output"))
    )
    (net (code "86") (name "Net-(IC2B--IN)") (class "Default")
      (node (ref "D6") (pin "A") (pinfunction "A_A") (pintype "passive"))
      (node (ref "IC2") (pin "6") (pinfunction "-IN_6") (pintype "input"))
      (node (ref "R19") (pin "2") (pinfunction "2_2") (pintype "passive"))
      (node (ref "R20") (pin "1") (pinfunction "1_1") (pintype "passive"))
    )
    (net (code "87") (name "Net-(IC2B-OUT)") (class "Default")
      (node (ref "D6") (pin "C") (pinfunction "C_C") (pintype "passive"))
      (node (ref "D7") (pin "A") (pinfunction "A_A") (pintype "passive"))
      (node (ref "IC2") (pin "7") (pinfunction "OUT_7") (pintype "output"))
    )
    (net (code "88") (name "Net-(IC3A--IN)") (class "Default")
      (node (ref "D8") (pin "A") (pinfunction "A_A") (pintype "passive"))
      (node (ref "IC3") (pin "2") (pinfunction "-IN_2") (pintype "input"))
      (node (ref "R21") (pin "2") (pinfunction "2_2") (pintype "passive"))
      (node (ref "R22") (pin "1") (pinfunction "1_1") (pintype "passive"))
    )
    (net (code "89") (name "Net-(IC3A-OUT)") (class "Default")
      (node (ref "D8") (pin "C") (pinfunction "C_C") (pintype "passive"))
      (node (ref "D9") (pin "A") (pinfunction "A_A") (pintype "passive"))
      (node (ref "IC3") (pin "1") (pinfunction "OUT_1") (pintype "output"))
    )
    (net (code "90") (name "Net-(IC3B--IN)") (class "Default")
      (node (ref "D10") (pin "A") (pinfunction "A_A") (pintype "passive"))
      (node (ref "IC3") (pin "6") (pinfunction "-IN_6") (pintype "input"))
      (node (ref "R23") (pin "2") (pinfunction "2_2") (pintype "passive"))
      (node (ref "R24") (pin "1") (pinfunction "1_1") (pintype "passive"))
    )
    (net (code "91") (name "Net-(IC3B-OUT)") (class "Default")
      (node (ref "D10") (pin "C") (pinfunction "C_C") (pintype "passive"))
      (node (ref "D11") (pin "A") (pinfunction "A_A") (pintype "passive"))
      (node (ref "IC3") (pin "7") (pinfunction "OUT_7") (pintype "output"))
    )
    (net (code "92") (name "Net-(IC4A--IN)") (class "Default")
      (node (ref "IC4") (pin "1") (pinfunction "OUT_1") (pintype "output"))
      (node (ref "IC4") (pin "2") (pinfunction "-IN_2") (pintype "input"))
      (node (ref "U4") (pin "3") (pinfunction "IN+_3") (pintype "input"))
      (node (ref "U6") (pin "2") (pinfunction "IN-_2") (pintype "input"))
    )
    (net (code "93") (name "Net-(IC4B--IN)") (class "Default")
      (node (ref "IC4") (pin "6") (pinfunction "-IN_6") (pintype "input"))
      (node (ref "IC4") (pin "7") (pinfunction "OUT_7") (pintype "output"))
      (node (ref "U4") (pin "1") (pinfunction "REF_1") (pintype "passive"))
      (node (ref "U6") (pin "3") (pinfunction "IN+_3") (pintype "input"))
    )
    (net (code "94") (name "Net-(IC6A--IN)") (class "Default")
      (node (ref "D3") (pin "A") (pinfunction "A_A") (pintype "passive"))
      (node (ref "IC6") (pin "2") (pinfunction "-IN_2") (pintype "input"))
      (node (ref "R25") (pin "2") (pinfunction "2_2") (pintype "passive"))
      (node (ref "R26") (pin "1") (pinfunction "1_1") (pintype "passive"))
    )
    (net (code "95") (name "Net-(IC6A-OUT)") (class "Default")
      (node (ref "D12") (pin "A") (pinfunction "A_A") (pintype "passive"))
      (node (ref "D3") (pin "C") (pinfunction "C_C") (pintype "passive"))
      (node (ref "IC6") (pin "1") (pinfunction "OUT_1") (pintype "output"))
    )
    (net (code "96") (name "Net-(IC6B--IN)") (class "Default")
      (node (ref "D13") (pin "A") (pinfunction "A_A") (pintype "passive"))
      (node (ref "IC6") (pin "6") (pinfunction "-IN_6") (pintype "input"))
      (node (ref "R27") (pin "2") (pinfunction "2_2") (pintype "passive"))
      (node (ref "R28") (pin "1") (pinfunction "1_1") (pintype "passive"))
    )
    (net (code "97") (name "Net-(IC6B-OUT)") (class "Default")
      (node (ref "D13") (pin "C") (pinfunction "C_C") (pintype "passive"))
      (node (ref "D14") (pin "A") (pinfunction "A_A") (pintype "passive"))
      (node (ref "IC6") (pin "7") (pinfunction "OUT_7") (pintype "output"))
    )
    (net (code "98") (name "Net-(IC8A--IN)") (class "Default")
      (node (ref "C55") (pin "1") (pinfunction "1_1") (pintype "passive"))
      (node (ref "IC8") (pin "2") (pinfunction "-IN_2") (pintype "input"))
      (node (ref "R48") (pin "1") (pinfunction "1_1") (pintype "passive"))
      (node (ref "VCA1(LEFT)") (pin "8") (pinfunction "OUT_8") (pintype "output"))
    )
    (net (code "99") (name "Net-(IC8B--IN)") (class "Default")
      (node (ref "C56") (pin "1") (pinfunction "1_1") (pintype "passive"))
      (node (ref "IC8") (pin "6") (pinfunction "-IN_6") (pintype "input"))
      (node (ref "R49") (pin "1") (pinfunction "1_1") (pintype "passive"))
      (node (ref "VCA2(RIGHT)") (pin "8") (pinfunction "OUT_8") (pintype "output"))
    )
    (net (code "100") (name "Net-(IC9A--IN)") (class "Default")
      (node (ref "C64") (pin "1") (pinfunction "1_1") (pintype "passive"))
      (node (ref "IC9") (pin "2") (pinfunction "-IN_2") (pintype "input"))
      (node (ref "R58") (pin "1") (pinfunction "1_1") (pintype "passive"))
      (node (ref "R59") (pin "2") (pinfunction "2_2") (pintype "passive"))
      (node (ref "R61") (pin "2") (pinfunction "2_2") (pintype "passive"))
    )
    (net (code "101") (name "Net-(IC9A-OUT)") (class "Default")
      (node (ref "C64") (pin "2") (pinfunction "2_2") (pintype "passive"))
      (node (ref "IC9") (pin "1") (pinfunction "OUT_1") (pintype "output"))
      (node (ref "R29") (pin "1") (pinfunction "1_1") (pintype "passive"))
      (node (ref "R58") (pin "2") (pinfunction "2_2") (pintype "passive"))
      (node (ref "VCA1(LEFT)") (pin "2") (pinfunction "EC+_2") (pintype "passive"))
    )
    (net (code "102") (name "Net-(IC9B--IN)") (class "Default")
      (node (ref "C59") (pin "1") (pinfunction "1_1") (pintype "passive"))
      (node (ref "IC9") (pin "6") (pinfunction "-IN_6") (pintype "input"))
      (node (ref "R54") (pin "1") (pinfunction "1_1") (pintype "passive"))
      (node (ref "R55") (pin "2") (pinfunction "2_2") (pintype "passive"))
      (node (ref "R56") (pin "2") (pinfunction "2_2") (pintype "passive"))
    )
    (net (code "103") (name "Net-(IC9B-OUT)") (class "Default")
      (node (ref "C59") (pin "2") (pinfunction "2_2") (pintype "passive"))
      (node (ref "IC9") (pin "7") (pinfunction "OUT_7") (pintype "output"))
      (node (ref "R14") (pin "1") (pinfunction "1_1") (pintype "passive"))
      (node (ref "R54") (pin "2") (pinfunction "2_2") (pintype "passive"))
      (node (ref "VCA2(RIGHT)") (pin "2") (pinfunction "EC+_2") (pintype "passive"))
    )
    (net (code "104") (name "Net-(K6B-P)") (class "Default")
      (node (ref "K6") (pin "P1") (pinfunction "P_P1") (pintype "passive"))
      (node (ref "K7") (pin "Q1") (pinfunction "O_Q1") (pintype "passive"))
      (node (ref "K8") (pin "S1") (pinfunction "S_S1") (pintype "passive"))
    )
    (net (code "105") (name "Net-(K6B-S)") (class "Default")
      (node (ref "K6") (pin "S1") (pinfunction "S_S1") (pintype "passive"))
      (node (ref "U7") (pin "5") (pinfunction "SEN_5") (pintype "output"))
      (node (ref "U7") (pin "6") (pinfunction "OUT_6") (pintype "output"))
    )
    (net (code "106") (name "Net-(K6C-P)") (class "Default")
      (node (ref "K6") (pin "P2") (pinfunction "P_P2") (pintype "passive"))
      (node (ref "K7") (pin "S1") (pinfunction "S_S1") (pintype "passive"))
      (node (ref "K8") (pin "Q1") (pinfunction "O_Q1") (pintype "passive"))
    )
    (net (code "107") (name "Net-(K6C-S)") (class "Default")
      (node (ref "K6") (pin "S2") (pinfunction "S_S2") (pintype "passive"))
      (node (ref "U8") (pin "5") (pinfunction "SEN_5") (pintype "output"))
      (node (ref "U8") (pin "6") (pinfunction "OUT_6") (pintype "output"))
    )
    (net (code "108") (name "Net-(L1--)") (class "Default")
      (node (ref "L1") (pin "1") (pinfunction "-_1") (pintype "passive"))
      (node (ref "R7") (pin "2") (pinfunction "2_2") (pintype "passive"))
    )
    (net (code "109") (name "Net-(L2--)") (class "Default")
      (node (ref "L2") (pin "1") (pinfunction "-_1") (pintype "passive"))
      (node (ref "R8") (pin "2") (pinfunction "2_2") (pintype "passive"))
    )
    (net (code "110") (name "Net-(L3--)") (class "Default")
      (node (ref "L3") (pin "1") (pinfunction "-_1") (pintype "passive"))
      (node (ref "R9") (pin "2") (pinfunction "2_2") (pintype "passive"))
    )
    (net (code "111") (name "Net-(L4--)") (class "Default")
      (node (ref "L4") (pin "1") (pinfunction "-_1") (pintype "passive"))
      (node (ref "R10") (pin "2") (pinfunction "2_2") (pintype "passive"))
    )
    (net (code "112") (name "Net-(L5--)") (class "Default")
      (node (ref "L5") (pin "1") (pinfunction "-_1") (pintype "passive"))
      (node (ref "R11") (pin "2") (pinfunction "2_2") (pintype "passive"))
    )
    (net (code "113") (name "Net-(L6--)") (class "Default")
      (node (ref "L6") (pin "1") (pinfunction "-_1") (pintype "passive"))
      (node (ref "R12") (pin "2") (pinfunction "2_2") (pintype "passive"))
    )
    (net (code "114") (name "Net-(Q1-Pad1)") (class "Default")
      (node (ref "Q1") (pin "1") (pinfunction "1_1") (pintype "passive"))
      (node (ref "USB1") (pin "P$1") (pinfunction "P$1_P$1") (pintype "bidirectional"))
      (node (ref "USB1") (pin "P$2") (pinfunction "P$2_P$2") (pintype "bidirectional"))
      (node (ref "V1") (pin "2") (pinfunction "2_2") (pintype "passive"))
      (node (ref "V2") (pin "2") (pinfunction "2_2") (pintype "passive"))
    )
    (net (code "115") (name "Net-(U5-{slash}_HWB_{slash}_AIN6_{slash}_T0_{slash}_INT7)_PD7)") (class "Default")
      (node (ref "C43") (pin "2") (pinfunction "2_2") (pintype "passive"))
      (node (ref "R45") (pin "2") (pinfunction "2_2") (pintype "passive"))
      (node (ref "U5") (pin "13") (pinfunction "/_HWB_/_AIN6_/_T0_/_INT7)_PD7_13") (pintype "bidirectional"))
    )
    (net (code "116") (name "Net-(VCA1(LEFT)-IN)") (class "Default")
      (node (ref "R52") (pin "2") (pinfunction "2_2") (pintype "passive"))
      (node (ref "VCA1(LEFT)") (pin "1") (pinfunction "IN_1") (pintype "input"))
    )
    (net (code "117") (name "Net-(VCA1(LEFT)-SYM)") (class "Default")
      (node (ref "R62") (pin "1") (pinfunction "1_1") (pintype "passive"))
      (node (ref "R63") (pin "1") (pinfunction "1_1") (pintype "passive"))
      (node (ref "R64") (pin "2") (pinfunction "2_2") (pintype "passive"))
      (node (ref "VCA1(LEFT)") (pin "4") (pinfunction "SYM_4") (pintype "passive"))
    )
    (net (code "118") (name "Net-(VCA1(LEFT)-V-)") (class "Default")
      (node (ref "C63") (pin "1") (pinfunction "1_1") (pintype "passive"))
      (node (ref "R50") (pin "2") (pinfunction "2_2") (pintype "passive"))
      (node (ref "VCA1(LEFT)") (pin "5") (pinfunction "V-_5") (pintype "power_in"))
    )
    (net (code "119") (name "Net-(VCA2(RIGHT)-IN)") (class "Default")
      (node (ref "R53") (pin "2") (pinfunction "2_2") (pintype "passive"))
      (node (ref "VCA2(RIGHT)") (pin "1") (pinfunction "IN_1") (pintype "input"))
    )
    (net (code "120") (name "Net-(VCA2(RIGHT)-SYM)") (class "Default")
      (node (ref "R65") (pin "1") (pinfunction "1_1") (pintype "passive"))
      (node (ref "R66") (pin "2") (pinfunction "2_2") (pintype "passive"))
      (node (ref "R67") (pin "1") (pinfunction "1_1") (pintype "passive"))
      (node (ref "VCA2(RIGHT)") (pin "4") (pinfunction "SYM_4") (pintype "passive"))
    )
    (net (code "121") (name "Net-(VCA2(RIGHT)-V-)") (class "Default")
      (node (ref "C60") (pin "1") (pinfunction "1_1") (pintype "passive"))
      (node (ref "R51") (pin "2") (pinfunction "2_2") (pintype "passive"))
      (node (ref "VCA2(RIGHT)") (pin "5") (pinfunction "V-_5") (pintype "power_in"))
    )
    (net (code "122") (name "OUT1_DRIVER") (class "Default")
      (node (ref "BY_1_1") (pin "2") (pinfunction "2_2") (pintype "passive"))
      (node (ref "BY_1_2") (pin "2") (pinfunction "2_2") (pintype "passive"))
      (node (ref "R7") (pin "1") (pinfunction "1_1") (pintype "passive"))
      (node (ref "U12") (pin "16") (pinfunction "OUT1_16") (pintype "bidirectional"))
    )
    (net (code "123") (name "OUT2_DRIVER") (class "Default")
      (node (ref "BY_2_1") (pin "2") (pinfunction "2_2") (pintype "passive"))
      (node (ref "BY_2_2") (pin "2") (pinfunction "2_2") (pintype "passive"))
      (node (ref "R8") (pin "1") (pinfunction "1_1") (pintype "passive"))
      (node (ref "U12") (pin "15") (pinfunction "OUT2_15") (pintype "bidirectional"))
    )
    (net (code "124") (name "OUT3_DRIVER") (class "Default")
      (node (ref "K5") (pin "2") (pinfunction "2_2") (pintype "passive"))
      (node (ref "R9") (pin "1") (pinfunction "1_1") (pintype "passive"))
      (node (ref "U12") (pin "14") (pinfunction "OUT3_14") (pintype "bidirectional"))
    )
    (net (code "125") (name "OUT4_DRIVER") (class "Default")
      (node (ref "K6") (pin "2") (pinfunction "2_2") (pintype "passive"))
      (node (ref "R10") (pin "1") (pinfunction "1_1") (pintype "passive"))
      (node (ref "U12") (pin "13") (pinfunction "OUT4_13") (pintype "bidirectional"))
    )
    (net (code "126") (name "OUT5_DRIVER") (class "Default")
      (node (ref "K7") (pin "2") (pinfunction "2_2") (pintype "passive"))
      (node (ref "R11") (pin "1") (pinfunction "1_1") (pintype "passive"))
      (node (ref "U12") (pin "12") (pinfunction "OUT5_12") (pintype "bidirectional"))
    )
    (net (code "127") (name "OUT6_DRIVER") (class "Default")
      (node (ref "K8") (pin "2") (pinfunction "2_2") (pintype "passive"))
      (node (ref "R12") (pin "1") (pinfunction "1_1") (pintype "passive"))
      (node (ref "U12") (pin "11") (pinfunction "OUT6_11") (pintype "bidirectional"))
    )
    (net (code "128") (name "OUT_L{slash}M") (class "Default")
      (node (ref "K7") (pin "P1") (pinfunction "P_P1") (pintype "passive"))
      (node (ref "OUT_LEFT") (pin "4") (pinfunction "IN_4") (pintype "input"))
    )
    (net (code "129") (name "OUT_R{slash}S") (class "Default")
      (node (ref "K8") (pin "P1") (pinfunction "P_P1") (pintype "passive"))
      (node (ref "OUT_RIGHT") (pin "4") (pinfunction "IN_4") (pintype "input"))
    )
    (net (code "130") (name "R") (class "Default")
      (node (ref "IC4") (pin "5") (pinfunction "+IN_5") (pintype "input"))
      (node (ref "IN_RIGHT") (pin "5") (pinfunction "SEN_5") (pintype "output"))
      (node (ref "IN_RIGHT") (pin "6") (pinfunction "OUT_6") (pintype "output"))
      (node (ref "K5") (pin "Q2") (pinfunction "O_Q2") (pintype "passive"))
      (node (ref "R19") (pin "1") (pinfunction "1_1") (pintype "passive"))
    )
    (net (code "131") (name "R_SIGNAL") (class "Default")
      (node (ref "R") (pin "2") (pinfunction "2_2") (pintype "passive"))
      (node (ref "TP02") (pin "P$1") (pinfunction "TP_P$1") (pintype "input"))
      (node (ref "U1") (pin "96") (pinfunction "PF1_(ADC1)_96") (pintype "bidirectional"))
      (node (ref "U10") (pin "24") (pinfunction "PC1_24") (pintype "bidirectional"))
      (node (ref "U11") (pin "24") (pinfunction "PC1_24") (pintype "bidirectional"))
    )
    (net (code "132") (name "R{slash}S_IN(VCA2_IN)") (class "Default")
      (node (ref "C68") (pin "+") (pinfunction "+_+") (pintype "passive"))
      (node (ref "K5") (pin "P2") (pinfunction "P_P2") (pintype "passive"))
    )
    (net (code "133") (name "R{slash}S_OUT(VCA2_OUT)") (class "Default")
      (node (ref "C56") (pin "2") (pinfunction "2_2") (pintype "passive"))
      (node (ref "IC1") (pin "5") (pinfunction "+IN_5") (pintype "input"))
      (node (ref "IC8") (pin "7") (pinfunction "OUT_7") (pintype "output"))
      (node (ref "K6") (pin "Q2") (pinfunction "O_Q2") (pintype "passive"))
      (node (ref "R27") (pin "1") (pinfunction "1_1") (pintype "passive"))
      (node (ref "R49") (pin "2") (pinfunction "2_2") (pintype "passive"))
    )
    (net (code "134") (name "R{slash}S_OUT_SIGNAL") (class "Default")
      (node (ref "R/S_OUT") (pin "2") (pinfunction "2_2") (pintype "passive"))
      (node (ref "TP04") (pin "P$1") (pinfunction "TP_P$1") (pintype "input"))
      (node (ref "U1") (pin "92") (pinfunction "PF5_(ADC5/TMS)_92") (pintype "bidirectional"))
      (node (ref "U10") (pin "28") (pinfunction "PC5_28") (pintype "bidirectional"))
      (node (ref "U11") (pin "28") (pinfunction "PC5_28") (pintype "bidirectional"))
    )
    (net (code "135") (name "S") (class "Default")
      (node (ref "K5") (pin "S2") (pinfunction "S_S2") (pintype "passive"))
      (node (ref "R23") (pin "1") (pinfunction "1_1") (pintype "passive"))
      (node (ref "U6") (pin "5") (pinfunction "SEN_5") (pintype "output"))
      (node (ref "U6") (pin "6") (pinfunction "OUT_6") (pintype "output"))
    )
    (net (code "136") (name "S_SIGNAL") (class "Default")
      (node (ref "S") (pin "2") (pinfunction "2_2") (pintype "passive"))
      (node (ref "TP06") (pin "P$1") (pinfunction "TP_P$1") (pintype "input"))
      (node (ref "U1") (pin "94") (pinfunction "PF3_(ADC3)_94") (pintype "bidirectional"))
      (node (ref "U10") (pin "26") (pinfunction "PC3_26") (pintype "bidirectional"))
      (node (ref "U11") (pin "26") (pinfunction "PC3_26") (pintype "bidirectional"))
    )
    (net (code "137") (name "UCAP") (class "Default")
      (node (ref "C31") (pin "2") (pinfunction "2_2") (pintype "passive"))
      (node (ref "U5") (pin "27") (pinfunction "UCAP_27") (pintype "passive"))
    )
    (net (code "138") (name "USB_µC_MISO") (class "Default")
      (node (ref "U5") (pin "17") (pinfunction "PB3_(PDO_/_MISO_/_PCINT3)_17") (pintype "bidirectional"))
      (node (ref "U5_PROG") (pin "1") (pinfunction "P$1_1") (pintype "bidirectional"))
    )
    (net (code "139") (name "USB_µC_MOSI") (class "Default")
      (node (ref "U5") (pin "16") (pinfunction "(PDI_/_MOSI_/_PCINT2)_PB2_16") (pintype "bidirectional"))
      (node (ref "U5_PROG") (pin "4") (pinfunction "P$4_4") (pintype "bidirectional"))
    )
    (net (code "140") (name "USB_µC_RESET") (class "Default")
      (node (ref "D1") (pin "A") (pinfunction "A_A") (pintype "passive"))
      (node (ref "R4") (pin "1") (pinfunction "1_1") (pintype "passive"))
      (node (ref "U5") (pin "24") (pinfunction "~{RESET_(PC1_/_DW})_24") (pintype "input"))
      (node (ref "U5_PROG") (pin "5") (pinfunction "P$5_5") (pintype "bidirectional"))
    )
    (net (code "141") (name "USB_µC_RX") (class "Default")
      (node (ref "R6") (pin "1") (pinfunction "1_1") (pintype "passive"))
      (node (ref "U5") (pin "8") (pinfunction "(RXD1_/_AIN1_/_INT2)_PD2_8") (pintype "bidirectional"))
    )
    (net (code "142") (name "USB_µC_SCK") (class "Default")
      (node (ref "U5") (pin "15") (pinfunction "(SCLK_/_PCINT1)_PB1_15") (pintype "bidirectional"))
      (node (ref "U5_PROG") (pin "3") (pinfunction "P$3_3") (pintype "bidirectional"))
    )
    (net (code "143") (name "USB_µC_TX") (class "Default")
      (node (ref "R5") (pin "1") (pinfunction "1_1") (pintype "passive"))
      (node (ref "U5") (pin "9") (pinfunction "(TXD1_/_INT3)_PD3_9") (pintype "bidirectional"))
    )
    (net (code "144") (name "USB_µC_UGND") (class "Default")
      (node (ref "C31") (pin "1") (pinfunction "1_1") (pintype "passive"))
      (node (ref "Q1") (pin "2") (pinfunction "2_2") (pintype "passive"))
      (node (ref "U5") (pin "28") (pinfunction "UGND_28") (pintype "passive"))
      (node (ref "USB1") (pin "4") (pinfunction "4_4") (pintype "bidirectional"))
    )
    (net (code "145") (name "USB_µC_XTAL1") (class "Default")
      (node (ref "C24") (pin "2") (pinfunction "2_2") (pintype "passive"))
      (node (ref "QA1") (pin "2") (pinfunction "2_2") (pintype "passive"))
      (node (ref "R3") (pin "2") (pinfunction "2_2") (pintype "passive"))
      (node (ref "U5") (pin "1") (pinfunction "XTAL1_1") (pintype "input"))
    )
    (net (code "146") (name "USB_µC_XTAL2") (class "Default")
      (node (ref "C23") (pin "2") (pinfunction "2_2") (pintype "passive"))
      (node (ref "QA1") (pin "1") (pinfunction "1_1") (pintype "passive"))
      (node (ref "R3") (pin "1") (pinfunction "1_1") (pintype "passive"))
      (node (ref "U5") (pin "2") (pinfunction "(PC0)_XTAL2_2") (pintype "output"))
    )
    (net (code "147") (name "UVCC") (class "Default")
      (node (ref "C32") (pin "1") (pinfunction "1_1") (pintype "passive"))
      (node (ref "F1") (pin "2") (pinfunction "2_2") (pintype "bidirectional"))
      (node (ref "U5") (pin "31") (pinfunction "UVCC_31") (pintype "power_in"))
    )
    (net (code "148") (name "V+") (class "Default")
      (node (ref "C1") (pin "1") (pinfunction "1_1") (pintype "passive"))
      (node (ref "C10") (pin "1") (pinfunction "1_1") (pintype "passive"))
      (node (ref "C11") (pin "1") (pinfunction "1_1") (pintype "passive"))
      (node (ref "C13") (pin "1") (pinfunction "1_1") (pintype "passive"))
      (node (ref "C16") (pin "1") (pinfunction "1_1") (pintype "passive"))
      (node (ref "C18") (pin "1") (pinfunction "1_1") (pintype "passive"))
      (node (ref "C22") (pin "1") (pinfunction "1_1") (pintype "passive"))
      (node (ref "C26") (pin "1") (pinfunction "1_1") (pintype "passive"))
      (node (ref "C28") (pin "1") (pinfunction "1_1") (pintype "passive"))
      (node (ref "C3") (pin "1") (pinfunction "1_1") (pintype "passive"))
      (node (ref "C30") (pin "1") (pinfunction "1_1") (pintype "passive"))
      (node (ref "C5") (pin "1") (pinfunction "1_1") (pintype "passive"))
      (node (ref "C51") (pin "2") (pinfunction "2_2") (pintype "passive"))
      (node (ref "C53") (pin "1") (pinfunction "1_1") (pintype "passive"))
      (node (ref "C58") (pin "1") (pinfunction "1_1") (pintype "passive"))
      (node (ref "C61") (pin "1") (pinfunction "1_1") (pintype "passive"))
      (node (ref "C62") (pin "1") (pinfunction "1_1") (pintype "passive"))
      (node (ref "C7") (pin "1") (pinfunction "1_1") (pintype "passive"))
      (node (ref "CONN3") (pin "1") (pinfunction "KL_1") (pintype "passive"))
      (node (ref "IC1") (pin "8") (pinfunction "V+_8") (pintype "power_in"))
      (node (ref "IC2") (pin "8") (pinfunction "V+_8") (pintype "power_in"))
      (node (ref "IC3") (pin "8") (pinfunction "V+_8") (pintype "power_in"))
      (node (ref "IC4") (pin "8") (pinfunction "V+_8") (pintype "power_in"))
      (node (ref "IC6") (pin "8") (pinfunction "V+_8") (pintype "power_in"))
      (node (ref "IC8") (pin "8") (pinfunction "V+_8") (pintype "power_in"))
      (node (ref "IC9") (pin "8") (pinfunction "V+_8") (pintype "power_in"))
      (node (ref "IN_LEFT") (pin "7") (pinfunction "V+_7") (pintype "power_in"))
      (node (ref "IN_RIGHT") (pin "7") (pinfunction "V+_7") (pintype "power_in"))
      (node (ref "OUT_LEFT") (pin "6") (pinfunction "V+_6") (pintype "power_in"))
      (node (ref "OUT_RIGHT") (pin "6") (pinfunction "V+_6") (pintype "power_in"))
      (node (ref "TP09") (pin "P$1") (pinfunction "TP_P$1") (pintype "input"))
      (node (ref "TP13") (pin "P$1") (pinfunction "TP_P$1") (pintype "input"))
      (node (ref "TP24") (pin "P$1") (pinfunction "TP_P$1") (pintype "input"))
      (node (ref "TP26") (pin "P$1") (pinfunction "TP_P$1") (pintype "input"))
      (node (ref "U4") (pin "7") (pinfunction "V+_7") (pintype "power_in"))
      (node (ref "U6") (pin "7") (pinfunction "V+_7") (pintype "power_in"))
      (node (ref "U7") (pin "7") (pinfunction "V+_7") (pintype "power_in"))
      (node (ref "U8") (pin "7") (pinfunction "V+_7") (pintype "power_in"))
      (node (ref "UR1") (pin "1") (pinfunction "VI_1") (pintype "input"))
      (node (ref "VCA1(LEFT)") (pin "7") (pinfunction "V+_7") (pintype "power_in"))
      (node (ref "VCA2(RIGHT)") (pin "7") (pinfunction "V+_7") (pintype "power_in"))
    )
    (net (code "149") (name "V-") (class "Default")
      (node (ref "C12") (pin "1") (pinfunction "1_1") (pintype "passive"))
      (node (ref "C14") (pin "1") (pinfunction "1_1") (pintype "passive"))
      (node (ref "C15") (pin "1") (pinfunction "1_1") (pintype "passive"))
      (node (ref "C17") (pin "1") (pinfunction "1_1") (pintype "passive"))
      (node (ref "C2") (pin "1") (pinfunction "1_1") (pintype "passive"))
      (node (ref "C21") (pin "1") (pinfunction "1_1") (pintype "passive"))
      (node (ref "C25") (pin "1") (pinfunction "1_1") (pintype "passive"))
      (node (ref "C27") (pin "1") (pinfunction "1_1") (pintype "passive"))
      (node (ref "C29") (pin "1") (pinfunction "1_1") (pintype "passive"))
      (node (ref "C4") (pin "1") (pinfunction "1_1") (pintype "passive"))
      (node (ref "C54") (pin "1") (pinfunction "1_1") (pintype "passive"))
      (node (ref "C57") (pin "1") (pinfunction "1_1") (pintype "passive"))
      (node (ref "C6") (pin "1") (pinfunction "1_1") (pintype "passive"))
      (node (ref "C8") (pin "1") (pinfunction "1_1") (pintype "passive"))
      (node (ref "C9") (pin "1") (pinfunction "1_1") (pintype "passive"))
      (node (ref "CONN3") (pin "3") (pinfunction "KL_3") (pintype "passive"))
      (node (ref "IC1") (pin "4") (pinfunction "V-_4") (pintype "power_in"))
      (node (ref "IC2") (pin "4") (pinfunction "V-_4") (pintype "power_in"))
      (node (ref "IC3") (pin "4") (pinfunction "V-_4") (pintype "power_in"))
      (node (ref "IC4") (pin "4") (pinfunction "V-_4") (pintype "power_in"))
      (node (ref "IC6") (pin "4") (pinfunction "V-_4") (pintype "power_in"))
      (node (ref "IC8") (pin "4") (pinfunction "V-_4") (pintype "power_in"))
      (node (ref "IC9") (pin "4") (pinfunction "V-_4") (pintype "power_in"))
      (node (ref "IN_LEFT") (pin "4") (pinfunction "V-_4") (pintype "power_in"))
      (node (ref "IN_RIGHT") (pin "4") (pinfunction "V-_4") (pintype "power_in"))
      (node (ref "OUT_LEFT") (pin "5") (pinfunction "V-_5") (pintype "power_in"))
      (node (ref "OUT_RIGHT") (pin "5") (pinfunction "V-_5") (pintype "power_in"))
      (node (ref "R50") (pin "1") (pinfunction "1_1") (pintype "passive"))
      (node (ref "R51") (pin "1") (pinfunction "1_1") (pintype "passive"))
      (node (ref "R55") (pin "1") (pinfunction "1_1") (pintype "passive"))
      (node (ref "R61") (pin "1") (pinfunction "1_1") (pintype "passive"))
      (node (ref "R63") (pin "2") (pinfunction "2_2") (pintype "passive"))
      (node (ref "R65") (pin "2") (pinfunction "2_2") (pintype "passive"))
      (node (ref "TP10") (pin "P$1") (pinfunction "TP_P$1") (pintype "input"))
      (node (ref "TP17") (pin "P$1") (pinfunction "TP_P$1") (pintype "input"))
      (node (ref "TP23") (pin "P$1") (pinfunction "TP_P$1") (pintype "input"))
      (node (ref "TP25") (pin "P$1") (pinfunction "TP_P$1") (pintype "input"))
      (node (ref "U4") (pin "4") (pinfunction "V-_4") (pintype "power_in"))
      (node (ref "U6") (pin "4") (pinfunction "V-_4") (pintype "power_in"))
      (node (ref "U7") (pin "4") (pinfunction "V-_4") (pintype "power_in"))
      (node (ref "U8") (pin "4") (pinfunction "V-_4") (pintype "power_in"))
    )
    (net (code "150") (name "VCA1_A6") (class "Default")
      (node (ref "U10") (pin "19") (pinfunction "ADC6_19") (pintype "input"))
    )
    (net (code "151") (name "VCA1_A7") (class "Default")
      (node (ref "U10") (pin "22") (pinfunction "ADC7_22") (pintype "input"))
    )
    (net (code "152") (name "VCA1_AREF") (class "Default")
      (node (ref "C37") (pin "2") (pinfunction "2_2") (pintype "passive"))
      (node (ref "U10") (pin "20") (pinfunction "AREF_20") (pintype "input"))
    )
    (net (code "153") (name "VCA1_D2") (class "Default")
      (node (ref "R35") (pin "1") (pinfunction "1_1") (pintype "passive"))
      (node (ref "U10") (pin "32") (pinfunction "PD2_32") (pintype "bidirectional"))
    )
    (net (code "154") (name "VCA1_D3") (class "Default")
      (node (ref "U10") (pin "1") (pinfunction "PD3_1") (pintype "bidirectional"))
    )
    (net (code "155") (name "VCA1_D4") (class "Default")
      (node (ref "U10") (pin "2") (pinfunction "PD4_2") (pintype "bidirectional"))
    )
    (net (code "156") (name "VCA1_D5") (class "Default")
      (node (ref "U10") (pin "9") (pinfunction "PD5_9") (pintype "bidirectional"))
    )
    (net (code "157") (name "VCA1_D6") (class "Default")
      (node (ref "U10") (pin "10") (pinfunction "PD6_10") (pintype "bidirectional"))
    )
    (net (code "158") (name "VCA1_D7") (class "Default")
      (node (ref "U10") (pin "11") (pinfunction "PD7_11") (pintype "bidirectional"))
    )
    (net (code "159") (name "VCA1_D8") (class "Default")
      (node (ref "U10") (pin "12") (pinfunction "PB0_12") (pintype "bidirectional"))
    )
    (net (code "160") (name "VCA1_D9") (class "Default")
      (node (ref "U10") (pin "13") (pinfunction "PB1_13") (pintype "bidirectional"))
    )
    (net (code "161") (name "VCA1_D10") (class "Default")
      (node (ref "U10") (pin "14") (pinfunction "PB2_14") (pintype "bidirectional"))
    )
    (net (code "162") (name "VCA1_D11(MOSI)") (class "Default")
      (node (ref "R37") (pin "1") (pinfunction "1_1") (pintype "passive"))
      (node (ref "U10") (pin "15") (pinfunction "PB3_15") (pintype "bidirectional"))
      (node (ref "U10_PROG") (pin "4") (pinfunction "P$4_4") (pintype "bidirectional"))
    )
    (net (code "163") (name "VCA1_D12(MISO)") (class "Default")
      (node (ref "U10") (pin "16") (pinfunction "PB4_16") (pintype "bidirectional"))
      (node (ref "U10_PROG") (pin "1") (pinfunction "P$1_1") (pintype "bidirectional"))
    )
    (net (code "164") (name "VCA1_D13(SCK)") (class "Default")
      (node (ref "R36") (pin "1") (pinfunction "1_1") (pintype "passive"))
      (node (ref "U10") (pin "17") (pinfunction "PB5_17") (pintype "bidirectional"))
      (node (ref "U10_PROG") (pin "3") (pinfunction "P$3_3") (pintype "bidirectional"))
    )
    (net (code "165") (name "VCA1_EC+") (class "Default")
      (node (ref "R29") (pin "2") (pinfunction "2_2") (pintype "passive"))
      (node (ref "TP37") (pin "P$1") (pinfunction "TP_P$1") (pintype "input"))
      (node (ref "U1") (pin "90") (pinfunction "PF7_(ADC7/TDI)_90") (pintype "bidirectional"))
    )
    (net (code "166") (name "VCA1_RESET") (class "Default")
      (node (ref "R16") (pin "1") (pinfunction "1_1") (pintype "passive"))
      (node (ref "U10") (pin "29") (pinfunction "PC6_29") (pintype "bidirectional"))
      (node (ref "U10_PROG") (pin "5") (pinfunction "P$5_5") (pintype "bidirectional"))
    )
    (net (code "167") (name "VCA1_µC_RX") (class "Default")
      (node (ref "R42") (pin "1") (pinfunction "1_1") (pintype "passive"))
      (node (ref "U10") (pin "30") (pinfunction "PD0_30") (pintype "bidirectional"))
    )
    (net (code "168") (name "VCA1_µC_TX") (class "Default")
      (node (ref "R41") (pin "1") (pinfunction "1_1") (pintype "passive"))
      (node (ref "U10") (pin "31") (pinfunction "PD1_31") (pintype "bidirectional"))
    )
    (net (code "169") (name "VCA2_A6") (class "Default")
      (node (ref "U11") (pin "19") (pinfunction "ADC6_19") (pintype "input"))
    )
    (net (code "170") (name "VCA2_A7") (class "Default")
      (node (ref "U11") (pin "22") (pinfunction "ADC7_22") (pintype "input"))
    )
    (net (code "171") (name "VCA2_AREF") (class "Default")
      (node (ref "C42") (pin "2") (pinfunction "2_2") (pintype "passive"))
      (node (ref "U11") (pin "20") (pinfunction "AREF_20") (pintype "input"))
    )
    (net (code "172") (name "VCA2_D2") (class "Default")
      (node (ref "R40") (pin "1") (pinfunction "1_1") (pintype "passive"))
      (node (ref "U11") (pin "32") (pinfunction "PD2_32") (pintype "bidirectional"))
    )
    (net (code "173") (name "VCA2_D3") (class "Default")
      (node (ref "U11") (pin "1") (pinfunction "PD3_1") (pintype "bidirectional"))
    )
    (net (code "174") (name "VCA2_D4") (class "Default")
      (node (ref "U11") (pin "2") (pinfunction "PD4_2") (pintype "bidirectional"))
    )
    (net (code "175") (name "VCA2_D5") (class "Default")
      (node (ref "U11") (pin "9") (pinfunction "PD5_9") (pintype "bidirectional"))
    )
    (net (code "176") (name "VCA2_D6") (class "Default")
      (node (ref "U11") (pin "10") (pinfunction "PD6_10") (pintype "bidirectional"))
    )
    (net (code "177") (name "VCA2_D7") (class "Default")
      (node (ref "U11") (pin "11") (pinfunction "PD7_11") (pintype "bidirectional"))
    )
    (net (code "178") (name "VCA2_D8") (class "Default")
      (node (ref "U11") (pin "12") (pinfunction "PB0_12") (pintype "bidirectional"))
    )
    (net (code "179") (name "VCA2_D9") (class "Default")
      (node (ref "U11") (pin "13") (pinfunction "PB1_13") (pintype "bidirectional"))
    )
    (net (code "180") (name "VCA2_D10") (class "Default")
      (node (ref "U11") (pin "14") (pinfunction "PB2_14") (pintype "bidirectional"))
    )
    (net (code "181") (name "VCA2_D11(MOSI)") (class "Default")
      (node (ref "R38") (pin "1") (pinfunction "1_1") (pintype "passive"))
      (node (ref "U11") (pin "15") (pinfunction "PB3_15") (pintype "bidirectional"))
      (node (ref "U11_PROG") (pin "4") (pinfunction "P$4_4") (pintype "bidirectional"))
    )
    (net (code "182") (name "VCA2_D12(MISO)") (class "Default")
      (node (ref "U11") (pin "16") (pinfunction "PB4_16") (pintype "bidirectional"))
      (node (ref "U11_PROG") (pin "1") (pinfunction "P$1_1") (pintype "bidirectional"))
    )
    (net (code "183") (name "VCA2_D13(SCK)") (class "Default")
      (node (ref "R39") (pin "1") (pinfunction "1_1") (pintype "passive"))
      (node (ref "U11") (pin "17") (pinfunction "PB5_17") (pintype "bidirectional"))
      (node (ref "U11_PROG") (pin "3") (pinfunction "P$3_3") (pintype "bidirectional"))
    )
    (net (code "184") (name "VCA2_EC+") (class "Default")
      (node (ref "R14") (pin "2") (pinfunction "2_2") (pintype "passive"))
      (node (ref "TP36") (pin "P$1") (pinfunction "TP_P$1") (pintype "input"))
      (node (ref "U1") (pin "91") (pinfunction "PF6_(ADC6/TDO)_91") (pintype "bidirectional"))
    )
    (net (code "185") (name "VCA2_RESET") (class "Default")
      (node (ref "R34") (pin "1") (pinfunction "1_1") (pintype "passive"))
      (node (ref "U11") (pin "29") (pinfunction "PC6_29") (pintype "bidirectional"))
      (node (ref "U11_PROG") (pin "5") (pinfunction "P$5_5") (pintype "bidirectional"))
    )
    (net (code "186") (name "VCA2_µC_RX") (class "Default")
      (node (ref "R44") (pin "1") (pinfunction "1_1") (pintype "passive"))
      (node (ref "U11") (pin "30") (pinfunction "PD0_30") (pintype "bidirectional"))
    )
    (net (code "187") (name "VCA2_µC_TX") (class "Default")
      (node (ref "R43") (pin "1") (pinfunction "1_1") (pintype "passive"))
      (node (ref "U11") (pin "31") (pinfunction "PD1_31") (pintype "bidirectional"))
    )
    (net (code "188") (name "XTAL1_VCA1") (class "Default")
      (node (ref "C33") (pin "2") (pinfunction "2_2") (pintype "passive"))
      (node (ref "QA2") (pin "2") (pinfunction "2_2") (pintype "passive"))
      (node (ref "R15") (pin "2") (pinfunction "2_2") (pintype "passive"))
      (node (ref "U10") (pin "7") (pinfunction "PB6_7") (pintype "bidirectional"))
    )
    (net (code "189") (name "XTAL1_VCA2") (class "Default")
      (node (ref "C38") (pin "2") (pinfunction "2_2") (pintype "passive"))
      (node (ref "QA3") (pin "2") (pinfunction "2_2") (pintype "passive"))
      (node (ref "R33") (pin "2") (pinfunction "2_2") (pintype "passive"))
      (node (ref "U11") (pin "7") (pinfunction "PB6_7") (pintype "bidirectional"))
    )
    (net (code "190") (name "XTAL2_VCA1") (class "Default")
      (node (ref "C34") (pin "2") (pinfunction "2_2") (pintype "passive"))
      (node (ref "QA2") (pin "1") (pinfunction "1_1") (pintype "passive"))
      (node (ref "R15") (pin "1") (pinfunction "1_1") (pintype "passive"))
      (node (ref "U10") (pin "8") (pinfunction "PB7_8") (pintype "bidirectional"))
    )
    (net (code "191") (name "XTAL2_VCA2") (class "Default")
      (node (ref "C39") (pin "2") (pinfunction "2_2") (pintype "passive"))
      (node (ref "QA3") (pin "1") (pinfunction "1_1") (pintype "passive"))
      (node (ref "R33") (pin "1") (pinfunction "1_1") (pintype "passive"))
      (node (ref "U11") (pin "8") (pinfunction "PB7_8") (pintype "bidirectional"))
    )
    (net (code "192") (name "unconnected-(K7C-O-PadQ2)") (class "Default")
      (node (ref "K7") (pin "Q2") (pinfunction "O_Q2") (pintype "passive"))
    )
    (net (code "193") (name "unconnected-(K7C-P-PadP2)") (class "Default")
      (node (ref "K7") (pin "P2") (pinfunction "P_P2") (pintype "passive"))
    )
    (net (code "194") (name "unconnected-(K7C-S-PadS2)") (class "Default")
      (node (ref "K7") (pin "S2") (pinfunction "S_S2") (pintype "passive"))
    )
    (net (code "195") (name "unconnected-(K8C-O-PadQ2)") (class "Default")
      (node (ref "K8") (pin "Q2") (pinfunction "O_Q2") (pintype "passive"))
    )
    (net (code "196") (name "unconnected-(K8C-P-PadP2)") (class "Default")
      (node (ref "K8") (pin "P2") (pinfunction "P_P2") (pintype "passive"))
    )
    (net (code "197") (name "unconnected-(K8C-S-PadS2)") (class "Default")
      (node (ref "K8") (pin "S2") (pinfunction "S_S2") (pintype "passive"))
    )
    (net (code "198") (name "unconnected-(OUT1(R/S)-PadG)") (class "Default")
      (node (ref "OUT1(R/S)") (pin "G") (pinfunction "G_G") (pintype "bidirectional"))
    )
    (net (code "199") (name "unconnected-(OUT2(L/M)-PadG)") (class "Default")
      (node (ref "OUT2(L/M)") (pin "G") (pinfunction "G_G") (pintype "bidirectional"))
    )
    (net (code "200") (name "unconnected-(U1-(CLKO{slash}ICP3{slash}INT7)_PE7-Pad9)") (class "Default")
      (node (ref "U1") (pin "9") (pinfunction "(CLKO/ICP3/INT7)_PE7_9") (pintype "bidirectional"))
    )
    (net (code "201") (name "unconnected-(U1-(ICP1)_PD4-Pad47)") (class "Default")
      (node (ref "U1") (pin "47") (pinfunction "(ICP1)_PD4_47") (pintype "bidirectional"))
    )
    (net (code "202") (name "unconnected-(U1-(ICP4)_PL0-Pad35)") (class "Default")
      (node (ref "U1") (pin "35") (pinfunction "(ICP4)_PL0_35") (pintype "bidirectional"))
    )
    (net (code "203") (name "unconnected-(U1-(ICP5)_PL1-Pad36)") (class "Default")
      (node (ref "U1") (pin "36") (pinfunction "(ICP5)_PL1_36") (pintype "bidirectional"))
    )
    (net (code "204") (name "unconnected-(U1-(OC0A{slash}OC1C{slash}PCINT7)_PB7-Pad26)") (class "Default")
      (node (ref "U1") (pin "26") (pinfunction "(OC0A/OC1C/PCINT7)_PB7_26") (pintype "bidirectional"))
    )
    (net (code "205") (name "unconnected-(U1-(OC1A{slash}PCINT5)_PB5-Pad24)") (class "Default")
      (node (ref "U1") (pin "24") (pinfunction "(OC1A/PCINT5)_PB5_24") (pintype "bidirectional"))
    )
    (net (code "206") (name "unconnected-(U1-(OC1B{slash}PCINT6)_PB6-Pad25)") (class "Default")
      (node (ref "U1") (pin "25") (pinfunction "(OC1B/PCINT6)_PB6_25") (pintype "bidirectional"))
    )
    (net (code "207") (name "unconnected-(U1-(OC2A{slash}PCINT4)_PB4-Pad23)") (class "Default")
      (node (ref "U1") (pin "23") (pinfunction "(OC2A/PCINT4)_PB4_23") (pintype "bidirectional"))
    )
    (net (code "208") (name "unconnected-(U1-(OC2B)_PH6-Pad18)") (class "Default")
      (node (ref "U1") (pin "18") (pinfunction "(OC2B)_PH6_18") (pintype "bidirectional"))
    )
    (net (code "209") (name "unconnected-(U1-(OC4C)_PH5-Pad17)") (class "Default")
      (node (ref "U1") (pin "17") (pinfunction "(OC4C)_PH5_17") (pintype "bidirectional"))
    )
    (net (code "210") (name "unconnected-(U1-(OC5A)_PL3-Pad38)") (class "Default")
      (node (ref "U1") (pin "38") (pinfunction "(OC5A)_PL3_38") (pintype "bidirectional"))
    )
    (net (code "211") (name "unconnected-(U1-(OC5B)_PL4-Pad39)") (class "Default")
      (node (ref "U1") (pin "39") (pinfunction "(OC5B)_PL4_39") (pintype "bidirectional"))
    )
    (net (code "212") (name "unconnected-(U1-(SCL{slash}INT0)_PD0-Pad43)") (class "Default")
      (node (ref "U1") (pin "43") (pinfunction "(SCL/INT0)_PD0_43") (pintype "bidirectional"))
    )
    (net (code "213") (name "unconnected-(U1-(SDA{slash}INT1)_PD1-Pad44)") (class "Default")
      (node (ref "U1") (pin "44") (pinfunction "(SDA/INT1)_PD1_44") (pintype "bidirectional"))
    )
    (net (code "214") (name "unconnected-(U1-(T0)_PD7-Pad50)") (class "Default")
      (node (ref "U1") (pin "50") (pinfunction "(T0)_PD7_50") (pintype "bidirectional"))
    )
    (net (code "215") (name "unconnected-(U1-(T1)_PD6-Pad49)") (class "Default")
      (node (ref "U1") (pin "49") (pinfunction "(T1)_PD6_49") (pintype "bidirectional"))
    )
    (net (code "216") (name "unconnected-(U1-(T3{slash}INT6)_PE6-Pad8)") (class "Default")
      (node (ref "U1") (pin "8") (pinfunction "(T3/INT6)_PE6_8") (pintype "bidirectional"))
    )
    (net (code "217") (name "unconnected-(U1-(T4)_PH7-Pad27)") (class "Default")
      (node (ref "U1") (pin "27") (pinfunction "(T4)_PH7_27") (pintype "bidirectional"))
    )
    (net (code "218") (name "unconnected-(U1-(T5)_PL2-Pad37)") (class "Default")
      (node (ref "U1") (pin "37") (pinfunction "(T5)_PL2_37") (pintype "bidirectional"))
    )
    (net (code "219") (name "unconnected-(U1-(TOSC1)_PG4-Pad29)") (class "Default")
      (node (ref "U1") (pin "29") (pinfunction "(TOSC1)_PG4_29") (pintype "bidirectional"))
    )
    (net (code "220") (name "unconnected-(U1-(TOSC2)_PG3-Pad28)") (class "Default")
      (node (ref "U1") (pin "28") (pinfunction "(TOSC2)_PG3_28") (pintype "bidirectional"))
    )
    (net (code "221") (name "unconnected-(U1-(XCK0{slash}AIN0)_PE2-Pad4)") (class "Default")
      (node (ref "U1") (pin "4") (pinfunction "(XCK0/AIN0)_PE2_4") (pintype "bidirectional"))
    )
    (net (code "222") (name "unconnected-(U1-(XCK1)_PD5-Pad48)") (class "Default")
      (node (ref "U1") (pin "48") (pinfunction "(XCK1)_PD5_48") (pintype "bidirectional"))
    )
    (net (code "223") (name "unconnected-(U1-(XCK2)_PH2-Pad14)") (class "Default")
      (node (ref "U1") (pin "14") (pinfunction "(XCK2)_PH2_14") (pintype "bidirectional"))
    )
    (net (code "224") (name "unconnected-(U1-(~{SS{slash}PCINT0})_PB0-Pad19)") (class "Default")
      (node (ref "U1") (pin "19") (pinfunction "(~{SS/PCINT0})_PB0_19") (pintype "bidirectional"))
    )
    (net (code "225") (name "unconnected-(U1-OC5C)_PL5-Pad40)") (class "Default")
      (node (ref "U1") (pin "40") (pinfunction "OC5C)_PL5_40") (pintype "bidirectional"))
    )
    (net (code "226") (name "unconnected-(U1-PA0_(AD0)-Pad78)") (class "Default")
      (node (ref "U1") (pin "78") (pinfunction "PA0_(AD0)_78") (pintype "bidirectional"))
    )
    (net (code "227") (name "unconnected-(U1-PA1_(AD1)-Pad77)") (class "Default")
      (node (ref "U1") (pin "77") (pinfunction "PA1_(AD1)_77") (pintype "bidirectional"))
    )
    (net (code "228") (name "unconnected-(U1-PA2_(AD2)-Pad76)") (class "Default")
      (node (ref "U1") (pin "76") (pinfunction "PA2_(AD2)_76") (pintype "bidirectional"))
    )
    (net (code "229") (name "unconnected-(U1-PA3_(AD3)-Pad75)") (class "Default")
      (node (ref "U1") (pin "75") (pinfunction "PA3_(AD3)_75") (pintype "bidirectional"))
    )
    (net (code "230") (name "unconnected-(U1-PA4_(AD4)-Pad74)") (class "Default")
      (node (ref "U1") (pin "74") (pinfunction "PA4_(AD4)_74") (pintype "bidirectional"))
    )
    (net (code "231") (name "unconnected-(U1-PA5_(AD5)-Pad73)") (class "Default")
      (node (ref "U1") (pin "73") (pinfunction "PA5_(AD5)_73") (pintype "bidirectional"))
    )
    (net (code "232") (name "unconnected-(U1-PA6_(AD6)-Pad72)") (class "Default")
      (node (ref "U1") (pin "72") (pinfunction "PA6_(AD6)_72") (pintype "bidirectional"))
    )
    (net (code "233") (name "unconnected-(U1-PA7_(AD7)-Pad71)") (class "Default")
      (node (ref "U1") (pin "71") (pinfunction "PA7_(AD7)_71") (pintype "bidirectional"))
    )
    (net (code "234") (name "unconnected-(U1-PC0_(A8)-Pad53)") (class "Default")
      (node (ref "U1") (pin "53") (pinfunction "PC0_(A8)_53") (pintype "bidirectional"))
    )
    (net (code "235") (name "unconnected-(U1-PC1_(A9)-Pad54)") (class "Default")
      (node (ref "U1") (pin "54") (pinfunction "PC1_(A9)_54") (pintype "bidirectional"))
    )
    (net (code "236") (name "unconnected-(U1-PC2_(A10)-Pad55)") (class "Default")
      (node (ref "U1") (pin "55") (pinfunction "PC2_(A10)_55") (pintype "bidirectional"))
    )
    (net (code "237") (name "unconnected-(U1-PC3_(A11)-Pad56)") (class "Default")
      (node (ref "U1") (pin "56") (pinfunction "PC3_(A11)_56") (pintype "bidirectional"))
    )
    (net (code "238") (name "unconnected-(U1-PC4_(A12)-Pad57)") (class "Default")
      (node (ref "U1") (pin "57") (pinfunction "PC4_(A12)_57") (pintype "bidirectional"))
    )
    (net (code "239") (name "unconnected-(U1-PC5_(A13)-Pad58)") (class "Default")
      (node (ref "U1") (pin "58") (pinfunction "PC5_(A13)_58") (pintype "bidirectional"))
    )
    (net (code "240") (name "unconnected-(U1-PC6_(A14)-Pad59)") (class "Default")
      (node (ref "U1") (pin "59") (pinfunction "PC6_(A14)_59") (pintype "bidirectional"))
    )
    (net (code "241") (name "unconnected-(U1-PC7_(A15)-Pad60)") (class "Default")
      (node (ref "U1") (pin "60") (pinfunction "PC7_(A15)_60") (pintype "bidirectional"))
    )
    (net (code "242") (name "unconnected-(U1-PG0_(~{WR})-Pad51)") (class "Default")
      (node (ref "U1") (pin "51") (pinfunction "PG0_(~{WR})_51") (pintype "bidirectional"))
    )
    (net (code "243") (name "unconnected-(U1-PG1_(~{RD})-Pad52)") (class "Default")
      (node (ref "U1") (pin "52") (pinfunction "PG1_(~{RD})_52") (pintype "bidirectional"))
    )
    (net (code "244") (name "unconnected-(U1-PG2_(ALE)-Pad70)") (class "Default")
      (node (ref "U1") (pin "70") (pinfunction "PG2_(ALE)_70") (pintype "bidirectional"))
    )
    (net (code "245") (name "unconnected-(U1-PJ2_(XCK3{slash}PCINT11)-Pad65)") (class "Default")
      (node (ref "U1") (pin "65") (pinfunction "PJ2_(XCK3/PCINT11)_65") (pintype "bidirectional"))
    )
    (net (code "246") (name "unconnected-(U1-PJ3_(PCINT12)-Pad66)") (class "Default")
      (node (ref "U1") (pin "66") (pinfunction "PJ3_(PCINT12)_66") (pintype "bidirectional"))
    )
    (net (code "247") (name "unconnected-(U1-PJ4_(PCINT13)-Pad67)") (class "Default")
      (node (ref "U1") (pin "67") (pinfunction "PJ4_(PCINT13)_67") (pintype "bidirectional"))
    )
    (net (code "248") (name "unconnected-(U1-PJ5_(PCINT14)-Pad68)") (class "Default")
      (node (ref "U1") (pin "68") (pinfunction "PJ5_(PCINT14)_68") (pintype "bidirectional"))
    )
    (net (code "249") (name "unconnected-(U1-PJ6_(PCINT15)-Pad69)") (class "Default")
      (node (ref "U1") (pin "69") (pinfunction "PJ6_(PCINT15)_69") (pintype "bidirectional"))
    )
    (net (code "250") (name "unconnected-(U1-PJ7-Pad79)") (class "Default")
      (node (ref "U1") (pin "79") (pinfunction "PJ7_79") (pintype "bidirectional"))
    )
    (net (code "251") (name "unconnected-(U1-PK0_(ADC8{slash}PCINT16)-Pad89)") (class "Default")
      (node (ref "U1") (pin "89") (pinfunction "PK0_(ADC8/PCINT16)_89") (pintype "bidirectional"))
    )
    (net (code "252") (name "unconnected-(U1-PK1_(ADC9{slash}PCINT17)-Pad88)") (class "Default")
      (node (ref "U1") (pin "88") (pinfunction "PK1_(ADC9/PCINT17)_88") (pintype "bidirectional"))
    )
    (net (code "253") (name "unconnected-(U1-PK2_(ADC10{slash}PCINT18)-Pad87)") (class "Default")
      (node (ref "U1") (pin "87") (pinfunction "PK2_(ADC10/PCINT18)_87") (pintype "bidirectional"))
    )
    (net (code "254") (name "unconnected-(U1-PK3_(ADC11{slash}PCINT19)-Pad86)") (class "Default")
      (node (ref "U1") (pin "86") (pinfunction "PK3_(ADC11/PCINT19)_86") (pintype "bidirectional"))
    )
    (net (code "255") (name "unconnected-(U1-PK4_(ADC12{slash}PCINT20)-Pad85)") (class "Default")
      (node (ref "U1") (pin "85") (pinfunction "PK4_(ADC12/PCINT20)_85") (pintype "bidirectional"))
    )
    (net (code "256") (name "unconnected-(U1-PK5_(ADC13{slash}PCINT21)-Pad84)") (class "Default")
      (node (ref "U1") (pin "84") (pinfunction "PK5_(ADC13/PCINT21)_84") (pintype "bidirectional"))
    )
    (net (code "257") (name "unconnected-(U1-PK6_(ADC14{slash}PCINT22)-Pad83)") (class "Default")
      (node (ref "U1") (pin "83") (pinfunction "PK6_(ADC14/PCINT22)_83") (pintype "bidirectional"))
    )
    (net (code "258") (name "unconnected-(U1-PK7_(ADC15{slash}PCINT23)-Pad82)") (class "Default")
      (node (ref "U1") (pin "82") (pinfunction "PK7_(ADC15/PCINT23)_82") (pintype "bidirectional"))
    )
    (net (code "259") (name "unconnected-(U1-PL6-Pad41)") (class "Default")
      (node (ref "U1") (pin "41") (pinfunction "PL6_41") (pintype "bidirectional"))
    )
    (net (code "260") (name "unconnected-(U1-PL7-Pad42)") (class "Default")
      (node (ref "U1") (pin "42") (pinfunction "PL7_42") (pintype "bidirectional"))
    )
    (net (code "261") (name "unconnected-(U5-(AIN0_{slash}_INT1)_PD1-Pad7)") (class "Default")
      (node (ref "U5") (pin "7") (pinfunction "(AIN0_/_INT1)_PD1_7") (pintype "bidirectional"))
    )
    (net (code "262") (name "unconnected-(U5-(INT5{slash}_AIN3)_PD4-Pad10)") (class "Default")
      (node (ref "U5") (pin "10") (pinfunction "(INT5/_AIN3)_PD4_10") (pintype "bidirectional"))
    )
    (net (code "263") (name "unconnected-(U5-(OC.0B_{slash}_INT0)_PD0-Pad6)") (class "Default")
      (node (ref "U5") (pin "6") (pinfunction "(OC.0B_/_INT0)_PD0_6") (pintype "bidirectional"))
    )
    (net (code "264") (name "unconnected-(U5-(PCINT11_{slash}AIN2_)_PC2-Pad5)") (class "Default")
      (node (ref "U5") (pin "5") (pinfunction "(PCINT11_/AIN2_)_PC2_5") (pintype "bidirectional"))
    )
    (net (code "265") (name "unconnected-(U5-(RTS_{slash}_AIN5_{slash}_INT6)_PD6-Pad12)") (class "Default")
      (node (ref "U5") (pin "12") (pinfunction "(RTS_/_AIN5_/_INT6)_PD6_12") (pintype "bidirectional"))
    )
    (net (code "266") (name "unconnected-(U5-(XCK_AIN4_{slash}_PCINT12)_PD5-Pad11)") (class "Default")
      (node (ref "U5") (pin "11") (pinfunction "(XCK_AIN4_/_PCINT12)_PD5_11") (pintype "bidirectional"))
    )
    (net (code "267") (name "unconnected-(U5-(~{SS_{slash}_PCINT0})_PB0-Pad14)") (class "Default")
      (node (ref "U5") (pin "14") (pinfunction "(~{SS_/_PCINT0})_PB0_14") (pintype "bidirectional"))
    )
    (net (code "268") (name "unconnected-(U5-PB4_(T1_{slash}_PCINT4)-Pad18)") (class "Default")
      (node (ref "U5") (pin "18") (pinfunction "PB4_(T1_/_PCINT4)_18") (pintype "bidirectional"))
    )
    (net (code "269") (name "unconnected-(U5-PB5_(PCINT5)-Pad19)") (class "Default")
      (node (ref "U5") (pin "19") (pinfunction "PB5_(PCINT5)_19") (pintype "bidirectional"))
    )
    (net (code "270") (name "unconnected-(U5-PB6_(PCINT6)-Pad20)") (class "Default")
      (node (ref "U5") (pin "20") (pinfunction "PB6_(PCINT6)_20") (pintype "bidirectional"))
    )
    (net (code "271") (name "unconnected-(U5-PB7_(PCINT7_{slash}_OC.0A_{slash}_OC.1C)-Pad21)") (class "Default")
      (node (ref "U5") (pin "21") (pinfunction "PB7_(PCINT7_/_OC.0A_/_OC.1C)_21") (pintype "bidirectional"))
    )
    (net (code "272") (name "unconnected-(U5-PC4_(PCINT10)-Pad26)") (class "Default")
      (node (ref "U5") (pin "26") (pinfunction "PC4_(PCINT10)_26") (pintype "bidirectional"))
    )
    (net (code "273") (name "unconnected-(U5-PC5_(_PCINT9{slash}_OC.1B)-Pad25)") (class "Default")
      (node (ref "U5") (pin "25") (pinfunction "PC5_(_PCINT9/_OC.1B)_25") (pintype "bidirectional"))
    )
    (net (code "274") (name "unconnected-(U5-PC6_(OC.1A_{slash}_PCINT8)-Pad23)") (class "Default")
      (node (ref "U5") (pin "23") (pinfunction "PC6_(OC.1A_/_PCINT8)_23") (pintype "bidirectional"))
    )
    (net (code "275") (name "unconnected-(U5-PC7_(INT4_{slash}_ICP1_{slash}_CLKO)-Pad22)") (class "Default")
      (node (ref "U5") (pin "22") (pinfunction "PC7_(INT4_/_ICP1_/_CLKO)_22") (pintype "bidirectional"))
    )
    (net (code "276") (name "unconnected-(U12-IN7-Pad7)") (class "Default")
      (node (ref "U12") (pin "7") (pinfunction "IN7_7") (pintype "bidirectional"))
    )
    (net (code "277") (name "unconnected-(U12-OUT7-Pad10)") (class "Default")
      (node (ref "U12") (pin "10") (pinfunction "OUT7_10") (pintype "bidirectional"))
    )
  )
)
